# PDNode-600_Pro.net
KiCad netlist of a schematic drawn in EAGLE
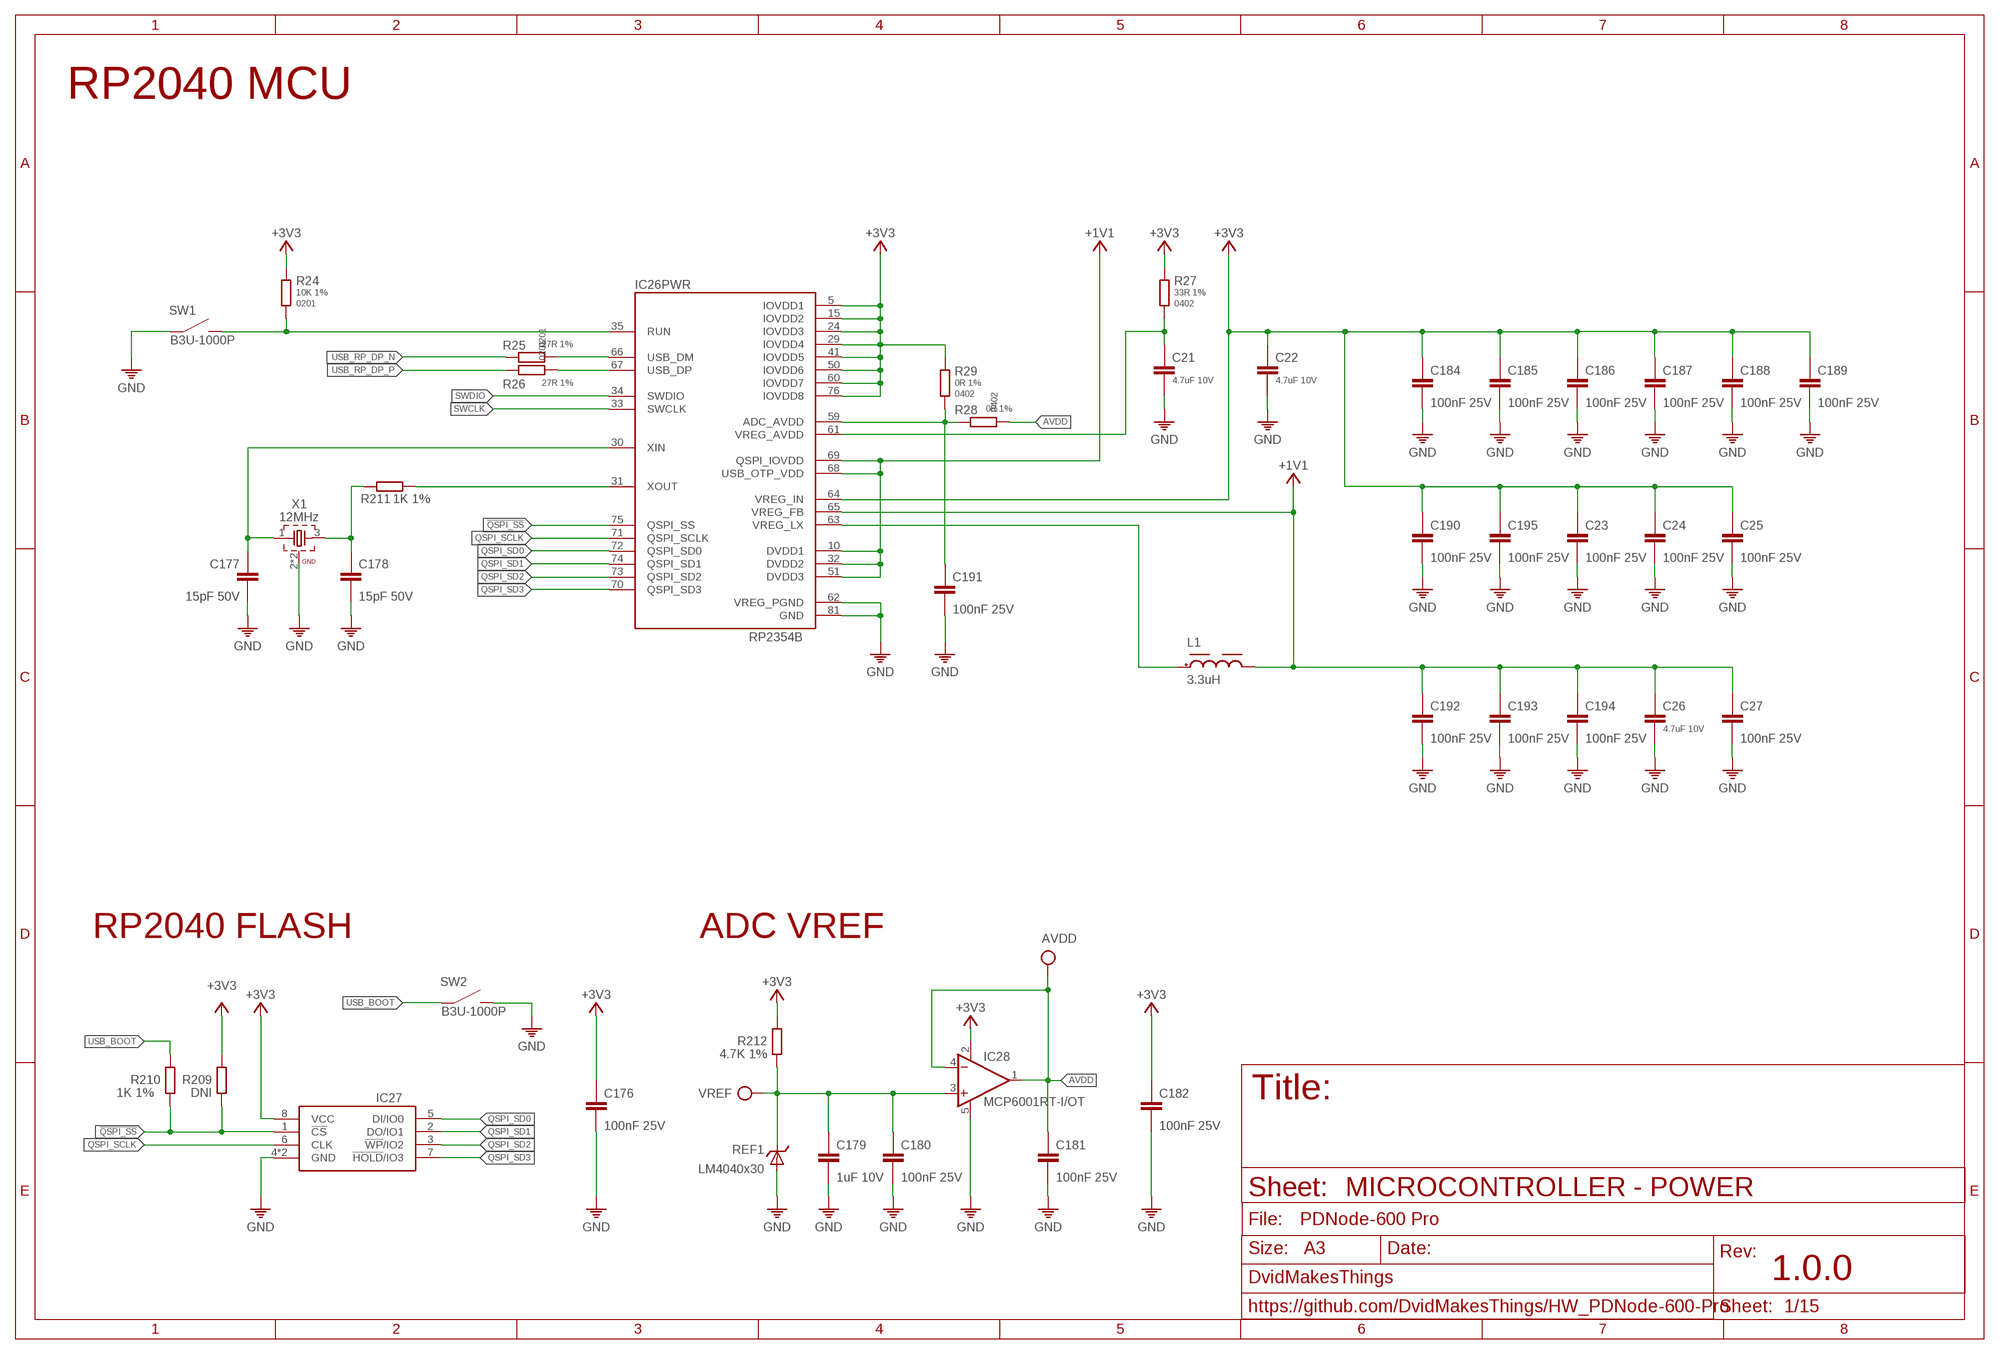
[diagram p0: schematic, sheet 1]
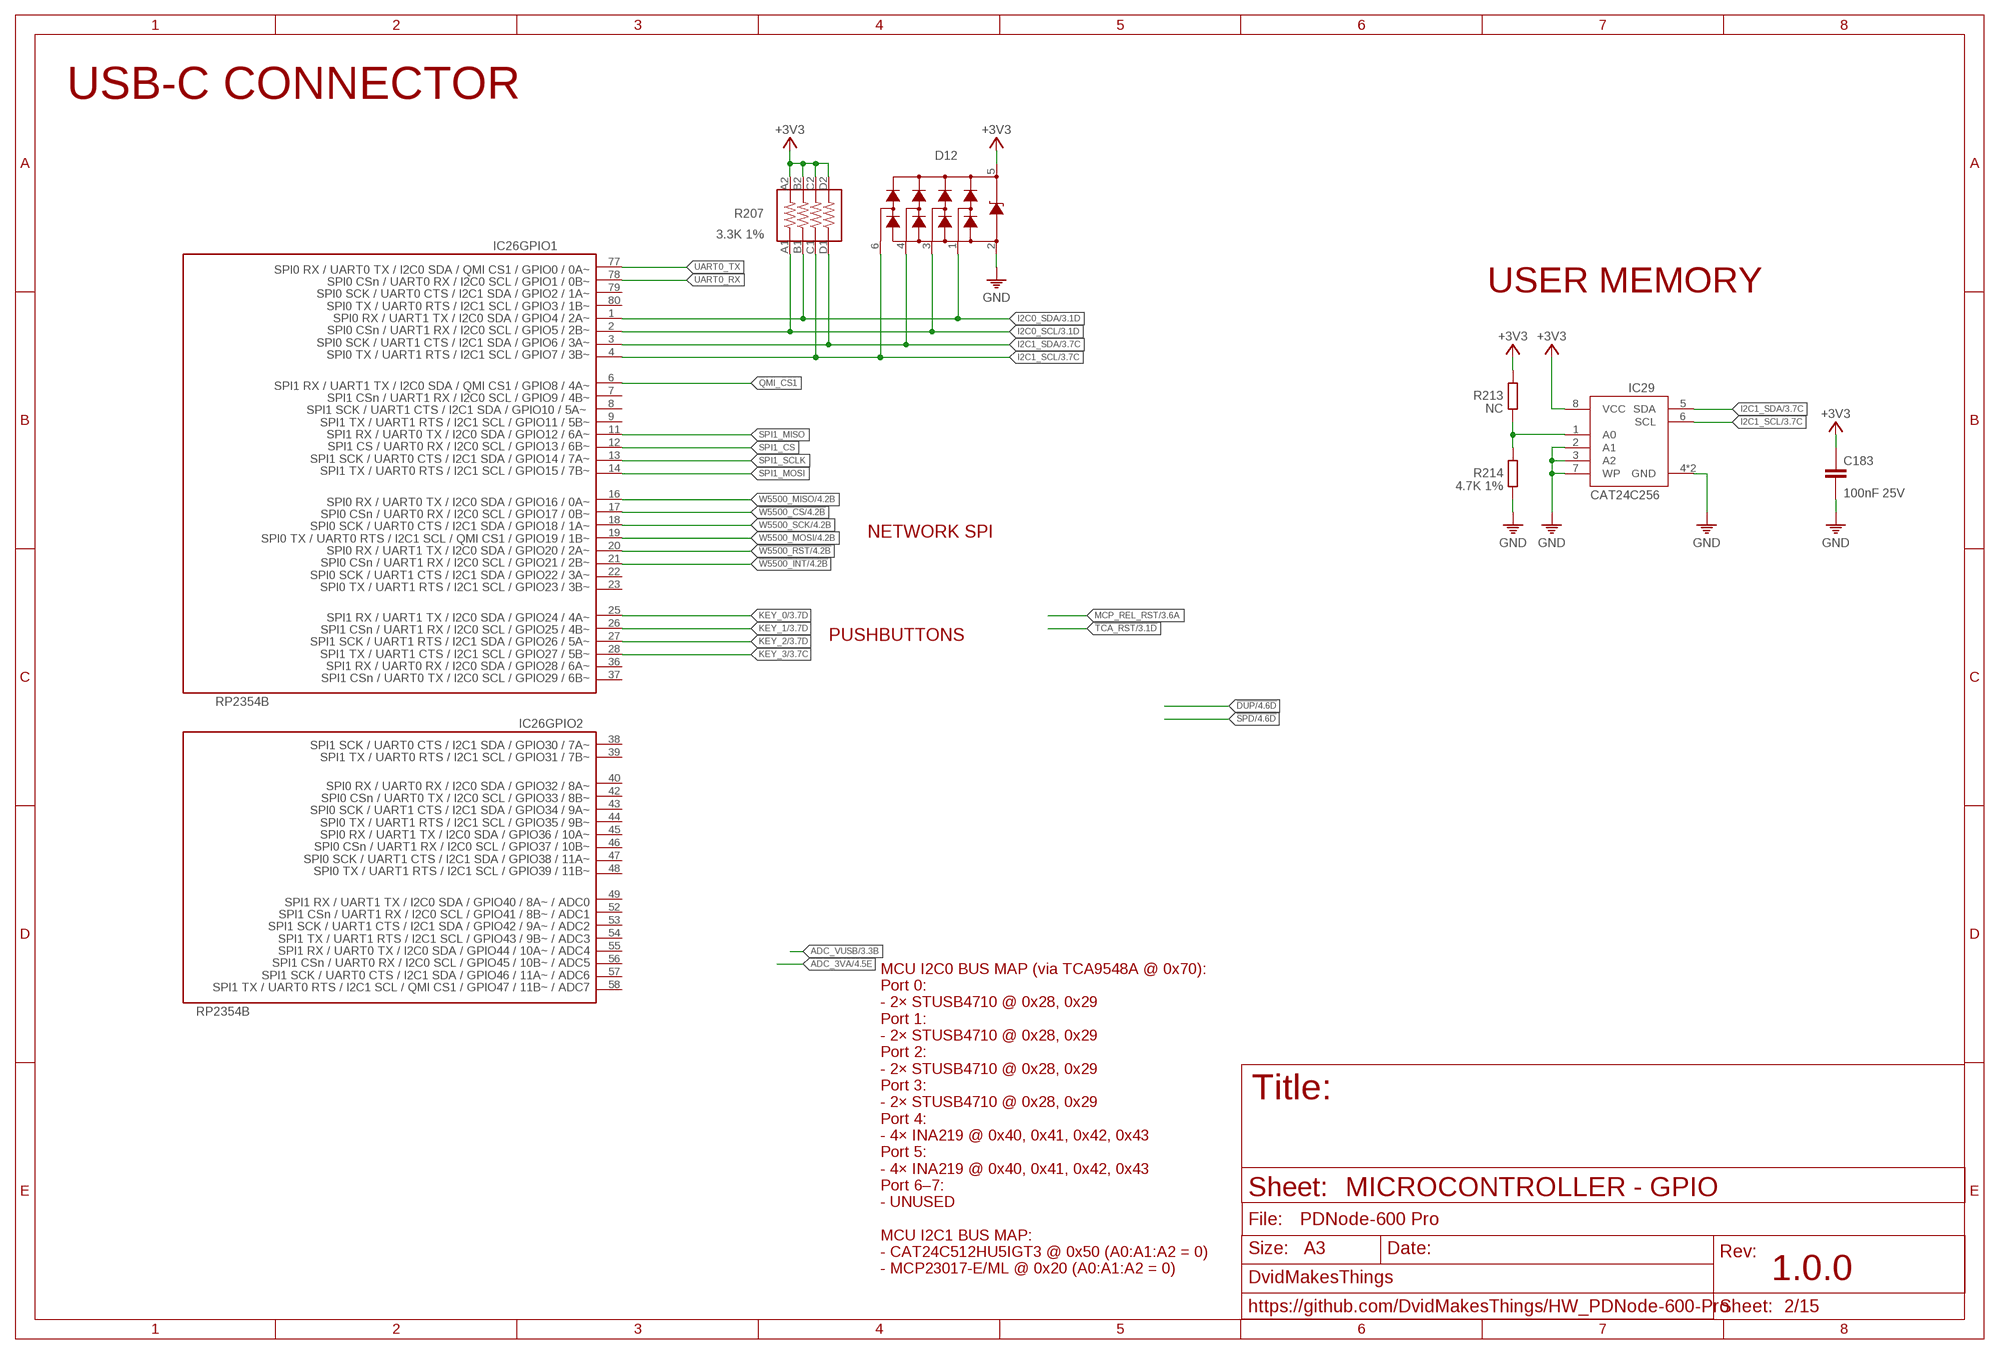
[diagram p1: schematic, sheet 2]
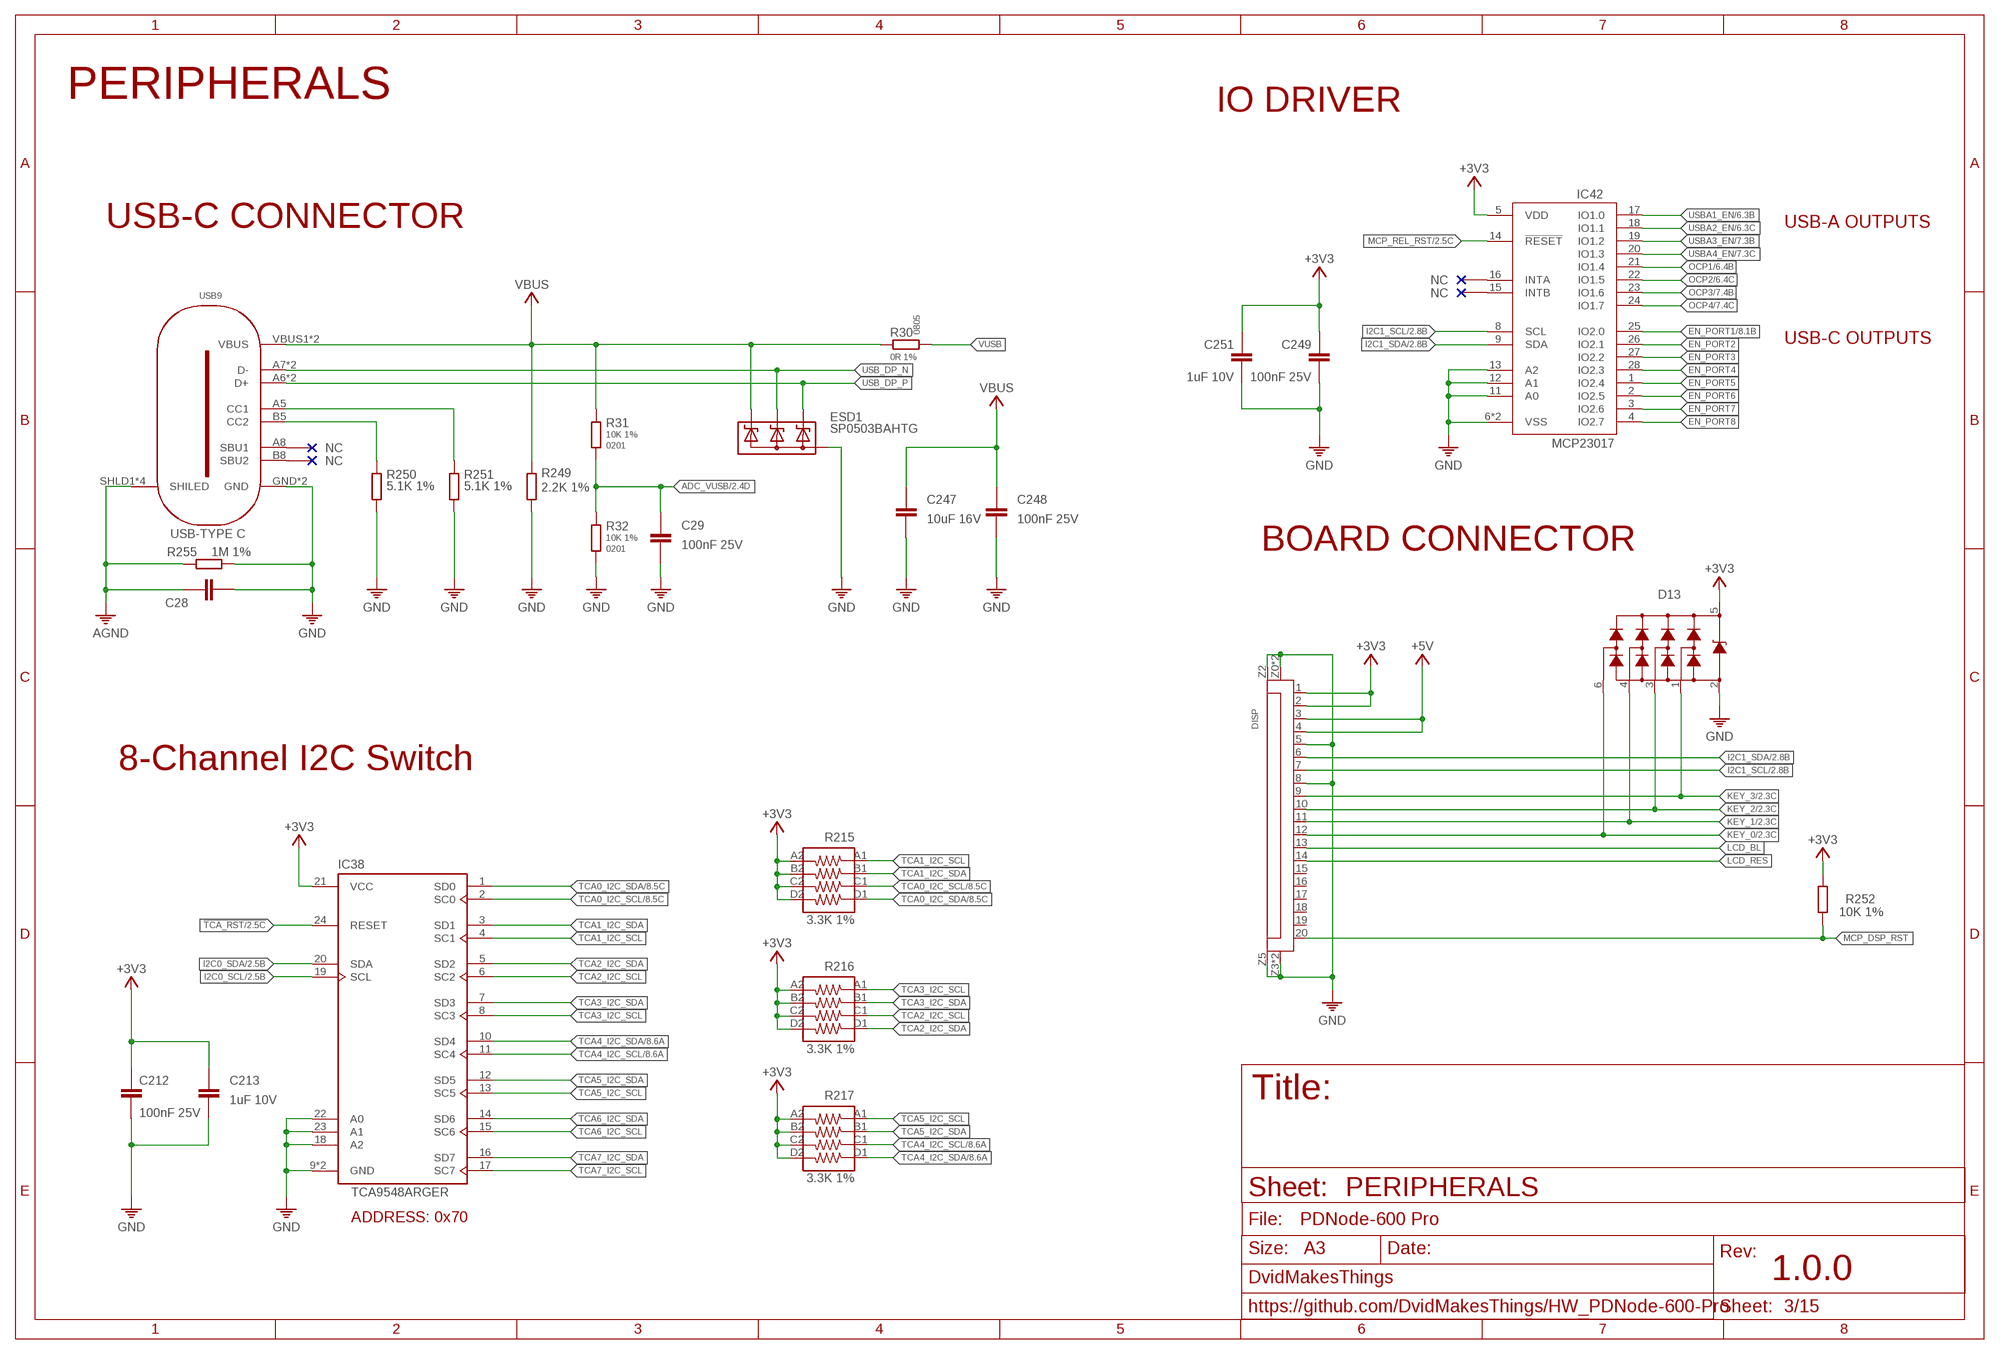
[diagram p2: schematic, sheet 3]
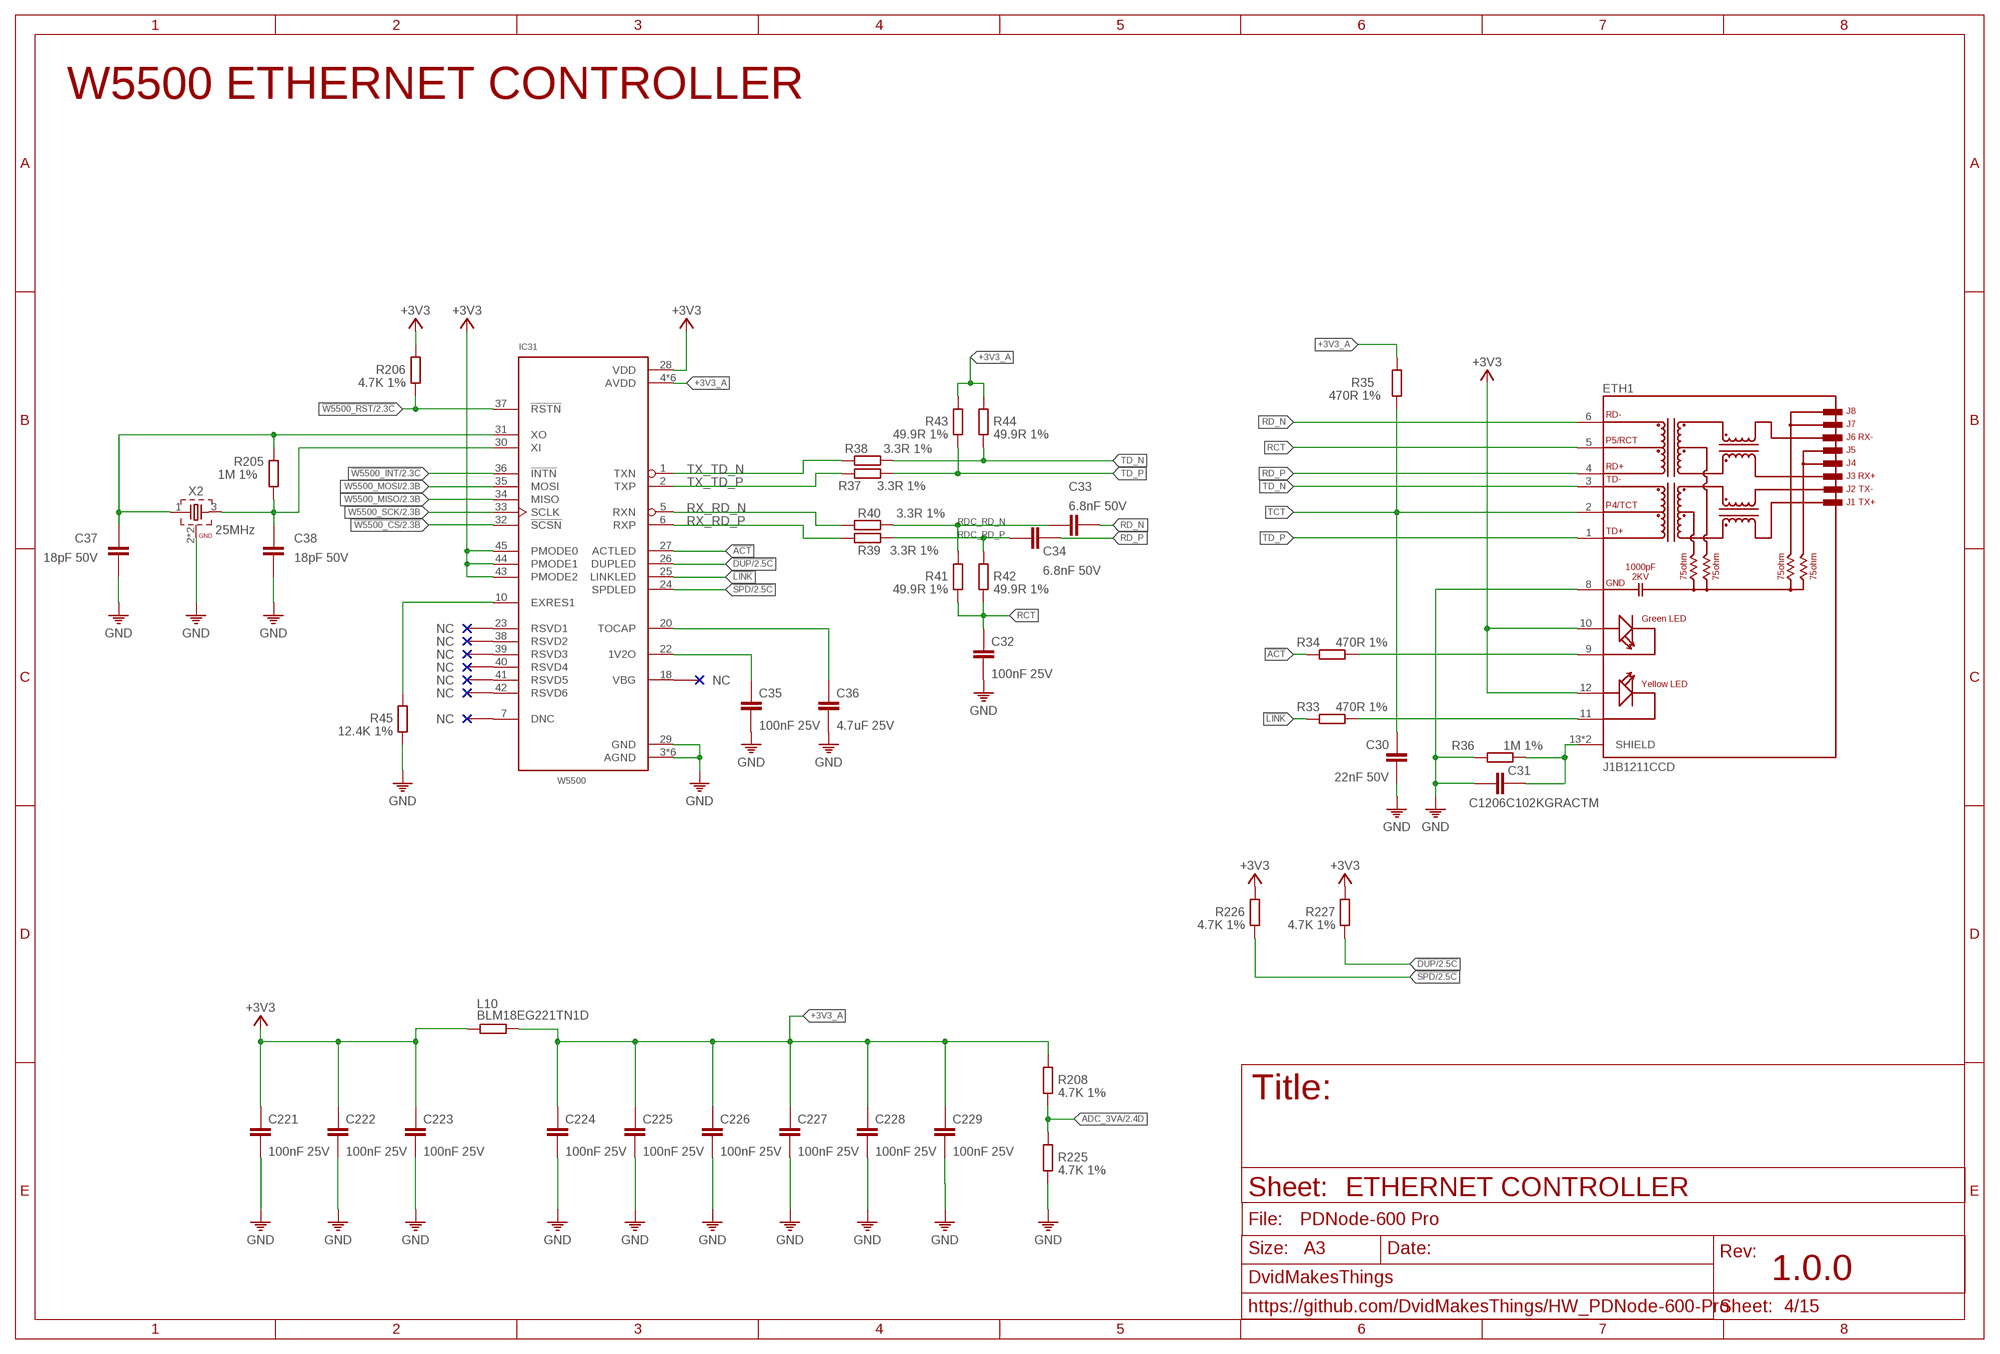
[diagram p3: schematic, sheet 4]
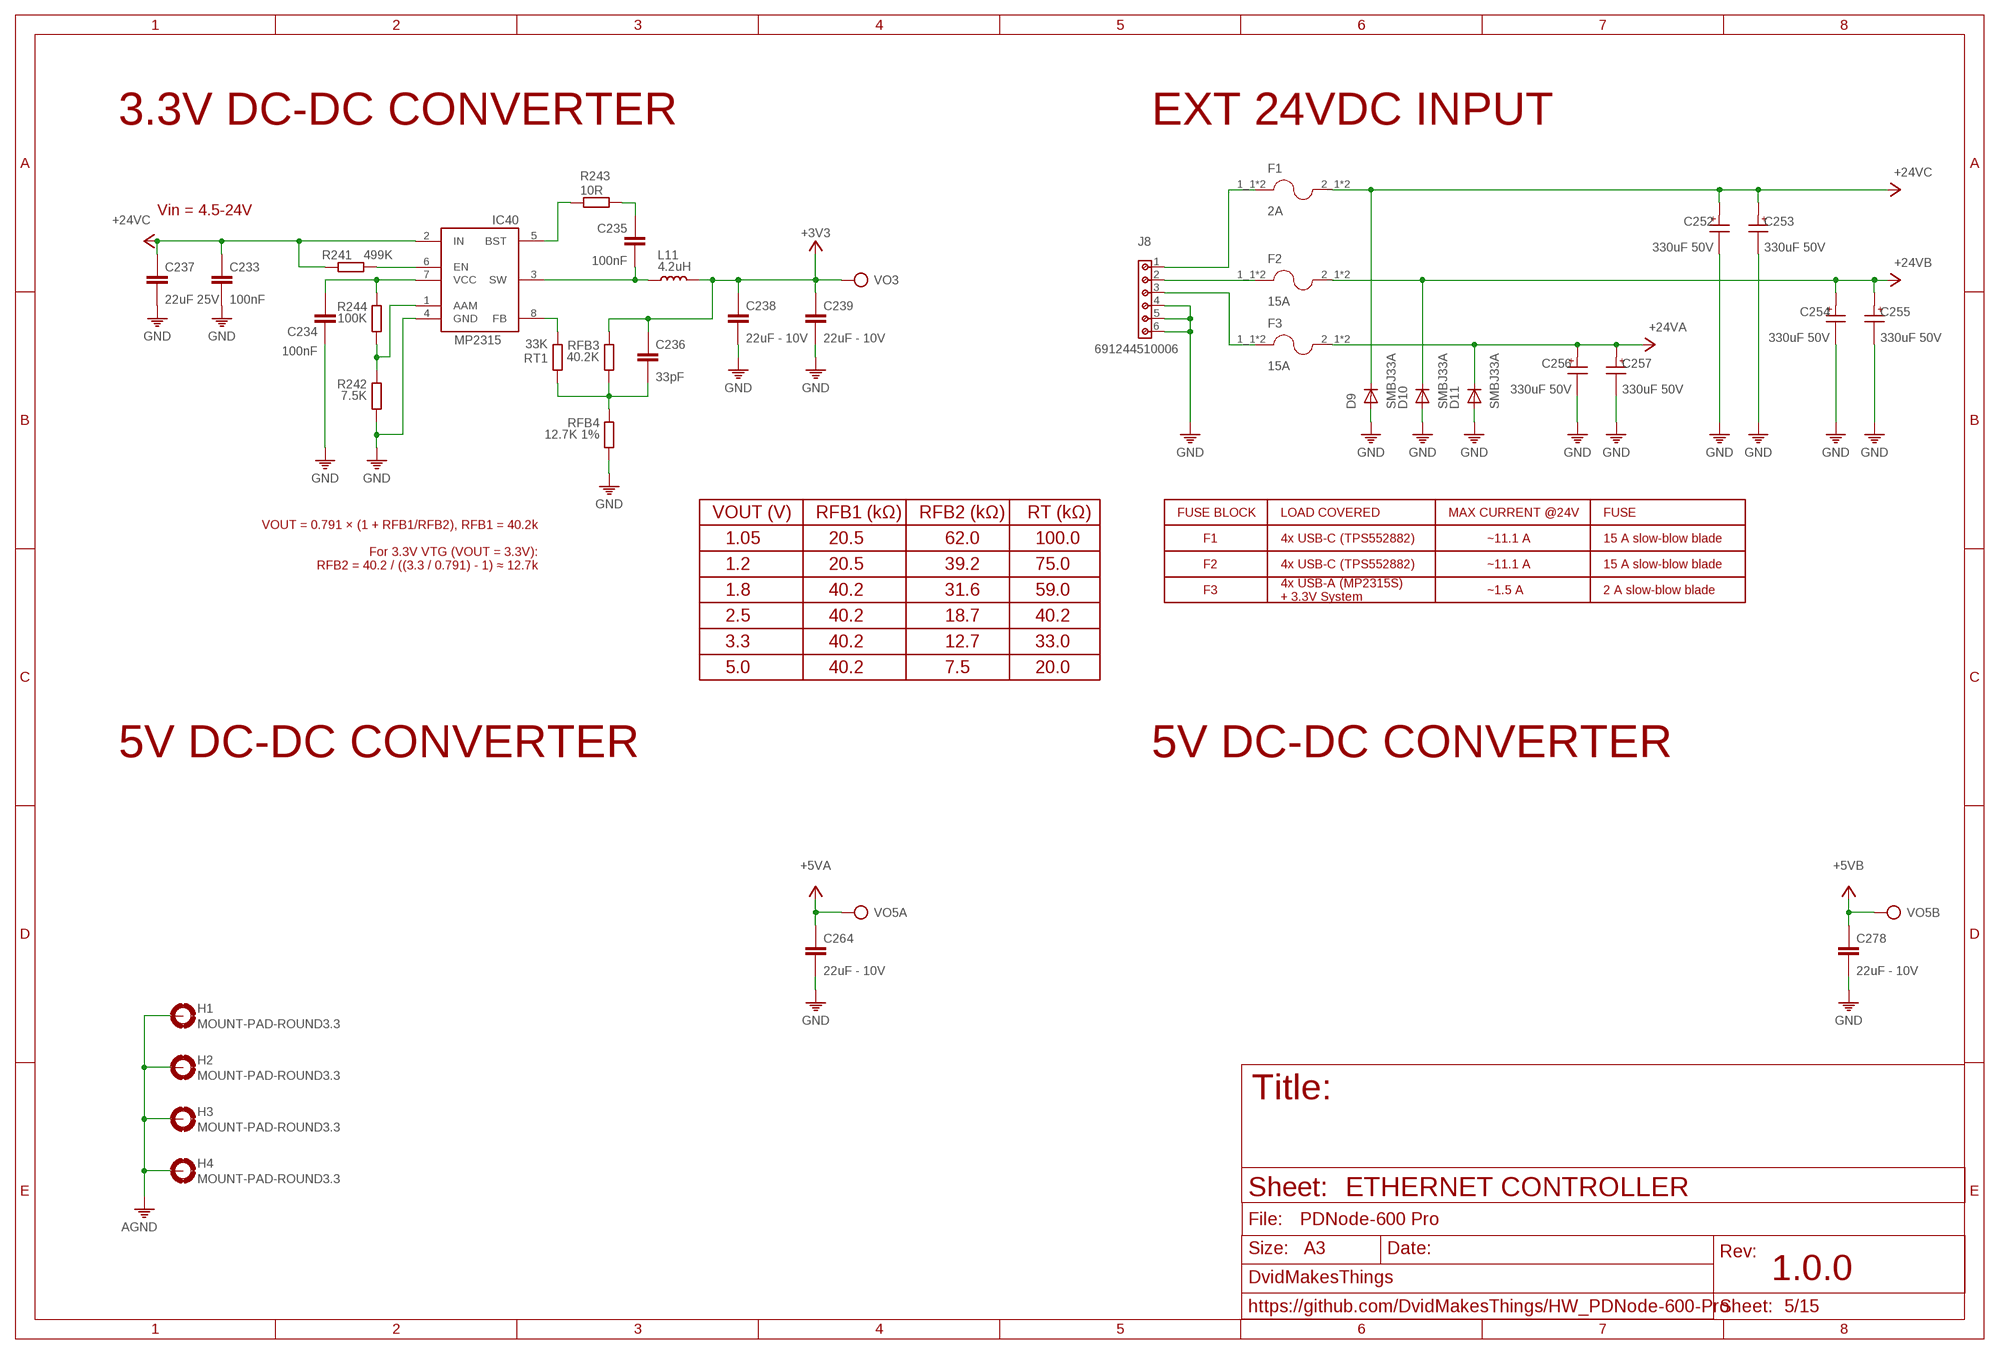
[diagram p4: schematic, sheet 5]
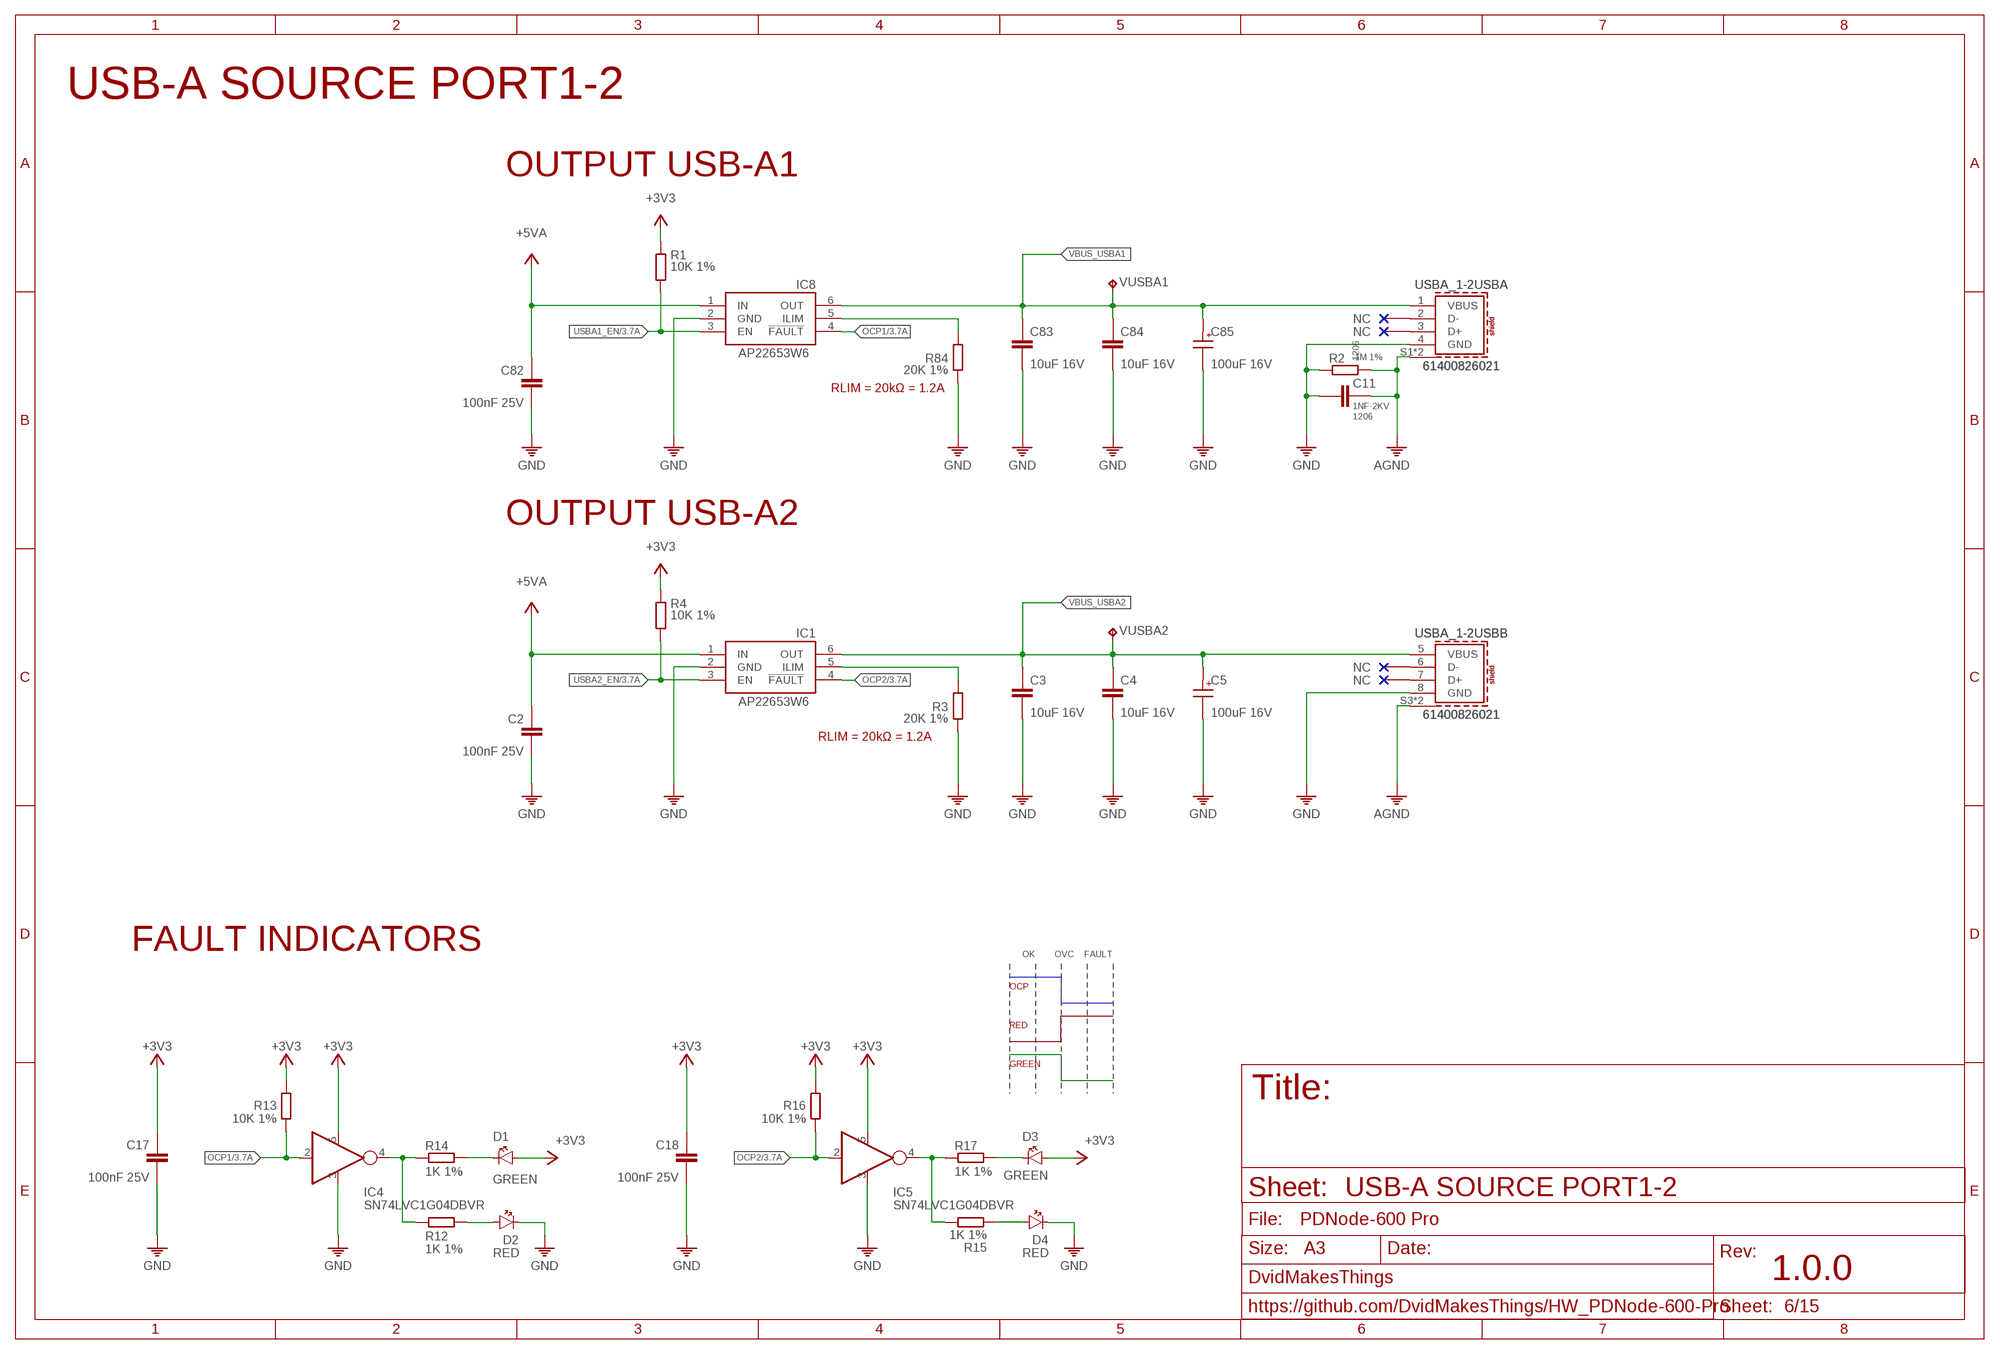
[diagram p5: schematic, sheet 6]
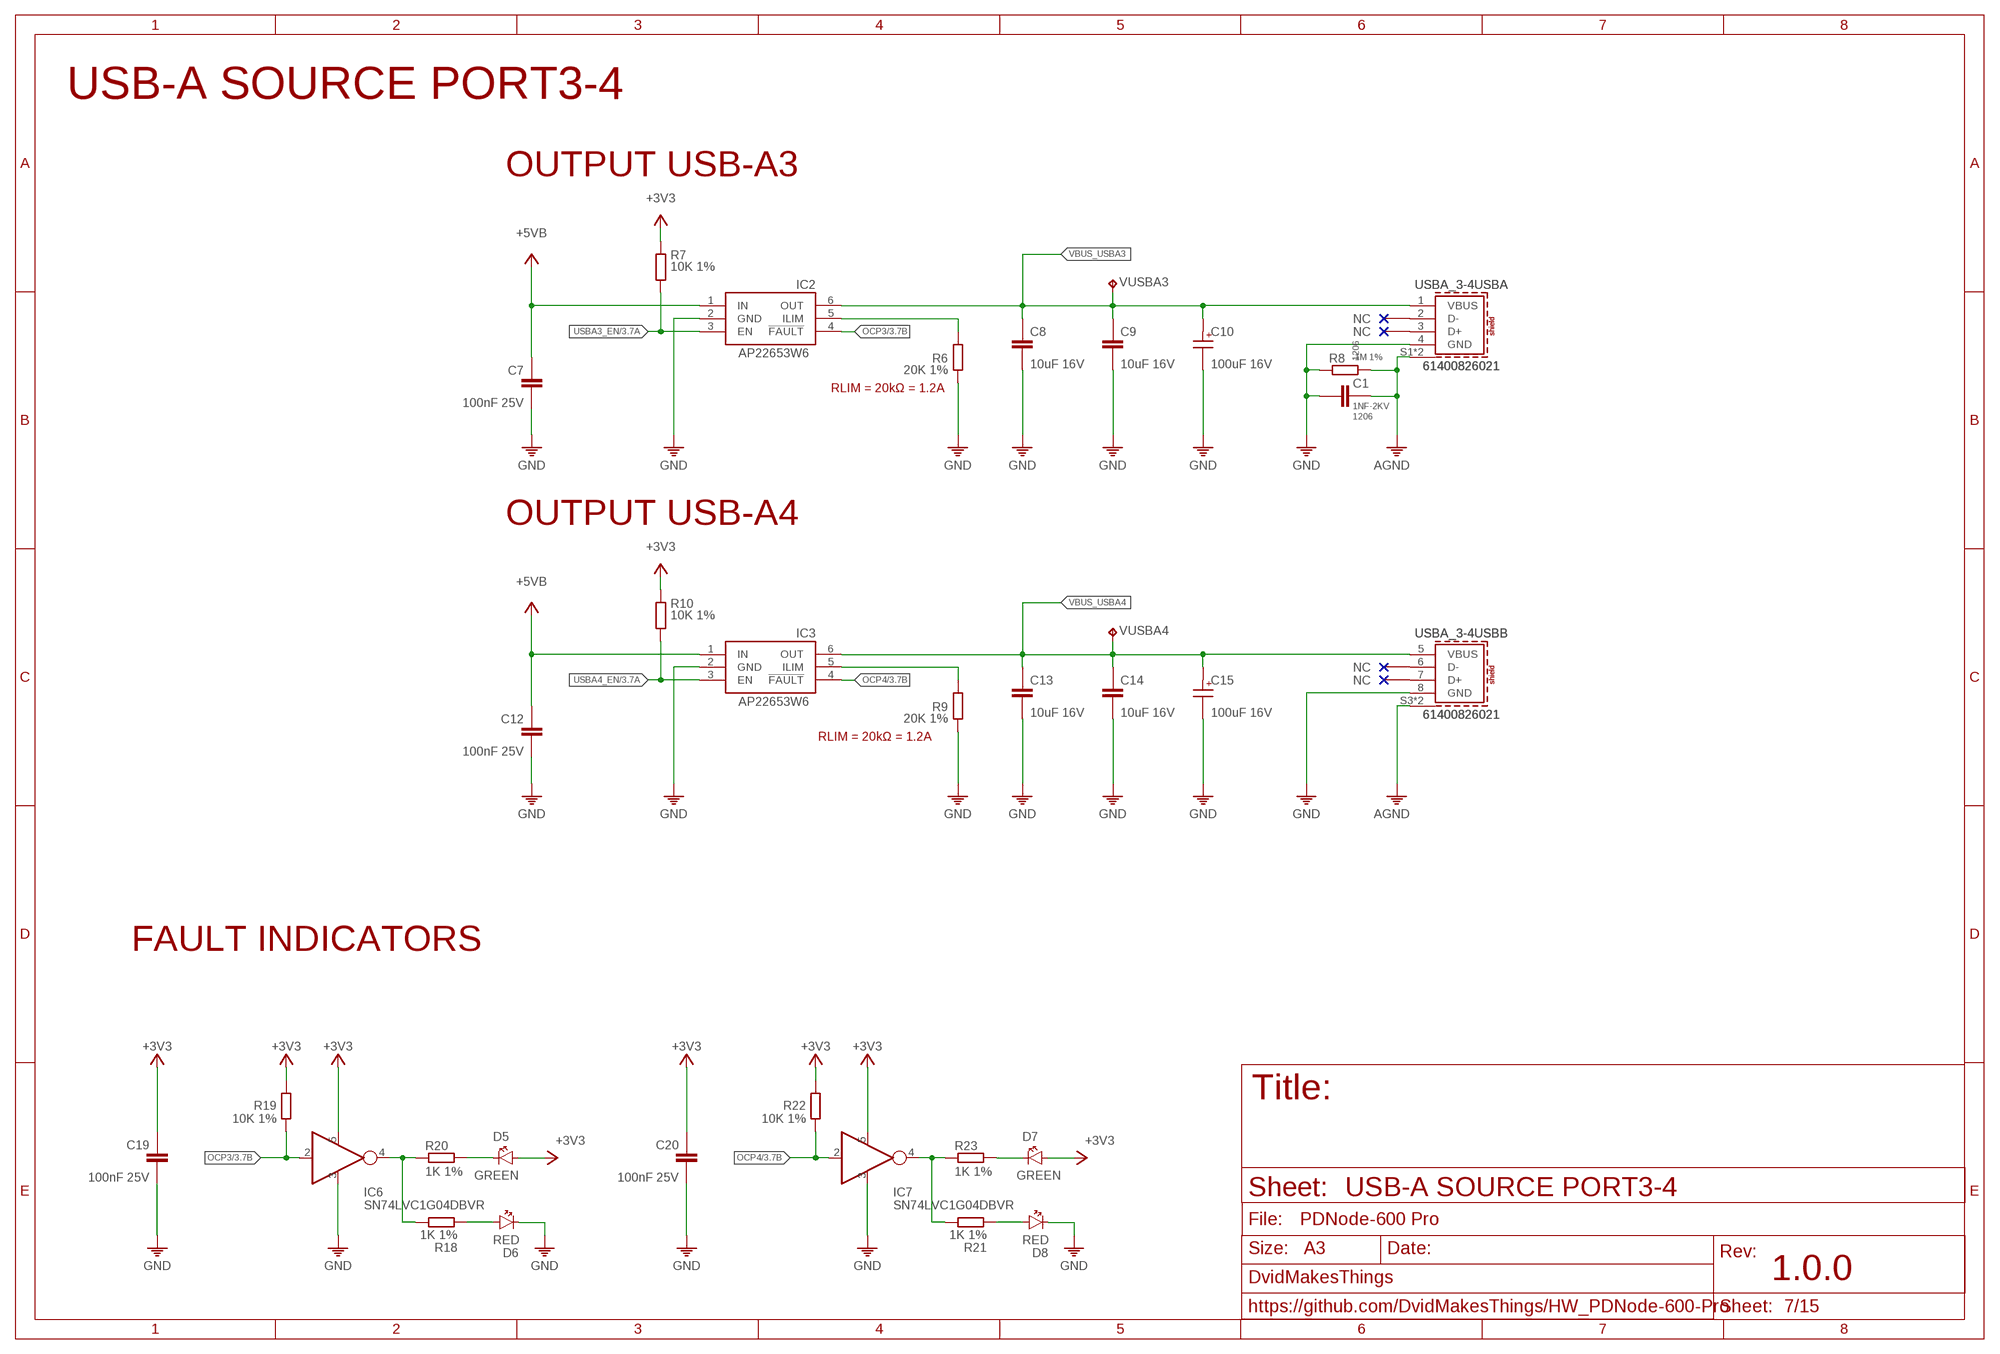
[diagram p6: schematic, sheet 7]
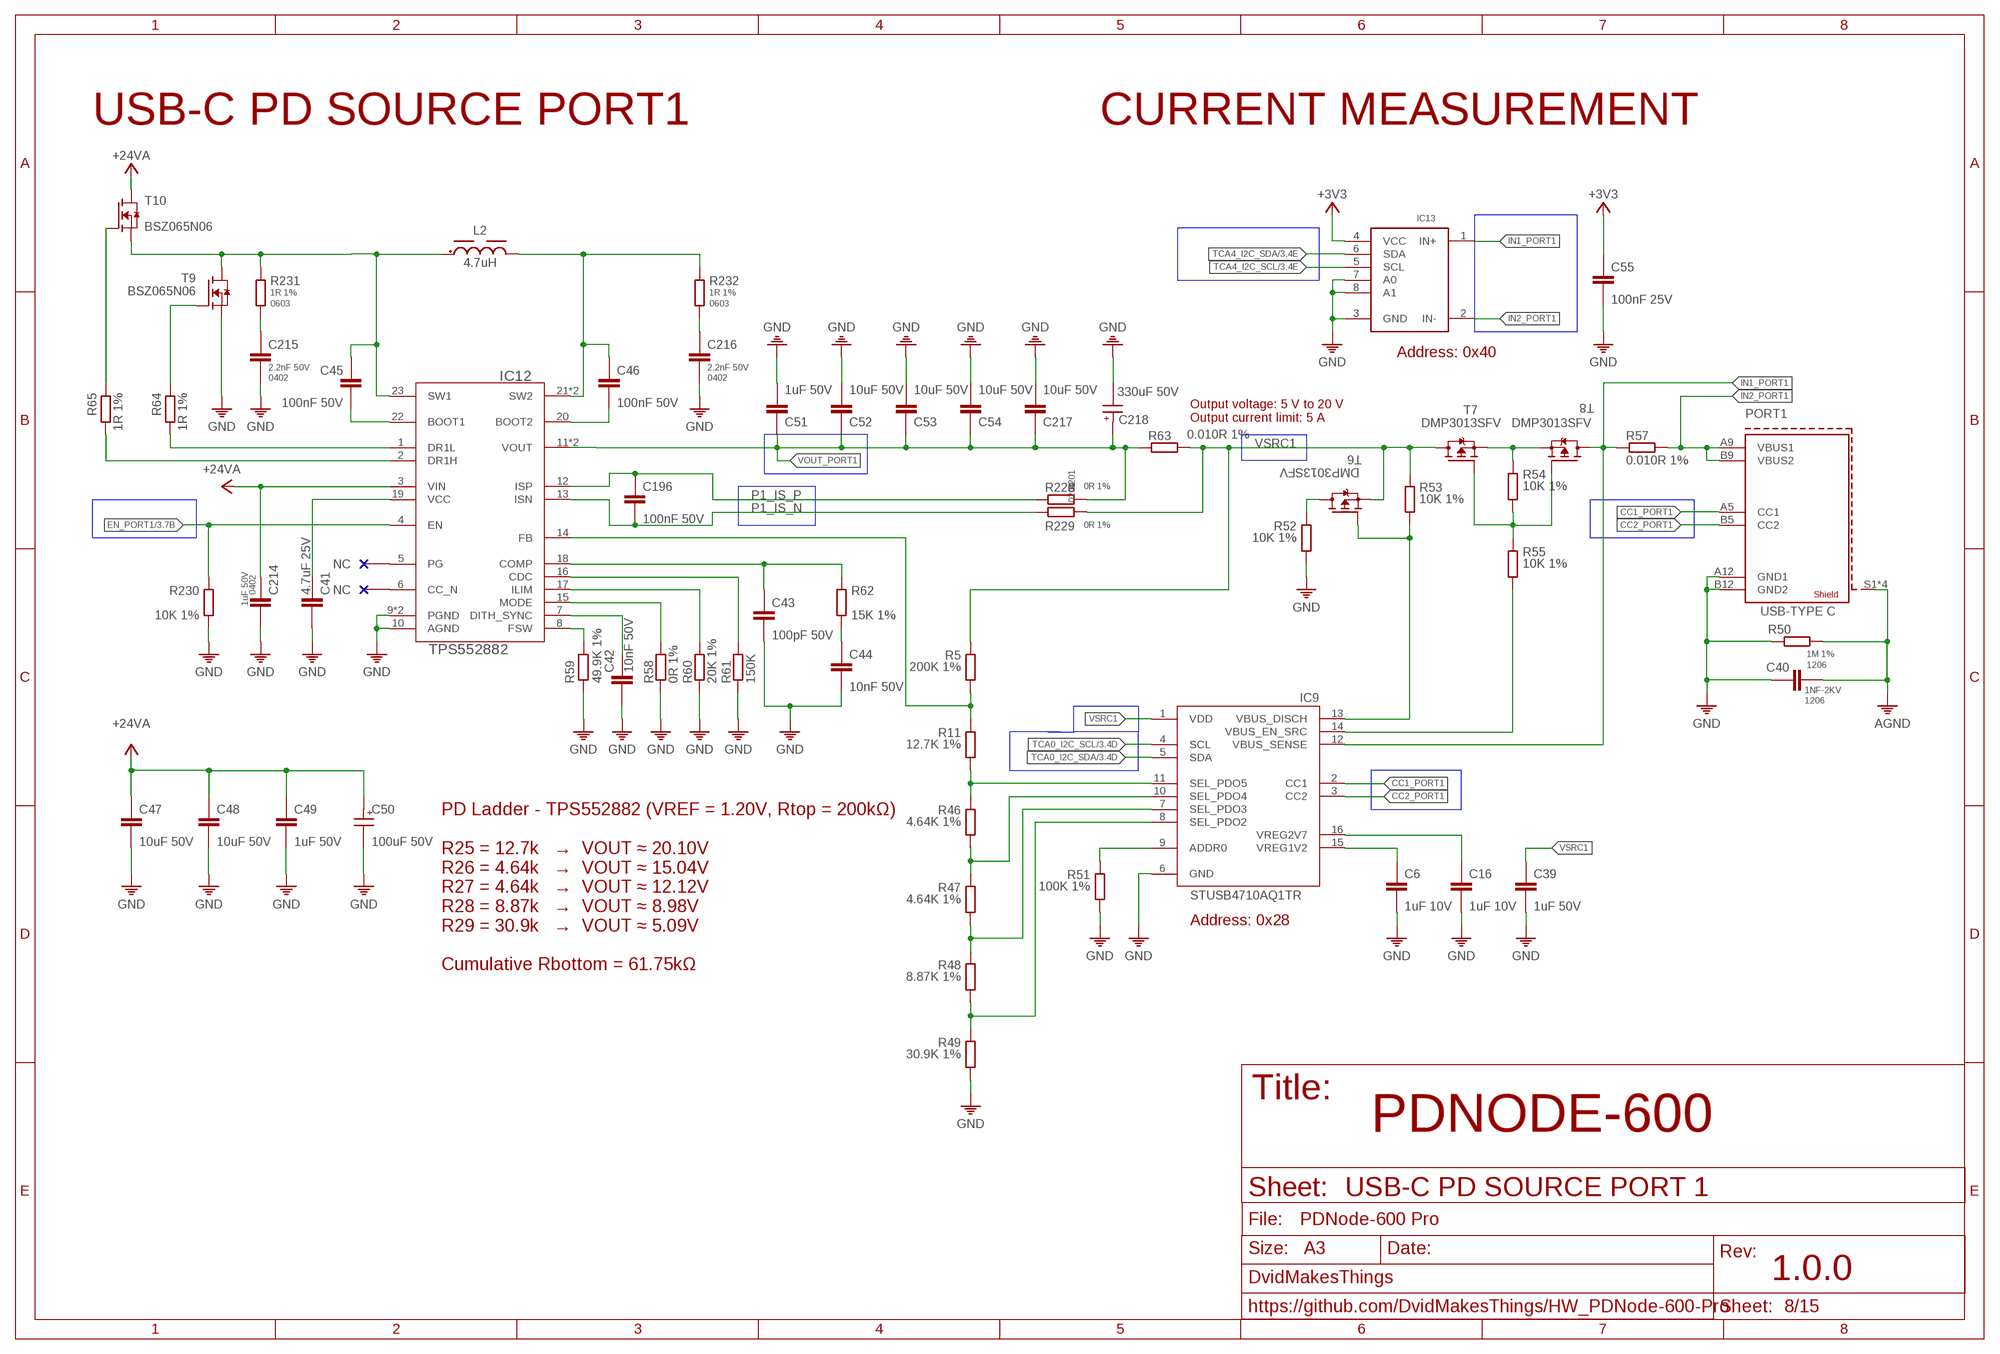
[diagram p7: schematic, sheet 8]

(export (version "E")
  (design (tool "Eeschema 10.0.6"))
  (components
    (comp (ref "C1")
      (value "1NF-2KV")
      (footprint "eagle-import:1206")
      (fields
        (field (name "PACKAGE") "1206")
        (field (name "HQ_PART") "CA0134884")
        (field (name "LCSC_PART") "C9196")
        (field (name "MANUFACTURER") "KEMET")
      )
      (libsource (lib "eagle-import") (part "1NF-2KV"))
    )
    (comp (ref "C7")
      (value "100nF 25V")
      (footprint "eagle-import:0201")
      (fields
        (field (name "HQ_PART") "CA0183221")
        (field (name "LCSC_PART") "C76939")
        (field (name "MANUFACTURER") "Samsung")
      )
      (libsource (lib "eagle-import") (part "100NF-25V-0201"))
    )
    (comp (ref "C8")
      (value "10uF 16V")
      (footprint "eagle-import:0603")
      (fields
        (field (name "HQ_PART") "CA0149236")
        (field (name "LCSC_PART") "C92487")
        (field (name "MANUFACTURER") "Murata")
      )
      (libsource (lib "eagle-import") (part "10UF-16V-0603"))
    )
    (comp (ref "C9")
      (value "10uF 16V")
      (footprint "eagle-import:0603")
      (fields
        (field (name "HQ_PART") "CA0149236")
        (field (name "LCSC_PART") "C92487")
        (field (name "MANUFACTURER") "Murata")
      )
      (libsource (lib "eagle-import") (part "10UF-16V-0603"))
    )
    (comp (ref "C10")
      (value "100uF 16V")
      (footprint "eagle-import:5X5.5(DXL)")
      (fields (field (name "LCSC_PART") "C2977550"))
      (libsource (lib "eagle-import") (part "100UF-16V5X5.5(DXL)"))
    )
    (comp (ref "C12")
      (value "100nF 25V")
      (footprint "eagle-import:0201")
      (fields
        (field (name "HQ_PART") "CA0183221")
        (field (name "LCSC_PART") "C76939")
        (field (name "MANUFACTURER") "Samsung")
      )
      (libsource (lib "eagle-import") (part "100NF-25V-0201"))
    )
    (comp (ref "C13")
      (value "10uF 16V")
      (footprint "eagle-import:0603")
      (fields
        (field (name "HQ_PART") "CA0149236")
        (field (name "LCSC_PART") "C92487")
        (field (name "MANUFACTURER") "Murata")
      )
      (libsource (lib "eagle-import") (part "10UF-16V-0603"))
    )
    (comp (ref "C14")
      (value "10uF 16V")
      (footprint "eagle-import:0603")
      (fields
        (field (name "HQ_PART") "CA0149236")
        (field (name "LCSC_PART") "C92487")
        (field (name "MANUFACTURER") "Murata")
      )
      (libsource (lib "eagle-import") (part "10UF-16V-0603"))
    )
    (comp (ref "C15")
      (value "100uF 16V")
      (footprint "eagle-import:5X5.5(DXL)")
      (fields (field (name "LCSC_PART") "C2977550"))
      (libsource (lib "eagle-import") (part "100UF-16V5X5.5(DXL)"))
    )
    (comp (ref "C19")
      (value "100nF 25V")
      (footprint "eagle-import:0201")
      (fields
        (field (name "HQ_PART") "CA0183221")
        (field (name "LCSC_PART") "C76939")
        (field (name "MANUFACTURER") "Samsung")
      )
      (libsource (lib "eagle-import") (part "100NF-25V-0201"))
    )
    (comp (ref "C20")
      (value "100nF 25V")
      (footprint "eagle-import:0201")
      (fields
        (field (name "HQ_PART") "CA0183221")
        (field (name "LCSC_PART") "C76939")
        (field (name "MANUFACTURER") "Samsung")
      )
      (libsource (lib "eagle-import") (part "100NF-25V-0201"))
    )
    (comp (ref "D5")
      (value "GREEN")
      (footprint "eagle-import:LEDC1608X35N_FLAT-G")
      (libsource (lib "eagle-import") (part "CHIP-FLAT-G_0603-0.35MM"))
    )
    (comp (ref "D6")
      (value "RED")
      (footprint "eagle-import:LEDC1608X35N_FLAT-R")
      (libsource (lib "eagle-import") (part "CHIP-FLAT-R_0603-0.35MM"))
    )
    (comp (ref "D7")
      (value "GREEN")
      (footprint "eagle-import:LEDC1608X35N_FLAT-G")
      (libsource (lib "eagle-import") (part "CHIP-FLAT-G_0603-0.35MM"))
    )
    (comp (ref "D8")
      (value "RED")
      (footprint "eagle-import:LEDC1608X35N_FLAT-R")
      (libsource (lib "eagle-import") (part "CHIP-FLAT-R_0603-0.35MM"))
    )
    (comp (ref "IC2")
      (value "AP22653W6")
      (footprint "eagle-import:SOT23-6")
      (fields
        (field (name "HQ_PART") "PM0174903")
        (field (name "LCSC_PART") "C2158037")
        (field (name "MANUFACTURER") "Diodes Incorporated")
      )
      (libsource (lib "eagle-import") (part "AP22653W6"))
    )
    (comp (ref "IC3")
      (value "AP22653W6")
      (footprint "eagle-import:SOT23-6")
      (fields
        (field (name "HQ_PART") "PM0174903")
        (field (name "LCSC_PART") "C2158037")
        (field (name "MANUFACTURER") "Diodes Incorporated")
      )
      (libsource (lib "eagle-import") (part "AP22653W6"))
    )
    (comp (ref "IC6")
      (value "SN74LVC1G04DBVR")
      (footprint "eagle-import:SOT95P280X145-5N")
      (libsource (lib "eagle-import") (part "74LVC1G04"))
    )
    (comp (ref "IC7")
      (value "SN74LVC1G04DBVR")
      (footprint "eagle-import:SOT95P280X145-5N")
      (libsource (lib "eagle-import") (part "74LVC1G04"))
    )
    (comp (ref "R6")
      (value "20K 1%")
      (footprint "eagle-import:0201")
      (fields (field (name "LCSC_PART") "C473466"))
      (libsource (lib "eagle-import") (part "20K-1%0201"))
    )
    (comp (ref "R7")
      (value "10K 1%")
      (footprint "eagle-import:0402")
      (fields
        (field (name "HQ_PART") "RE0207399")
        (field (name "LCSC_PART") "C25744")
        (field (name "MANUFACTURER") "ROHM")
      )
      (libsource (lib "eagle-import") (part "10K-1%0402"))
    )
    (comp (ref "R8")
      (value "1M 1%")
      (footprint "eagle-import:1206")
      (fields
        (field (name "PACKAGE") "1206")
        (field (name "HQ_PART") "RE0188103")
        (field (name "LCSC_PART") "C17927")
        (field (name "MANUFACTURER") "Uniohm")
      )
      (libsource (lib "eagle-import") (part "1M-1%1206"))
    )
    (comp (ref "R9")
      (value "20K 1%")
      (footprint "eagle-import:0201")
      (fields (field (name "LCSC_PART") "C473466"))
      (libsource (lib "eagle-import") (part "20K-1%0201"))
    )
    (comp (ref "R10")
      (value "10K 1%")
      (footprint "eagle-import:0402")
      (fields
        (field (name "HQ_PART") "RE0207399")
        (field (name "LCSC_PART") "C25744")
        (field (name "MANUFACTURER") "ROHM")
      )
      (libsource (lib "eagle-import") (part "10K-1%0402"))
    )
    (comp (ref "R18")
      (value "1K 1%")
      (footprint "eagle-import:0402")
      (fields
        (field (name "HQ_PART") "RE0208724")
        (field (name "LCSC_PART") "C11702")
        (field (name "MANUFACTURER") "FH")
      )
      (libsource (lib "eagle-import") (part "1K-1%0402"))
    )
    (comp (ref "R19")
      (value "10K 1%")
      (footprint "eagle-import:0402")
      (fields
        (field (name "HQ_PART") "RE0207399")
        (field (name "LCSC_PART") "C25744")
        (field (name "MANUFACTURER") "ROHM")
      )
      (libsource (lib "eagle-import") (part "10K-1%0402"))
    )
    (comp (ref "R20")
      (value "1K 1%")
      (footprint "eagle-import:0402")
      (fields
        (field (name "HQ_PART") "RE0208724")
        (field (name "LCSC_PART") "C11702")
        (field (name "MANUFACTURER") "FH")
      )
      (libsource (lib "eagle-import") (part "1K-1%0402"))
    )
    (comp (ref "R21")
      (value "1K 1%")
      (footprint "eagle-import:0402")
      (fields
        (field (name "HQ_PART") "RE0208724")
        (field (name "LCSC_PART") "C11702")
        (field (name "MANUFACTURER") "FH")
      )
      (libsource (lib "eagle-import") (part "1K-1%0402"))
    )
    (comp (ref "R22")
      (value "10K 1%")
      (footprint "eagle-import:0402")
      (fields
        (field (name "HQ_PART") "RE0207399")
        (field (name "LCSC_PART") "C25744")
        (field (name "MANUFACTURER") "ROHM")
      )
      (libsource (lib "eagle-import") (part "10K-1%0402"))
    )
    (comp (ref "R23")
      (value "1K 1%")
      (footprint "eagle-import:0402")
      (fields
        (field (name "HQ_PART") "RE0208724")
        (field (name "LCSC_PART") "C11702")
        (field (name "MANUFACTURER") "FH")
      )
      (libsource (lib "eagle-import") (part "1K-1%0402"))
    )
    (comp (ref "USBA_3-4")
      (value "61400826021")
      (footprint "eagle-import:61400826021")
      (libsource (lib "eagle-import") (part "61400826021"))
    )
    (comp (ref "VUSBA3")
      (value "TPB1,27")
      (footprint "eagle-import:B1,27")
      (libsource (lib "eagle-import") (part "TPB1,27"))
    )
    (comp (ref "VUSBA4")
      (value "TPB1,27")
      (footprint "eagle-import:B1,27")
      (libsource (lib "eagle-import") (part "TPB1,27"))
    )
    (comp (ref "C28")
      (value "1NF-2KV")
      (footprint "eagle-import:1206")
      (fields
        (field (name "HQ_PART") "CA0134884")
        (field (name "LCSC_PART") "C9196")
        (field (name "MANUFACTURER") "KEMET")
      )
      (libsource (lib "eagle-import") (part "1NF-2KV"))
    )
    (comp (ref "C29")
      (value "100nF 25V")
      (footprint "eagle-import:0402")
      (fields
        (field (name "HQ_PART") "CA0176807")
        (field (name "LCSC_PART") "C56392")
        (field (name "MANUFACTURER") "Walsin")
      )
      (libsource (lib "eagle-import") (part "100NF-25V-0402"))
    )
    (comp (ref "C212")
      (value "100nF 25V")
      (footprint "eagle-import:0201")
      (fields
        (field (name "HQ_PART") "CA0183221")
        (field (name "LCSC_PART") "C76939")
        (field (name "MANUFACTURER") "Samsung")
      )
      (libsource (lib "eagle-import") (part "100NF-25V-0201"))
    )
    (comp (ref "C213")
      (value "1uF 10V")
      (footprint "eagle-import:0201")
      (fields (field (name "LCSC_PART") "C76935"))
      (libsource (lib "eagle-import") (part "1UF-10V0201"))
    )
    (comp (ref "C247")
      (value "10uF 16V")
      (footprint "eagle-import:0603")
      (fields
        (field (name "HQ_PART") "CA0149236")
        (field (name "LCSC_PART") "C92487")
        (field (name "MANUFACTURER") "Murata")
      )
      (libsource (lib "eagle-import") (part "10UF-16V-0603"))
    )
    (comp (ref "C248")
      (value "100nF 25V")
      (footprint "eagle-import:0402")
      (fields
        (field (name "HQ_PART") "CA0176807")
        (field (name "LCSC_PART") "C56392")
        (field (name "MANUFACTURER") "Walsin")
      )
      (libsource (lib "eagle-import") (part "100NF-25V-0402"))
    )
    (comp (ref "C249")
      (value "100nF 25V")
      (footprint "eagle-import:0201")
      (fields
        (field (name "HQ_PART") "CA0183221")
        (field (name "LCSC_PART") "C76939")
        (field (name "MANUFACTURER") "Samsung")
      )
      (libsource (lib "eagle-import") (part "100NF-25V-0201"))
    )
    (comp (ref "C251")
      (value "1uF 10V")
      (footprint "eagle-import:0201")
      (fields (field (name "LCSC_PART") "C76935"))
      (libsource (lib "eagle-import") (part "1UF-10V0201"))
    )
    (comp (ref "D13")
      (value "HDMIULC6-4SC6Y")
      (footprint "eagle-import:SOT23-6")
      (libsource (lib "eagle-import") (part "HDMIULC6-4SC6Y"))
    )
    (comp (ref "DISP")
      (value "AFC11-S20ICC-00")
      (footprint "eagle-import:FPC20")
      (fields
        (field (name "HQ_PART") "CO0889517")
        (field (name "LCSC_PART") "C466537")
        (field (name "MANUFACTURER") "JS")
      )
      (libsource (lib "eagle-import") (part "AFC11-S20ICC-00"))
    )
    (comp (ref "ESD1")
      (value "SP0503BAHTG")
      (footprint "eagle-import:SOT143")
      (fields
        (field (name "HQ_PART") "CP0003989")
        (field (name "LCSC_PART") "C3040626")
        (field (name "MANUFACTURER") "Littelfuse")
      )
      (libsource (lib "eagle-import") (part "SP0503BAHT"))
    )
    (comp (ref "IC38")
      (value "TCA9548ARGER")
      (footprint "eagle-import:QFN50P400X400X100-25T210N")
      (libsource (lib "eagle-import") (part "TCA9548ARGER"))
    )
    (comp (ref "IC42")
      (value "MCP23017T-E/ML")
      (footprint "eagle-import:QFN28[6X6]ML")
      (fields
        (field (name "HQ_PART") "IC0080215")
        (field (name "LCSC_PART") "C629439")
        (field (name "MANUFACTURER") "MICROCHIP")
      )
      (libsource (lib "eagle-import") (part "MCP23017-E/ML"))
    )
    (comp (ref "R30")
      (value "0R 1%")
      (footprint "eagle-import:0805")
      (fields
        (field (name "PACKAGE") "0805")
        (field (name "HQ_PART") "RE0013023")
        (field (name "LCSC_PART") "C17477")
        (field (name "MANUFACTURER") "Vishay")
      )
      (libsource (lib "eagle-import") (part "0R0805"))
    )
    (comp (ref "R31")
      (value "10K 1%")
      (footprint "eagle-import:0201")
      (fields
        (field (name "PACKAGE") "0201")
        (field (name "HQ_PART") "RE0208620")
        (field (name "LCSC_PART") "C473048")
        (field (name "MANUFACTURER") "FH")
      )
      (libsource (lib "eagle-import") (part "10K-1%0201"))
    )
    (comp (ref "R32")
      (value "10K 1%")
      (footprint "eagle-import:0201")
      (fields
        (field (name "PACKAGE") "0201")
        (field (name "HQ_PART") "RE0208620")
        (field (name "LCSC_PART") "C473048")
        (field (name "MANUFACTURER") "FH")
      )
      (libsource (lib "eagle-import") (part "10K-1%0201"))
    )
    (comp (ref "R215")
      (value "3.3K 1%")
      (footprint "eagle-import:_0603X4-1206")
      (fields
        (field (name "HQ_PART") "RE0093863")
        (field (name "LCSC_PART") "C1734380")
        (field (name "MANUFACTURER") "Yageo")
      )
      (libsource (lib "eagle-import") (part "3.3K-1%_ARRAY0603X4-1206"))
    )
    (comp (ref "R216")
      (value "3.3K 1%")
      (footprint "eagle-import:_0603X4-1206")
      (fields
        (field (name "HQ_PART") "RE0093863")
        (field (name "LCSC_PART") "C1734380")
        (field (name "MANUFACTURER") "Yageo")
      )
      (libsource (lib "eagle-import") (part "3.3K-1%_ARRAY0603X4-1206"))
    )
    (comp (ref "R217")
      (value "3.3K 1%")
      (footprint "eagle-import:_0603X4-1206")
      (fields
        (field (name "HQ_PART") "RE0093863")
        (field (name "LCSC_PART") "C1734380")
        (field (name "MANUFACTURER") "Yageo")
      )
      (libsource (lib "eagle-import") (part "3.3K-1%_ARRAY0603X4-1206"))
    )
    (comp (ref "R249")
      (value "2.2K 1%")
      (footprint "eagle-import:0201")
      (fields
        (field (name "HQ_PART") "RE0209901")
        (field (name "LCSC_PART") "C473508")
        (field (name "MANUFACTURER") "FH")
      )
      (libsource (lib "eagle-import") (part "2.2K-1%0201"))
    )
    (comp (ref "R250")
      (value "5.1K 1%")
      (footprint "eagle-import:0201")
      (fields
        (field (name "HQ_PART") "RE0185972")
        (field (name "LCSC_PART") "C274341")
        (field (name "MANUFACTURER") "Yageo")
      )
      (libsource (lib "eagle-import") (part "5.1K-1%0201"))
    )
    (comp (ref "R251")
      (value "5.1K 1%")
      (footprint "eagle-import:0201")
      (fields
        (field (name "HQ_PART") "RE0185972")
        (field (name "LCSC_PART") "C274341")
        (field (name "MANUFACTURER") "Yageo")
      )
      (libsource (lib "eagle-import") (part "5.1K-1%0201"))
    )
    (comp (ref "R252")
      (value "10K 1%")
      (footprint "eagle-import:0201")
      (fields
        (field (name "HQ_PART") "RE0208620")
        (field (name "LCSC_PART") "C473048")
        (field (name "MANUFACTURER") "FH")
      )
      (libsource (lib "eagle-import") (part "10K-1%0201"))
    )
    (comp (ref "R255")
      (value "1M 1%")
      (footprint "eagle-import:0603")
      (fields (field (name "LCSC_PART") "C22935"))
      (libsource (lib "eagle-import") (part "1M-1%0603"))
    )
    (comp (ref "USB9")
      (value "USB-TYPE-C-018")
      (footprint "eagle-import:USB-C")
      (fields
        (field (name "HQ_PART") "ZHLM0322915")
        (field (name "LCSC_PART") "C2927038")
        (field (name "MANUFACTURER") "DEALON")
      )
      (libsource (lib "eagle-import") (part "USB_C-THT"))
    )
    (comp (ref "AVDD")
      (value "TESTPOINT")
      (footprint "eagle-import:TP")
      (libsource (lib "eagle-import") (part "TP"))
    )
    (comp (ref "C21")
      (value "4.7uF 10V")
      (footprint "eagle-import:0402")
      (fields (field (name "LCSC_PART") "C368809"))
      (libsource (lib "eagle-import") (part "4.7UF-10V0402"))
    )
    (comp (ref "C22")
      (value "4.7uF 10V")
      (footprint "eagle-import:0402")
      (fields (field (name "LCSC_PART") "C368809"))
      (libsource (lib "eagle-import") (part "4.7UF-10V0402"))
    )
    (comp (ref "C23")
      (value "100nF 25V")
      (footprint "eagle-import:0201")
      (fields
        (field (name "HQ_PART") "CA0183221")
        (field (name "LCSC_PART") "C76939")
        (field (name "MANUFACTURER") "Samsung")
      )
      (libsource (lib "eagle-import") (part "100NF-25V-0201"))
    )
    (comp (ref "C24")
      (value "100nF 25V")
      (footprint "eagle-import:0201")
      (fields
        (field (name "HQ_PART") "CA0183221")
        (field (name "LCSC_PART") "C76939")
        (field (name "MANUFACTURER") "Samsung")
      )
      (libsource (lib "eagle-import") (part "100NF-25V-0201"))
    )
    (comp (ref "C25")
      (value "100nF 25V")
      (footprint "eagle-import:0201")
      (fields
        (field (name "HQ_PART") "CA0183221")
        (field (name "LCSC_PART") "C76939")
        (field (name "MANUFACTURER") "Samsung")
      )
      (libsource (lib "eagle-import") (part "100NF-25V-0201"))
    )
    (comp (ref "C26")
      (value "4.7uF 10V")
      (footprint "eagle-import:0402")
      (fields (field (name "LCSC_PART") "C368809"))
      (libsource (lib "eagle-import") (part "4.7UF-10V0402"))
    )
    (comp (ref "C27")
      (value "100nF 25V")
      (footprint "eagle-import:0201")
      (fields
        (field (name "HQ_PART") "CA0183221")
        (field (name "LCSC_PART") "C76939")
        (field (name "MANUFACTURER") "Samsung")
      )
      (libsource (lib "eagle-import") (part "100NF-25V-0201"))
    )
    (comp (ref "C176")
      (value "100nF 25V")
      (footprint "eagle-import:0201")
      (fields
        (field (name "HQ_PART") "CA0183221")
        (field (name "LCSC_PART") "C76939")
        (field (name "MANUFACTURER") "Samsung")
      )
      (libsource (lib "eagle-import") (part "100NF-25V-0201"))
    )
    (comp (ref "C177")
      (value "15pF 50V")
      (footprint "eagle-import:0201")
      (fields
        (field (name "HQ_PART") "CA0136888")
        (field (name "LCSC_PART") "C22374851")
        (field (name "MANUFACTURER") "Yageo")
      )
      (libsource (lib "eagle-import") (part "15PF-50V0201"))
    )
    (comp (ref "C178")
      (value "15pF 50V")
      (footprint "eagle-import:0201")
      (fields
        (field (name "HQ_PART") "CA0136888")
        (field (name "LCSC_PART") "C22374851")
        (field (name "MANUFACTURER") "Yageo")
      )
      (libsource (lib "eagle-import") (part "15PF-50V0201"))
    )
    (comp (ref "C179")
      (value "1uF 10V")
      (footprint "eagle-import:0201")
      (fields (field (name "LCSC_PART") "C76935"))
      (libsource (lib "eagle-import") (part "1UF-10V0201"))
    )
    (comp (ref "C180")
      (value "100nF 25V")
      (footprint "eagle-import:0201")
      (fields
        (field (name "HQ_PART") "CA0183221")
        (field (name "LCSC_PART") "C76939")
        (field (name "MANUFACTURER") "Samsung")
      )
      (libsource (lib "eagle-import") (part "100NF-25V-0201"))
    )
    (comp (ref "C181")
      (value "100nF 25V")
      (footprint "eagle-import:0201")
      (fields
        (field (name "HQ_PART") "CA0183221")
        (field (name "LCSC_PART") "C76939")
        (field (name "MANUFACTURER") "Samsung")
      )
      (libsource (lib "eagle-import") (part "100NF-25V-0201"))
    )
    (comp (ref "C182")
      (value "100nF 25V")
      (footprint "eagle-import:0201")
      (fields
        (field (name "HQ_PART") "CA0183221")
        (field (name "LCSC_PART") "C76939")
        (field (name "MANUFACTURER") "Samsung")
      )
      (libsource (lib "eagle-import") (part "100NF-25V-0201"))
    )
    (comp (ref "C184")
      (value "100nF 25V")
      (footprint "eagle-import:0201")
      (fields
        (field (name "HQ_PART") "CA0183221")
        (field (name "LCSC_PART") "C76939")
        (field (name "MANUFACTURER") "Samsung")
      )
      (libsource (lib "eagle-import") (part "100NF-25V-0201"))
    )
    (comp (ref "C185")
      (value "100nF 25V")
      (footprint "eagle-import:0201")
      (fields
        (field (name "HQ_PART") "CA0183221")
        (field (name "LCSC_PART") "C76939")
        (field (name "MANUFACTURER") "Samsung")
      )
      (libsource (lib "eagle-import") (part "100NF-25V-0201"))
    )
    (comp (ref "C186")
      (value "100nF 25V")
      (footprint "eagle-import:0201")
      (fields
        (field (name "HQ_PART") "CA0183221")
        (field (name "LCSC_PART") "C76939")
        (field (name "MANUFACTURER") "Samsung")
      )
      (libsource (lib "eagle-import") (part "100NF-25V-0201"))
    )
    (comp (ref "C187")
      (value "100nF 25V")
      (footprint "eagle-import:0201")
      (fields
        (field (name "HQ_PART") "CA0183221")
        (field (name "LCSC_PART") "C76939")
        (field (name "MANUFACTURER") "Samsung")
      )
      (libsource (lib "eagle-import") (part "100NF-25V-0201"))
    )
    (comp (ref "C188")
      (value "100nF 25V")
      (footprint "eagle-import:0201")
      (fields
        (field (name "HQ_PART") "CA0183221")
        (field (name "LCSC_PART") "C76939")
        (field (name "MANUFACTURER") "Samsung")
      )
      (libsource (lib "eagle-import") (part "100NF-25V-0201"))
    )
    (comp (ref "C189")
      (value "100nF 25V")
      (footprint "eagle-import:0201")
      (fields
        (field (name "HQ_PART") "CA0183221")
        (field (name "LCSC_PART") "C76939")
        (field (name "MANUFACTURER") "Samsung")
      )
      (libsource (lib "eagle-import") (part "100NF-25V-0201"))
    )
    (comp (ref "C190")
      (value "100nF 25V")
      (footprint "eagle-import:0201")
      (fields
        (field (name "HQ_PART") "CA0183221")
        (field (name "LCSC_PART") "C76939")
        (field (name "MANUFACTURER") "Samsung")
      )
      (libsource (lib "eagle-import") (part "100NF-25V-0201"))
    )
    (comp (ref "C191")
      (value "100nF 25V")
      (footprint "eagle-import:0201")
      (fields
        (field (name "HQ_PART") "CA0183221")
        (field (name "LCSC_PART") "C76939")
        (field (name "MANUFACTURER") "Samsung")
      )
      (libsource (lib "eagle-import") (part "100NF-25V-0201"))
    )
    (comp (ref "C192")
      (value "100nF 25V")
      (footprint "eagle-import:0201")
      (fields
        (field (name "HQ_PART") "CA0183221")
        (field (name "LCSC_PART") "C76939")
        (field (name "MANUFACTURER") "Samsung")
      )
      (libsource (lib "eagle-import") (part "100NF-25V-0201"))
    )
    (comp (ref "C193")
      (value "100nF 25V")
      (footprint "eagle-import:0201")
      (fields
        (field (name "HQ_PART") "CA0183221")
        (field (name "LCSC_PART") "C76939")
        (field (name "MANUFACTURER") "Samsung")
      )
      (libsource (lib "eagle-import") (part "100NF-25V-0201"))
    )
    (comp (ref "C194")
      (value "100nF 25V")
      (footprint "eagle-import:0201")
      (fields
        (field (name "HQ_PART") "CA0183221")
        (field (name "LCSC_PART") "C76939")
        (field (name "MANUFACTURER") "Samsung")
      )
      (libsource (lib "eagle-import") (part "100NF-25V-0201"))
    )
    (comp (ref "C195")
      (value "100nF 25V")
      (footprint "eagle-import:0201")
      (fields
        (field (name "HQ_PART") "CA0183221")
        (field (name "LCSC_PART") "C76939")
        (field (name "MANUFACTURER") "Samsung")
      )
      (libsource (lib "eagle-import") (part "100NF-25V-0201"))
    )
    (comp (ref "IC26")
      (value "RP2354B")
      (footprint "eagle-import:QFN80-10X10")
      (fields (field (name "LCSC_PART") "C39843328") (field (name "MANUFACTURER") "Raspberry Pi "))
      (libsource (lib "eagle-import") (part "RP235XB"))
    )
    (comp (ref "IC27")
      (value "W25Q128JVPIQ")
      (footprint "eagle-import:SON127P600X500X75-8N")
      (fields
        (field (name "HQ_PART") "IC0150933")
        (field (name "LCSC_PART") "C190862")
        (field (name "MANUFACTURER") "Winbond")
      )
      (libsource (lib "eagle-import") (part "W25Q128JVP"))
    )
    (comp (ref "IC28")
      (value "MCP6001RT-I/OT")
      (footprint "eagle-import:SOT23-5")
      (fields
        (field (name "HQ_PART") "IC0119727")
        (field (name "LCSC_PART") "C154973")
        (field (name "MANUFACTURER") "MICROCHIP")
      )
      (libsource (lib "eagle-import") (part "MCP6001RT"))
    )
    (comp (ref "L1")
      (value "3.3uH")
      (footprint "eagle-import:0805")
      (fields
        (field (name "HQ_PART") "IN47489734")
        (field (name "LCSC_PART") "C42411119")
        (field (name "MANUFACTURER") "Abracon LLC")
      )
      (libsource (lib "eagle-import") (part "3.3UH0805"))
    )
    (comp (ref "R24")
      (value "10K 1%")
      (footprint "eagle-import:0201")
      (fields
        (field (name "PACKAGE") "0201")
        (field (name "HQ_PART") "RE0208620")
        (field (name "LCSC_PART") "C473048")
        (field (name "MANUFACTURER") "FH")
      )
      (libsource (lib "eagle-import") (part "10K-1%0201"))
    )
    (comp (ref "R25")
      (value "27R 1%")
      (footprint "eagle-import:0201")
      (fields
        (field (name "PACKAGE") "0201")
        (field (name "HQ_PART") "RE0209327 ")
        (field (name "LCSC_PART") "C473051")
        (field (name "MANUFACTURER") "FH")
      )
      (libsource (lib "eagle-import") (part "27R-1%0201"))
    )
    (comp (ref "R26")
      (value "27R 1%")
      (footprint "eagle-import:0201")
      (fields
        (field (name "PACKAGE") "0201")
        (field (name "HQ_PART") "RE0209327 ")
        (field (name "LCSC_PART") "C473051")
        (field (name "MANUFACTURER") "FH")
      )
      (libsource (lib "eagle-import") (part "27R-1%0201"))
    )
    (comp (ref "R27")
      (value "33R 1%")
      (footprint "eagle-import:0402")
      (fields
        (field (name "PACKAGE") "0402")
        (field (name "HQ_PART") "RE0368295")
        (field (name "LCSC_PART") "C25105")
        (field (name "MANUFACTURER") "ROHM")
      )
      (libsource (lib "eagle-import") (part "33R-1%0402"))
    )
    (comp (ref "R28")
      (value "0R 1%")
      (footprint "eagle-import:0402")
      (fields
        (field (name "PACKAGE") "0402")
        (field (name "HQ_PART") "RE0250181")
        (field (name "LCSC_PART") "C17168")
        (field (name "MANUFACTURER") "YAGEO")
      )
      (libsource (lib "eagle-import") (part "0R0402"))
    )
    (comp (ref "R29")
      (value "0R 1%")
      (footprint "eagle-import:0402")
      (fields
        (field (name "PACKAGE") "0402")
        (field (name "HQ_PART") "RE0250181")
        (field (name "LCSC_PART") "C17168")
        (field (name "MANUFACTURER") "YAGEO")
      )
      (libsource (lib "eagle-import") (part "0R0402"))
    )
    (comp (ref "R209")
      (value "DNI")
      (footprint "eagle-import:R0201")
      (libsource (lib "eagle-import") (part "R0201"))
    )
    (comp (ref "R210")
      (value "1K 1%")
      (footprint "eagle-import:0201")
      (fields
        (field (name "HQ_PART") "RE0015967")
        (field (name "LCSC_PART") "C270365")
        (field (name "MANUFACTURER") "Yageo")
      )
      (libsource (lib "eagle-import") (part "1K-1%0201"))
    )
    (comp (ref "R211")
      (value "1K 1%")
      (footprint "eagle-import:0201")
      (fields
        (field (name "HQ_PART") "RE0015967")
        (field (name "LCSC_PART") "C270365")
        (field (name "MANUFACTURER") "Yageo")
      )
      (libsource (lib "eagle-import") (part "1K-1%0201"))
    )
    (comp (ref "R212")
      (value "4.7K 1%")
      (footprint "eagle-import:0201")
      (fields
        (field (name "HQ_PART") "RE0208670")
        (field (name "LCSC_PART") "C270346")
        (field (name "MANUFACTURER") "RALEC")
      )
      (libsource (lib "eagle-import") (part "4.7K-1%0201"))
    )
    (comp (ref "REF1")
      (value "LM4040x30")
      (footprint "eagle-import:SOT23")
      (fields
        (field (name "HQ_PART") "IC0022950")
        (field (name "LCSC_PART") "C460604")
        (field (name "MANUFACTURER") "DIODES")
      )
      (libsource (lib "eagle-import") (part "LM4040BXX"))
    )
    (comp (ref "SW1")
      (value "B3U-1000P")
      (footprint "eagle-import:B3U-1000P")
      (fields
        (field (name "HQ_PART") "SW0036094 ")
        (field (name "LCSC_PART") "C231329")
        (field (name "MANUFACTURER") "Omron")
      )
      (libsource (lib "eagle-import") (part "B3U-1000P"))
    )
    (comp (ref "SW2")
      (value "B3U-1000P")
      (footprint "eagle-import:B3U-1000P")
      (fields
        (field (name "HQ_PART") "SW0036094 ")
        (field (name "LCSC_PART") "C231329")
        (field (name "MANUFACTURER") "Omron")
      )
      (libsource (lib "eagle-import") (part "B3U-1000P"))
    )
    (comp (ref "VREF")
      (value "TESTPOINT")
      (footprint "eagle-import:TP")
      (libsource (lib "eagle-import") (part "TP"))
    )
    (comp (ref "X1")
      (value "12MHz")
      (footprint "eagle-import:WE-XTAL_CFPX-180")
      (fields
        (field (name "HQ_PART") "CR0250194")
        (field (name "LCSC_PART") "C20625731")
        (field (name "MANUFACTURER") "TKD")
      )
      (libsource (lib "eagle-import") (part "CRYSTAL-3225X322512MSB4SI"))
    )
    (comp (ref "C233")
      (value "100nF")
      (footprint "eagle-import:0201")
      (libsource (lib "eagle-import") (part "C-0201"))
    )
    (comp (ref "C234")
      (value "100nF")
      (footprint "eagle-import:0201")
      (libsource (lib "eagle-import") (part "C-0201"))
    )
    (comp (ref "C235")
      (value "100nF")
      (footprint "eagle-import:0201")
      (libsource (lib "eagle-import") (part "C-0201"))
    )
    (comp (ref "C236")
      (value "33pF")
      (footprint "eagle-import:0201")
      (libsource (lib "eagle-import") (part "C-0201"))
    )
    (comp (ref "C237")
      (value "22uF 25V")
      (footprint "eagle-import:C1206")
      (libsource (lib "eagle-import") (part "C-1206"))
    )
    (comp (ref "C238")
      (value "22uF - 10V")
      (footprint "eagle-import:C1206")
      (libsource (lib "eagle-import") (part "C-1206"))
    )
    (comp (ref "C239")
      (value "22uF - 10V")
      (footprint "eagle-import:C1206")
      (libsource (lib "eagle-import") (part "C-1206"))
    )
    (comp (ref "C252")
      (value "330uF 50V")
      (footprint "eagle-import:10X10.5(DXL)")
      (fields (field (name "LCSC_PART") "C2895745") (field (name "MPN") "EEE-FT1H331AP"))
      (libsource (lib "eagle-import") (part "330UF-50V10X10.5(DXL)"))
    )
    (comp (ref "C253")
      (value "330uF 50V")
      (footprint "eagle-import:10X10.5(DXL)")
      (fields (field (name "LCSC_PART") "C2895745") (field (name "MPN") "EEE-FT1H331AP"))
      (libsource (lib "eagle-import") (part "330UF-50V10X10.5(DXL)"))
    )
    (comp (ref "C254")
      (value "330uF 50V")
      (footprint "eagle-import:10X10.5(DXL)")
      (fields (field (name "LCSC_PART") "C2895745") (field (name "MPN") "EEE-FT1H331AP"))
      (libsource (lib "eagle-import") (part "330UF-50V10X10.5(DXL)"))
    )
    (comp (ref "C255")
      (value "330uF 50V")
      (footprint "eagle-import:10X10.5(DXL)")
      (fields (field (name "LCSC_PART") "C2895745") (field (name "MPN") "EEE-FT1H331AP"))
      (libsource (lib "eagle-import") (part "330UF-50V10X10.5(DXL)"))
    )
    (comp (ref "C256")
      (value "330uF 50V")
      (footprint "eagle-import:10X10.5(DXL)")
      (fields (field (name "LCSC_PART") "C2895745") (field (name "MPN") "EEE-FT1H331AP"))
      (libsource (lib "eagle-import") (part "330UF-50V10X10.5(DXL)"))
    )
    (comp (ref "C257")
      (value "330uF 50V")
      (footprint "eagle-import:10X10.5(DXL)")
      (fields (field (name "LCSC_PART") "C2895745") (field (name "MPN") "EEE-FT1H331AP"))
      (libsource (lib "eagle-import") (part "330UF-50V10X10.5(DXL)"))
    )
    (comp (ref "C264")
      (value "22uF - 10V")
      (footprint "eagle-import:C1206")
      (libsource (lib "eagle-import") (part "C-1206"))
    )
    (comp (ref "C278")
      (value "22uF - 10V")
      (footprint "eagle-import:C1206")
      (libsource (lib "eagle-import") (part "C-1206"))
    )
    (comp (ref "D9")
      (value "SMBJ33A")
      (footprint "eagle-import:SMB")
      (libsource (lib "eagle-import") (part "DIODE-SMB"))
    )
    (comp (ref "D10")
      (value "SMBJ33A")
      (footprint "eagle-import:SMB")
      (libsource (lib "eagle-import") (part "DIODE-SMB"))
    )
    (comp (ref "D11")
      (value "SMBJ33A")
      (footprint "eagle-import:SMB")
      (libsource (lib "eagle-import") (part "DIODE-SMB"))
    )
    (comp (ref "F1")
      (value "2A")
      (footprint "eagle-import:FUSE_3544-2")
      (fields (field (name "MANUFACTURER") "Keystone"))
      (libsource (lib "eagle-import") (part "BLADE-FUSE"))
    )
    (comp (ref "F2")
      (value "15A")
      (footprint "eagle-import:FUSE_3544-2")
      (fields (field (name "MANUFACTURER") "Keystone"))
      (libsource (lib "eagle-import") (part "BLADE-FUSE"))
    )
    (comp (ref "F3")
      (value "15A")
      (footprint "eagle-import:FUSE_3544-2")
      (fields (field (name "MANUFACTURER") "Keystone"))
      (libsource (lib "eagle-import") (part "BLADE-FUSE"))
    )
    (comp (ref "H1")
      (value "MOUNT-PAD-ROUND3.3")
      (footprint "eagle-import:3,3-PAD")
      (libsource (lib "eagle-import") (part "MOUNT-PAD-ROUND3.3"))
    )
    (comp (ref "H2")
      (value "MOUNT-PAD-ROUND3.3")
      (footprint "eagle-import:3,3-PAD")
      (libsource (lib "eagle-import") (part "MOUNT-PAD-ROUND3.3"))
    )
    (comp (ref "H3")
      (value "MOUNT-PAD-ROUND3.3")
      (footprint "eagle-import:3,3-PAD")
      (libsource (lib "eagle-import") (part "MOUNT-PAD-ROUND3.3"))
    )
    (comp (ref "H4")
      (value "MOUNT-PAD-ROUND3.3")
      (footprint "eagle-import:3,3-PAD")
      (libsource (lib "eagle-import") (part "MOUNT-PAD-ROUND3.3"))
    )
    (comp (ref "IC40")
      (value "MP2315GJ-Z")
      (footprint "eagle-import:SOT65P280X110-8N")
      (fields
        (field (name "HQ_PART") "IC0339027")
        (field (name "LCSC_PART") "C45889")
        (field (name "MANUFACTURER") "MPS")
      )
      (libsource (lib "eagle-import") (part "MP2315TSOT23-8"))
    )
    (comp (ref "J8")
      (value "691244510006")
      (footprint "eagle-import:691244510006")
      (libsource (lib "eagle-import") (part "691244510006"))
    )
    (comp (ref "L11")
      (value "4.2uH")
      (footprint "eagle-import:SRR5228A")
      (libsource (lib "eagle-import") (part "L"))
    )
    (comp (ref "R241")
      (value "499K")
      (footprint "eagle-import:R0201")
      (libsource (lib "eagle-import") (part "R0201"))
    )
    (comp (ref "R242")
      (value "7.5K")
      (footprint "eagle-import:R0201")
      (libsource (lib "eagle-import") (part "R0201"))
    )
    (comp (ref "R243")
      (value "10R")
      (footprint "eagle-import:R0201")
      (libsource (lib "eagle-import") (part "R0201"))
    )
    (comp (ref "R244")
      (value "100K")
      (footprint "eagle-import:R0201")
      (libsource (lib "eagle-import") (part "R0201"))
    )
    (comp (ref "RFB3")
      (value "40.2K")
      (footprint "eagle-import:R0201")
      (libsource (lib "eagle-import") (part "R0201"))
    )
    (comp (ref "RFB4")
      (value "12.7K 1%")
      (footprint "eagle-import:R0201")
      (libsource (lib "eagle-import") (part "R0201"))
    )
    (comp (ref "RT1")
      (value "33K")
      (footprint "eagle-import:R0201")
      (libsource (lib "eagle-import") (part "R0201"))
    )
    (comp (ref "VO3")
      (value "TESTPOINT")
      (footprint "eagle-import:TP")
      (libsource (lib "eagle-import") (part "TP"))
    )
    (comp (ref "VO5A")
      (value "TESTPOINT")
      (footprint "eagle-import:TP")
      (libsource (lib "eagle-import") (part "TP"))
    )
    (comp (ref "VO5B")
      (value "TESTPOINT")
      (footprint "eagle-import:TP")
      (libsource (lib "eagle-import") (part "TP"))
    )
    (comp (ref "C183")
      (value "100nF 25V")
      (footprint "eagle-import:0201")
      (fields
        (field (name "HQ_PART") "CA0183221")
        (field (name "LCSC_PART") "C76939")
        (field (name "MANUFACTURER") "Samsung")
      )
      (libsource (lib "eagle-import") (part "100NF-25V-0201"))
    )
    (comp (ref "D12")
      (value "HDMIULC6-4SC6Y")
      (footprint "eagle-import:SOT23-6")
      (libsource (lib "eagle-import") (part "HDMIULC6-4SC6Y"))
    )
    (comp (ref "IC29")
      (value "CAT24C256HU4IGT3")
      (footprint "eagle-import:SON50P300X200X50-9T130X140N")
      (fields
        (field (name "HQ_PART") "IC0066897")
        (field (name "LCSC_PART") "C233771")
        (field (name "MANUFACTURER") "ON")
      )
      (libsource (lib "eagle-import") (part "CAT24C256-HU4"))
    )
    (comp (ref "R207")
      (value "3.3K 1%")
      (footprint "eagle-import:_0603X4-1206")
      (fields
        (field (name "HQ_PART") "RE0093863")
        (field (name "LCSC_PART") "C1734380")
        (field (name "MANUFACTURER") "Yageo")
      )
      (libsource (lib "eagle-import") (part "3.3K-1%_ARRAY0603X4-1206"))
    )
    (comp (ref "R213")
      (value "NC")
      (footprint "eagle-import:R0201")
      (libsource (lib "eagle-import") (part "R0201"))
    )
    (comp (ref "R214")
      (value "4.7K 1%")
      (footprint "eagle-import:0201")
      (fields
        (field (name "HQ_PART") "RE0208670")
        (field (name "LCSC_PART") "C270346")
        (field (name "MANUFACTURER") "RALEC")
      )
      (libsource (lib "eagle-import") (part "4.7K-1%0201"))
    )
    (comp (ref "C6")
      (value "1uF 10V")
      (footprint "eagle-import:0201")
      (fields (field (name "LCSC_PART") "C76935"))
      (libsource (lib "eagle-import") (part "1UF-10V0201"))
    )
    (comp (ref "C16")
      (value "1uF 10V")
      (footprint "eagle-import:0201")
      (fields (field (name "LCSC_PART") "C76935"))
      (libsource (lib "eagle-import") (part "1UF-10V0201"))
    )
    (comp (ref "C39")
      (value "1uF 50V")
      (footprint "eagle-import:0603")
      (fields (field (name "LCSC_PART") "C15849"))
      (libsource (lib "eagle-import") (part "1UF-50V0603"))
    )
    (comp (ref "C40")
      (value "1NF-2KV")
      (footprint "eagle-import:1206")
      (fields
        (field (name "PACKAGE") "1206")
        (field (name "HQ_PART") "CA0134884")
        (field (name "LCSC_PART") "C9196")
        (field (name "MANUFACTURER") "KEMET")
      )
      (libsource (lib "eagle-import") (part "1NF-2KV"))
    )
    (comp (ref "C41")
      (value "4.7uF 25V")
      (footprint "eagle-import:0402")
      (fields
        (field (name "HQ_PART") "ZHLM0023346")
        (field (name "LCSC_PART") "C22367824")
        (field (name "MANUFACTURER") "Murata")
      )
      (libsource (lib "eagle-import") (part "4.7UF-25V0402"))
    )
    (comp (ref "C42")
      (value "10nF 50V")
      (footprint "eagle-import:0201")
      (fields (field (name "LCSC_PART") "C5142551"))
      (libsource (lib "eagle-import") (part "10NF-50V-0201"))
    )
    (comp (ref "C43")
      (value "100pF 50V")
      (footprint "eagle-import:0402")
      (fields
        (field (name "HQ_PART") "CA0183732")
        (field (name "MANUFACTURER") "TDK ")
        (field (name "MPN") "CGA2B2C0G1H101JT0Y0F")
      )
      (libsource (lib "eagle-import") (part "100PF-50V-0402"))
    )
    (comp (ref "C44")
      (value "10nF 50V")
      (footprint "eagle-import:0201")
      (fields (field (name "LCSC_PART") "C5142551"))
      (libsource (lib "eagle-import") (part "10NF-50V-0201"))
    )
    (comp (ref "C45")
      (value "100nF 50V")
      (footprint "eagle-import:0402")
      (fields (field (name "LCSC_PART") "C307331"))
      (libsource (lib "eagle-import") (part "100NF-50V-0402"))
    )
    (comp (ref "C46")
      (value "100nF 50V")
      (footprint "eagle-import:0402")
      (fields (field (name "LCSC_PART") "C307331"))
      (libsource (lib "eagle-import") (part "100NF-50V-0402"))
    )
    (comp (ref "C47")
      (value "10uF 50V")
      (footprint "eagle-import:0805")
      (fields (field (name "LCSC_PART") "C440198"))
      (libsource (lib "eagle-import") (part "10UF-50V-0805"))
    )
    (comp (ref "C48")
      (value "10uF 50V")
      (footprint "eagle-import:0805")
      (fields (field (name "LCSC_PART") "C440198"))
      (libsource (lib "eagle-import") (part "10UF-50V-0805"))
    )
    (comp (ref "C49")
      (value "1uF 50V")
      (footprint "eagle-import:0805")
      (fields
        (field (name "HQ_PART") "CA0182352")
        (field (name "LCSC_PART") "C28323")
        (field (name "MANUFACTURER") "TDK")
      )
      (libsource (lib "eagle-import") (part "1UF-50V0805"))
    )
    (comp (ref "C50")
      (value "100uF 50V")
      (footprint "eagle-import:6.3X7.7(DXL)")
      (fields
        (field (name "HQ_PART") "ZHLM0353527")
        (field (name "LCSC_PART") "C3151829")
        (field (name "MANUFACTURER") "ROQANG")
      )
      (libsource (lib "eagle-import") (part "100UF-50V6.3X7.7(DXL)"))
    )
    (comp (ref "C51")
      (value "1uF 50V")
      (footprint "eagle-import:0402")
      (fields (field (name "LCSC_PART") "C1518208"))
      (libsource (lib "eagle-import") (part "1UF-50V0402"))
    )
    (comp (ref "C52")
      (value "10uF 50V")
      (footprint "eagle-import:0805")
      (fields (field (name "LCSC_PART") "C440198"))
      (libsource (lib "eagle-import") (part "10UF-50V-0805"))
    )
    (comp (ref "C53")
      (value "10uF 50V")
      (footprint "eagle-import:0805")
      (fields (field (name "LCSC_PART") "C440198"))
      (libsource (lib "eagle-import") (part "10UF-50V-0805"))
    )
    (comp (ref "C54")
      (value "10uF 50V")
      (footprint "eagle-import:0805")
      (fields (field (name "LCSC_PART") "C440198"))
      (libsource (lib "eagle-import") (part "10UF-50V-0805"))
    )
    (comp (ref "C55")
      (value "100nF 25V")
      (footprint "eagle-import:0201")
      (fields
        (field (name "HQ_PART") "CA0183221")
        (field (name "LCSC_PART") "C76939")
        (field (name "MANUFACTURER") "Samsung")
      )
      (libsource (lib "eagle-import") (part "100NF-25V-0201"))
    )
    (comp (ref "C196")
      (value "100nF 50V")
      (footprint "eagle-import:0402")
      (fields (field (name "LCSC_PART") "C307331"))
      (libsource (lib "eagle-import") (part "100NF-50V-0402"))
    )
    (comp (ref "C214")
      (value "1uF 50V")
      (footprint "eagle-import:0402")
      (fields (field (name "PACKAGE") "0402") (field (name "LCSC_PART") "C1518208"))
      (libsource (lib "eagle-import") (part "1UF-50V0402"))
    )
    (comp (ref "C215")
      (value "2.2nF 50V")
      (footprint "eagle-import:0402")
      (fields
        (field (name "PACKAGE") "0402")
        (field (name "HQ_PART") "CA0176616")
        (field (name "MANUFACTURER") "WALSIN")
        (field (name "MPN") "0402B222K500CT")
      )
      (libsource (lib "eagle-import") (part "2.2NF-50V-0402"))
    )
    (comp (ref "C216")
      (value "2.2nF 50V")
      (footprint "eagle-import:0402")
      (fields
        (field (name "PACKAGE") "0402")
        (field (name "HQ_PART") "CA0176616")
        (field (name "MANUFACTURER") "WALSIN")
        (field (name "MPN") "0402B222K500CT")
      )
      (libsource (lib "eagle-import") (part "2.2NF-50V-0402"))
    )
    (comp (ref "C217")
      (value "10uF 50V")
      (footprint "eagle-import:0805")
      (fields (field (name "LCSC_PART") "C440198"))
      (libsource (lib "eagle-import") (part "10UF-50V-0805"))
    )
    (comp (ref "C218")
      (value "330uF 50V")
      (footprint "eagle-import:10X10.5(DXL)")
      (fields (field (name "LCSC_PART") "C2895745") (field (name "MPN") "EEE-FT1H331AP"))
      (libsource (lib "eagle-import") (part "330UF-50V10X10.5(DXL)"))
    )
    (comp (ref "IC9")
      (value "STUSB4710AQ1TR")
      (footprint "eagle-import:QFN50P300X300X55-16N")
      (libsource (lib "eagle-import") (part "STUSB4710AQ1TR"))
    )
    (comp (ref "IC12")
      (value "TPS552882")
      (footprint "eagle-import:RPM0026A-MFG")
      (fields
        (field (name "MANUFACTURER_PART_NUMBER") "TPS552882QRPMRQ1")
        (field (name "COPYRIGHT") "Copyright (C) 2025 Ultra Librarian. All rights reserved.")
      )
      (libsource (lib "eagle-import") (part "TPS552882"))
    )
    (comp (ref "IC13")
      (value "INA219BIDCNT")
      (footprint "eagle-import:SOT23-8")
      (fields
        (field (name "HQ_PART") "IC0063216")
        (field (name "LCSC_PART") "C2653868")
        (field (name "MANUFACTURER") "Texas Instruments")
      )
      (libsource (lib "eagle-import") (part "INA219BIDCNT"))
    )
    (comp (ref "L2")
      (value "4.7uH")
      (footprint "eagle-import:WE-PD_1280")
      (libsource (lib "eagle-import") (part "WE-PD_1280_74477004"))
    )
    (comp (ref "PORT1")
      (value "632722100213")
      (footprint "eagle-import:632722100213")
      (libsource (lib "eagle-import") (part "USB-C-POWERONLY"))
    )
    (comp (ref "R5")
      (value "200K 1%")
      (footprint "eagle-import:0201")
      (fields (field (name "LCSC_PART") "C270357"))
      (libsource (lib "eagle-import") (part "200K-1%0201"))
    )
    (comp (ref "R11")
      (value "12.7K 1%")
      (footprint "eagle-import:0201")
      (fields
        (field (name "LCSC_PART") "C423755")
        (field (name "MANUFACTURER") "UNI-ROYAL")
        (field (name "MPN") "0201WMF1272TEE")
      )
      (libsource (lib "eagle-import") (part "12.7K-1%0201"))
    )
    (comp (ref "R46")
      (value "4.64K 1%")
      (footprint "eagle-import:0201")
      (fields
        (field (name "LCSC_PART") "C166186")
        (field (name "MANUFACTURER") " RALEC")
        (field (name "MPN") "RTT014641FTH")
      )
      (libsource (lib "eagle-import") (part "4.64K-1%-0201"))
    )
    (comp (ref "R47")
      (value "4.64K 1%")
      (footprint "eagle-import:0201")
      (fields
        (field (name "LCSC_PART") "C166186")
        (field (name "MANUFACTURER") " RALEC")
        (field (name "MPN") "RTT014641FTH")
      )
      (libsource (lib "eagle-import") (part "4.64K-1%-0201"))
    )
    (comp (ref "R48")
      (value "8.87K 1%")
      (footprint "eagle-import:0201")
      (fields
        (field (name "LCSC_PART") "C423413")
        (field (name "MANUFACTURER") " UNI-ROYAL")
        (field (name "MPN") "0201WMF8871TEE")
      )
      (libsource (lib "eagle-import") (part "8.87K-1%-0201"))
    )
    (comp (ref "R49")
      (value "30.9K 1%")
      (footprint "eagle-import:0201")
      (fields (field (name "LCSC_PART") "C364366"))
      (libsource (lib "eagle-import") (part "30.9K-1%0201"))
    )
    (comp (ref "R50")
      (value "1M 1%")
      (footprint "eagle-import:1206")
      (fields
        (field (name "PACKAGE") "1206")
        (field (name "HQ_PART") "RE0188103")
        (field (name "LCSC_PART") "C17927")
        (field (name "MANUFACTURER") "Uniohm")
      )
      (libsource (lib "eagle-import") (part "1M-1%1206"))
    )
    (comp (ref "R51")
      (value "100K 1%")
      (footprint "eagle-import:0201")
      (fields (field (name "LCSC_PART") "C270364"))
      (libsource (lib "eagle-import") (part "100K-1%0201"))
    )
    (comp (ref "R52")
      (value "10K 1%")
      (footprint "eagle-import:0402")
      (fields
        (field (name "HQ_PART") "RE0207399")
        (field (name "LCSC_PART") "C25744")
        (field (name "MANUFACTURER") "ROHM")
      )
      (libsource (lib "eagle-import") (part "10K-1%0402"))
    )
    (comp (ref "R53")
      (value "10K 1%")
      (footprint "eagle-import:0402")
      (fields
        (field (name "HQ_PART") "RE0207399")
        (field (name "LCSC_PART") "C25744")
        (field (name "MANUFACTURER") "ROHM")
      )
      (libsource (lib "eagle-import") (part "10K-1%0402"))
    )
    (comp (ref "R54")
      (value "10K 1%")
      (footprint "eagle-import:0201")
      (fields
        (field (name "HQ_PART") "RE0208620")
        (field (name "LCSC_PART") "C473048")
        (field (name "MANUFACTURER") "FH")
      )
      (libsource (lib "eagle-import") (part "10K-1%0201"))
    )
    (comp (ref "R55")
      (value "10K 1%")
      (footprint "eagle-import:0402")
      (fields
        (field (name "HQ_PART") "RE0207399")
        (field (name "LCSC_PART") "C25744")
        (field (name "MANUFACTURER") "ROHM")
      )
      (libsource (lib "eagle-import") (part "10K-1%0402"))
    )
    (comp (ref "R57")
      (value "0.010R 1%")
      (footprint "eagle-import:2512")
      (fields
        (field (name "LCSC_PART") "C127692")
        (field (name "MANUFACTURER") " UNI-ROYAL")
        (field (name "MPN") "25121WF100MT4E")
      )
      (libsource (lib "eagle-import") (part "0.010R-1%-2512"))
    )
    (comp (ref "R58")
      (value "0R 1%")
      (footprint "eagle-import:0201")
      (fields
        (field (name "HA_PART") "RE0015349")
        (field (name "LCSC_PART") "C106227")
        (field (name "MANUFACTURER") "Yageo")
      )
      (libsource (lib "eagle-import") (part "0R0201"))
    )
    (comp (ref "R59")
      (value "49.9K 1%")
      (footprint "eagle-import:0201")
      (fields
        (field (name "HQ_PART") "RE0461584")
        (field (name "LCSC_PART") "C138136")
        (field (name "MANUFACTURER") "Yageo")
      )
      (libsource (lib "eagle-import") (part "49.9K-1%0201"))
    )
    (comp (ref "R60")
      (value "20K 1%")
      (footprint "eagle-import:0201")
      (fields (field (name "LCSC_PART") "C473466"))
      (libsource (lib "eagle-import") (part "20K-1%0201"))
    )
    (comp (ref "R61")
      (value "150K")
      (footprint "eagle-import:R0201")
      (libsource (lib "eagle-import") (part "R0201"))
    )
    (comp (ref "R62")
      (value "15K 1%")
      (footprint "eagle-import:0201")
      (fields (field (name "LCSC_PART") "C295774"))
      (libsource (lib "eagle-import") (part "15K-1%0201"))
    )
    (comp (ref "R63")
      (value "0.010R 1%")
      (footprint "eagle-import:2512")
      (fields
        (field (name "LCSC_PART") "C127692")
        (field (name "MANUFACTURER") " UNI-ROYAL")
        (field (name "MPN") "25121WF100MT4E")
      )
      (libsource (lib "eagle-import") (part "0.010R-1%-2512"))
    )
    (comp (ref "R64")
      (value "1R 1%")
      (footprint "eagle-import:0402")
      (fields
        (field (name "HQ_PART") "RE0322446")
        (field (name "MANUFACTURER") "RALEC")
        (field (name "MPN") "RTT021R00FTH")
      )
      (libsource (lib "eagle-import") (part "1R-1%0402"))
    )
    (comp (ref "R65")
      (value "1R 1%")
      (footprint "eagle-import:0402")
      (fields
        (field (name "HQ_PART") "RE0322446")
        (field (name "MANUFACTURER") "RALEC")
        (field (name "MPN") "RTT021R00FTH")
      )
      (libsource (lib "eagle-import") (part "1R-1%0402"))
    )
    (comp (ref "R228")
      (value "0R 1%")
      (footprint "eagle-import:0201")
      (fields
        (field (name "PACKAGE") "0201")
        (field (name "HA_PART") "RE0015349")
        (field (name "LCSC_PART") "C106227")
        (field (name "MANUFACTURER") "Yageo")
      )
      (libsource (lib "eagle-import") (part "0R0201"))
    )
    (comp (ref "R229")
      (value "0R 1%")
      (footprint "eagle-import:0201")
      (fields
        (field (name "PACKAGE") "0201")
        (field (name "HA_PART") "RE0015349")
        (field (name "LCSC_PART") "C106227")
        (field (name "MANUFACTURER") "Yageo")
      )
      (libsource (lib "eagle-import") (part "0R0201"))
    )
    (comp (ref "R230")
      (value "10K 1%")
      (footprint "eagle-import:0201")
      (fields
        (field (name "HQ_PART") "RE0208620")
        (field (name "LCSC_PART") "C473048")
        (field (name "MANUFACTURER") "FH")
      )
      (libsource (lib "eagle-import") (part "10K-1%0201"))
    )
    (comp (ref "R231")
      (value "1R 1%")
      (footprint "eagle-import:0603")
      (fields
        (field (name "PACKAGE") "0603")
        (field (name "HQ_PART") "RE0421839")
        (field (name "MANUFACTURER") "RALEC")
        (field (name "MPN") "RTT031R00FTP")
      )
      (libsource (lib "eagle-import") (part "1R-1%0603"))
    )
    (comp (ref "R232")
      (value "1R 1%")
      (footprint "eagle-import:0603")
      (fields
        (field (name "PACKAGE") "0603")
        (field (name "HQ_PART") "RE0421839")
        (field (name "MANUFACTURER") "RALEC")
        (field (name "MPN") "RTT031R00FTP")
      )
      (libsource (lib "eagle-import") (part "1R-1%0603"))
    )
    (comp (ref "T6")
      (value "DMP3013SFV")
      (footprint "eagle-import:POWERDI3333-8_UX_DIO-L")
      (fields (field (name "MANUFACTURER_PART_NUMBER") "DMP3013SFV-7"))
      (libsource (lib "eagle-import") (part "DMP3013SFV-7UX"))
    )
    (comp (ref "T7")
      (value "DMP3013SFV")
      (footprint "eagle-import:POWERDI3333-8_UX_DIO-L")
      (fields (field (name "MANUFACTURER_PART_NUMBER") "DMP3013SFV-7"))
      (libsource (lib "eagle-import") (part "DMP3013SFV-7UX"))
    )
    (comp (ref "T8")
      (value "DMP3013SFV")
      (footprint "eagle-import:POWERDI3333-8_UX_DIO-L")
      (fields (field (name "MANUFACTURER_PART_NUMBER") "DMP3013SFV-7"))
      (libsource (lib "eagle-import") (part "DMP3013SFV-7UX"))
    )
    (comp (ref "T9")
      (value "BSZ065N06")
      (footprint "eagle-import:POWERDI3333-8_UX_DIO-L")
      (fields
        (field (name "MANUFACTURER_PART_NUMBER") "IPZ40N04S5L7R4ATMA1")
        (field (name "COPYRIGHT") "Copyright (C) 2025 Ultra Librarian. All rights reserved.")
      )
      (libsource (lib "eagle-import") (part "IPZ40N04S5L7R4ATMA1"))
    )
    (comp (ref "T10")
      (value "BSZ065N06")
      (footprint "eagle-import:POWERDI3333-8_UX_DIO-L")
      (fields
        (field (name "MANUFACTURER_PART_NUMBER") "IPZ40N04S5L7R4ATMA1")
        (field (name "COPYRIGHT") "Copyright (C) 2025 Ultra Librarian. All rights reserved.")
      )
      (libsource (lib "eagle-import") (part "IPZ40N04S5L7R4ATMA1"))
    )
    (comp (ref "C2")
      (value "100nF 25V")
      (footprint "eagle-import:0201")
      (fields
        (field (name "HQ_PART") "CA0183221")
        (field (name "LCSC_PART") "C76939")
        (field (name "MANUFACTURER") "Samsung")
      )
      (libsource (lib "eagle-import") (part "100NF-25V-0201"))
    )
    (comp (ref "C3")
      (value "10uF 16V")
      (footprint "eagle-import:0603")
      (fields
        (field (name "HQ_PART") "CA0149236")
        (field (name "LCSC_PART") "C92487")
        (field (name "MANUFACTURER") "Murata")
      )
      (libsource (lib "eagle-import") (part "10UF-16V-0603"))
    )
    (comp (ref "C4")
      (value "10uF 16V")
      (footprint "eagle-import:0603")
      (fields
        (field (name "HQ_PART") "CA0149236")
        (field (name "LCSC_PART") "C92487")
        (field (name "MANUFACTURER") "Murata")
      )
      (libsource (lib "eagle-import") (part "10UF-16V-0603"))
    )
    (comp (ref "C5")
      (value "100uF 16V")
      (footprint "eagle-import:5X5.5(DXL)")
      (fields (field (name "LCSC_PART") "C2977550"))
      (libsource (lib "eagle-import") (part "100UF-16V5X5.5(DXL)"))
    )
    (comp (ref "C11")
      (value "1NF-2KV")
      (footprint "eagle-import:1206")
      (fields
        (field (name "PACKAGE") "1206")
        (field (name "HQ_PART") "CA0134884")
        (field (name "LCSC_PART") "C9196")
        (field (name "MANUFACTURER") "KEMET")
      )
      (libsource (lib "eagle-import") (part "1NF-2KV"))
    )
    (comp (ref "C17")
      (value "100nF 25V")
      (footprint "eagle-import:0201")
      (fields
        (field (name "HQ_PART") "CA0183221")
        (field (name "LCSC_PART") "C76939")
        (field (name "MANUFACTURER") "Samsung")
      )
      (libsource (lib "eagle-import") (part "100NF-25V-0201"))
    )
    (comp (ref "C18")
      (value "100nF 25V")
      (footprint "eagle-import:0201")
      (fields
        (field (name "HQ_PART") "CA0183221")
        (field (name "LCSC_PART") "C76939")
        (field (name "MANUFACTURER") "Samsung")
      )
      (libsource (lib "eagle-import") (part "100NF-25V-0201"))
    )
    (comp (ref "C82")
      (value "100nF 25V")
      (footprint "eagle-import:0201")
      (fields
        (field (name "HQ_PART") "CA0183221")
        (field (name "LCSC_PART") "C76939")
        (field (name "MANUFACTURER") "Samsung")
      )
      (libsource (lib "eagle-import") (part "100NF-25V-0201"))
    )
    (comp (ref "C83")
      (value "10uF 16V")
      (footprint "eagle-import:0603")
      (fields
        (field (name "HQ_PART") "CA0149236")
        (field (name "LCSC_PART") "C92487")
        (field (name "MANUFACTURER") "Murata")
      )
      (libsource (lib "eagle-import") (part "10UF-16V-0603"))
    )
    (comp (ref "C84")
      (value "10uF 16V")
      (footprint "eagle-import:0603")
      (fields
        (field (name "HQ_PART") "CA0149236")
        (field (name "LCSC_PART") "C92487")
        (field (name "MANUFACTURER") "Murata")
      )
      (libsource (lib "eagle-import") (part "10UF-16V-0603"))
    )
    (comp (ref "C85")
      (value "100uF 16V")
      (footprint "eagle-import:5X5.5(DXL)")
      (fields (field (name "LCSC_PART") "C2977550"))
      (libsource (lib "eagle-import") (part "100UF-16V5X5.5(DXL)"))
    )
    (comp (ref "D1")
      (value "GREEN")
      (footprint "eagle-import:LEDC1608X35N_FLAT-G")
      (libsource (lib "eagle-import") (part "CHIP-FLAT-G_0603-0.35MM"))
    )
    (comp (ref "D2")
      (value "RED")
      (footprint "eagle-import:LEDC1608X35N_FLAT-R")
      (libsource (lib "eagle-import") (part "CHIP-FLAT-R_0603-0.35MM"))
    )
    (comp (ref "D3")
      (value "GREEN")
      (footprint "eagle-import:LEDC1608X35N_FLAT-G")
      (libsource (lib "eagle-import") (part "CHIP-FLAT-G_0603-0.35MM"))
    )
    (comp (ref "D4")
      (value "RED")
      (footprint "eagle-import:LEDC1608X35N_FLAT-R")
      (libsource (lib "eagle-import") (part "CHIP-FLAT-R_0603-0.35MM"))
    )
    (comp (ref "IC1")
      (value "AP22653W6")
      (footprint "eagle-import:SOT23-6")
      (fields
        (field (name "HQ_PART") "PM0174903")
        (field (name "LCSC_PART") "C2158037")
        (field (name "MANUFACTURER") "Diodes Incorporated")
      )
      (libsource (lib "eagle-import") (part "AP22653W6"))
    )
    (comp (ref "IC4")
      (value "SN74LVC1G04DBVR")
      (footprint "eagle-import:SOT95P280X145-5N")
      (libsource (lib "eagle-import") (part "74LVC1G04"))
    )
    (comp (ref "IC5")
      (value "SN74LVC1G04DBVR")
      (footprint "eagle-import:SOT95P280X145-5N")
      (libsource (lib "eagle-import") (part "74LVC1G04"))
    )
    (comp (ref "IC8")
      (value "AP22653W6")
      (footprint "eagle-import:SOT23-6")
      (fields
        (field (name "HQ_PART") "PM0174903")
        (field (name "LCSC_PART") "C2158037")
        (field (name "MANUFACTURER") "Diodes Incorporated")
      )
      (libsource (lib "eagle-import") (part "AP22653W6"))
    )
    (comp (ref "R1")
      (value "10K 1%")
      (footprint "eagle-import:0402")
      (fields
        (field (name "HQ_PART") "RE0207399")
        (field (name "LCSC_PART") "C25744")
        (field (name "MANUFACTURER") "ROHM")
      )
      (libsource (lib "eagle-import") (part "10K-1%0402"))
    )
    (comp (ref "R2")
      (value "1M 1%")
      (footprint "eagle-import:1206")
      (fields
        (field (name "PACKAGE") "1206")
        (field (name "HQ_PART") "RE0188103")
        (field (name "LCSC_PART") "C17927")
        (field (name "MANUFACTURER") "Uniohm")
      )
      (libsource (lib "eagle-import") (part "1M-1%1206"))
    )
    (comp (ref "R3")
      (value "20K 1%")
      (footprint "eagle-import:0201")
      (fields (field (name "LCSC_PART") "C473466"))
      (libsource (lib "eagle-import") (part "20K-1%0201"))
    )
    (comp (ref "R4")
      (value "10K 1%")
      (footprint "eagle-import:0402")
      (fields
        (field (name "HQ_PART") "RE0207399")
        (field (name "LCSC_PART") "C25744")
        (field (name "MANUFACTURER") "ROHM")
      )
      (libsource (lib "eagle-import") (part "10K-1%0402"))
    )
    (comp (ref "R12")
      (value "1K 1%")
      (footprint "eagle-import:0402")
      (fields
        (field (name "HQ_PART") "RE0208724")
        (field (name "LCSC_PART") "C11702")
        (field (name "MANUFACTURER") "FH")
      )
      (libsource (lib "eagle-import") (part "1K-1%0402"))
    )
    (comp (ref "R13")
      (value "10K 1%")
      (footprint "eagle-import:0402")
      (fields
        (field (name "HQ_PART") "RE0207399")
        (field (name "LCSC_PART") "C25744")
        (field (name "MANUFACTURER") "ROHM")
      )
      (libsource (lib "eagle-import") (part "10K-1%0402"))
    )
    (comp (ref "R14")
      (value "1K 1%")
      (footprint "eagle-import:0402")
      (fields
        (field (name "HQ_PART") "RE0208724")
        (field (name "LCSC_PART") "C11702")
        (field (name "MANUFACTURER") "FH")
      )
      (libsource (lib "eagle-import") (part "1K-1%0402"))
    )
    (comp (ref "R15")
      (value "1K 1%")
      (footprint "eagle-import:0402")
      (fields
        (field (name "HQ_PART") "RE0208724")
        (field (name "LCSC_PART") "C11702")
        (field (name "MANUFACTURER") "FH")
      )
      (libsource (lib "eagle-import") (part "1K-1%0402"))
    )
    (comp (ref "R16")
      (value "10K 1%")
      (footprint "eagle-import:0402")
      (fields
        (field (name "HQ_PART") "RE0207399")
        (field (name "LCSC_PART") "C25744")
        (field (name "MANUFACTURER") "ROHM")
      )
      (libsource (lib "eagle-import") (part "10K-1%0402"))
    )
    (comp (ref "R17")
      (value "1K 1%")
      (footprint "eagle-import:0402")
      (fields
        (field (name "HQ_PART") "RE0208724")
        (field (name "LCSC_PART") "C11702")
        (field (name "MANUFACTURER") "FH")
      )
      (libsource (lib "eagle-import") (part "1K-1%0402"))
    )
    (comp (ref "R84")
      (value "20K 1%")
      (footprint "eagle-import:0201")
      (fields (field (name "LCSC_PART") "C473466"))
      (libsource (lib "eagle-import") (part "20K-1%0201"))
    )
    (comp (ref "USBA_1-2")
      (value "61400826021")
      (footprint "eagle-import:61400826021")
      (libsource (lib "eagle-import") (part "61400826021"))
    )
    (comp (ref "VUSBA1")
      (value "TPB1,27")
      (footprint "eagle-import:B1,27")
      (libsource (lib "eagle-import") (part "TPB1,27"))
    )
    (comp (ref "VUSBA2")
      (value "TPB1,27")
      (footprint "eagle-import:B1,27")
      (libsource (lib "eagle-import") (part "TPB1,27"))
    )
    (comp (ref "C30")
      (value "22nF 50V")
      (footprint "eagle-import:0402")
      (fields
        (field (name "HQ_PART") "CA0171190")
        (field (name "LCSC_PART") "C1532")
        (field (name "MANUFACTURER") "Samsung")
      )
      (libsource (lib "eagle-import") (part "22NF-50V0402"))
    )
    (comp (ref "C31")
      (value "C1206C102KGRACTM")
      (footprint "eagle-import:C1206")
      (libsource (lib "eagle-import") (part "C-1206"))
    )
    (comp (ref "C32")
      (value "100nF 25V")
      (footprint "eagle-import:0402")
      (fields
        (field (name "HQ_PART") "CA0176807")
        (field (name "LCSC_PART") "C56392")
        (field (name "MANUFACTURER") "Walsin")
      )
      (libsource (lib "eagle-import") (part "100NF-25V-0402"))
    )
    (comp (ref "C33")
      (value "6.8nF 50V")
      (footprint "eagle-import:0201")
      (fields
        (field (name "HQ_PART") "CA0363038")
        (field (name "LCSC_PART") "C285015")
        (field (name "MANUFACTURER") "FH")
      )
      (libsource (lib "eagle-import") (part "6.8NF-50V0201"))
    )
    (comp (ref "C34")
      (value "6.8nF 50V")
      (footprint "eagle-import:0201")
      (fields
        (field (name "HQ_PART") "CA0363038")
        (field (name "LCSC_PART") "C285015")
        (field (name "MANUFACTURER") "FH")
      )
      (libsource (lib "eagle-import") (part "6.8NF-50V0201"))
    )
    (comp (ref "C35")
      (value "100nF 25V")
      (footprint "eagle-import:0201")
      (fields
        (field (name "HQ_PART") "CA0183221")
        (field (name "LCSC_PART") "C76939")
        (field (name "MANUFACTURER") "Samsung")
      )
      (libsource (lib "eagle-import") (part "100NF-25V-0201"))
    )
    (comp (ref "C36")
      (value "4.7uF 25V")
      (footprint "eagle-import:0402")
      (fields
        (field (name "HQ_PART") "ZHLM0023346")
        (field (name "LCSC_PART") "C22367824")
        (field (name "MANUFACTURER") "Murata")
      )
      (libsource (lib "eagle-import") (part "4.7UF-25V0402"))
    )
    (comp (ref "C37")
      (value "18pF 50V")
      (footprint "eagle-import:0201")
      (fields
        (field (name "HQ_PART") "CA0486739")
        (field (name "LCSC_PART") "C62164")
        (field (name "MANUFACTURER") "Yageo")
      )
      (libsource (lib "eagle-import") (part "18PF-50V-0201"))
    )
    (comp (ref "C38")
      (value "18pF 50V")
      (footprint "eagle-import:0201")
      (fields
        (field (name "HQ_PART") "CA0486739")
        (field (name "LCSC_PART") "C62164")
        (field (name "MANUFACTURER") "Yageo")
      )
      (libsource (lib "eagle-import") (part "18PF-50V-0201"))
    )
    (comp (ref "C221")
      (value "100nF 25V")
      (footprint "eagle-import:0201")
      (fields
        (field (name "HQ_PART") "CA0183221")
        (field (name "LCSC_PART") "C76939")
        (field (name "MANUFACTURER") "Samsung")
      )
      (libsource (lib "eagle-import") (part "100NF-25V-0201"))
    )
    (comp (ref "C222")
      (value "100nF 25V")
      (footprint "eagle-import:0201")
      (fields
        (field (name "HQ_PART") "CA0183221")
        (field (name "LCSC_PART") "C76939")
        (field (name "MANUFACTURER") "Samsung")
      )
      (libsource (lib "eagle-import") (part "100NF-25V-0201"))
    )
    (comp (ref "C223")
      (value "100nF 25V")
      (footprint "eagle-import:0201")
      (fields
        (field (name "HQ_PART") "CA0183221")
        (field (name "LCSC_PART") "C76939")
        (field (name "MANUFACTURER") "Samsung")
      )
      (libsource (lib "eagle-import") (part "100NF-25V-0201"))
    )
    (comp (ref "C224")
      (value "100nF 25V")
      (footprint "eagle-import:0201")
      (fields
        (field (name "HQ_PART") "CA0183221")
        (field (name "LCSC_PART") "C76939")
        (field (name "MANUFACTURER") "Samsung")
      )
      (libsource (lib "eagle-import") (part "100NF-25V-0201"))
    )
    (comp (ref "C225")
      (value "100nF 25V")
      (footprint "eagle-import:0201")
      (fields
        (field (name "HQ_PART") "CA0183221")
        (field (name "LCSC_PART") "C76939")
        (field (name "MANUFACTURER") "Samsung")
      )
      (libsource (lib "eagle-import") (part "100NF-25V-0201"))
    )
    (comp (ref "C226")
      (value "100nF 25V")
      (footprint "eagle-import:0201")
      (fields
        (field (name "HQ_PART") "CA0183221")
        (field (name "LCSC_PART") "C76939")
        (field (name "MANUFACTURER") "Samsung")
      )
      (libsource (lib "eagle-import") (part "100NF-25V-0201"))
    )
    (comp (ref "C227")
      (value "100nF 25V")
      (footprint "eagle-import:0201")
      (fields
        (field (name "HQ_PART") "CA0183221")
        (field (name "LCSC_PART") "C76939")
        (field (name "MANUFACTURER") "Samsung")
      )
      (libsource (lib "eagle-import") (part "100NF-25V-0201"))
    )
    (comp (ref "C228")
      (value "100nF 25V")
      (footprint "eagle-import:0201")
      (fields
        (field (name "HQ_PART") "CA0183221")
        (field (name "LCSC_PART") "C76939")
        (field (name "MANUFACTURER") "Samsung")
      )
      (libsource (lib "eagle-import") (part "100NF-25V-0201"))
    )
    (comp (ref "C229")
      (value "100nF 25V")
      (footprint "eagle-import:0201")
      (fields
        (field (name "HQ_PART") "CA0183221")
        (field (name "LCSC_PART") "C76939")
        (field (name "MANUFACTURER") "Samsung")
      )
      (libsource (lib "eagle-import") (part "100NF-25V-0201"))
    )
    (comp (ref "ETH1")
      (value "J1B1211CCD")
      (footprint "eagle-import:J1B1211CCD")
      (fields
        (field (name "HQ_PART") "UN0002907")
        (field (name "LCSC_PART") "C910371")
        (field (name "MANUFACTURER") "WIZnet")
      )
      (libsource (lib "eagle-import") (part "J1B1211CCD"))
    )
    (comp (ref "IC31")
      (value "W5500")
      (footprint "eagle-import:LQFP48")
      (fields
        (field (name "HQ_PART") "IC0084426")
        (field (name "LCSC_PART") "C32843")
        (field (name "MANUFACTURER") "WIZNET")
      )
      (libsource (lib "eagle-import") (part "W5500"))
    )
    (comp (ref "L10")
      (value "BLM18EG221TN1D")
      (footprint "eagle-import:0603")
      (libsource (lib "eagle-import") (part "R0603"))
    )
    (comp (ref "R33")
      (value "470R 1%")
      (footprint "eagle-import:0402")
      (fields
        (field (name "HQ_PART") "RE0205922")
        (field (name "LCSC_PART") "C25117")
        (field (name "MANUFACTURER") "Panasonic")
      )
      (libsource (lib "eagle-import") (part "470R-1%0402"))
    )
    (comp (ref "R34")
      (value "470R 1%")
      (footprint "eagle-import:0402")
      (fields
        (field (name "HQ_PART") "RE0205922")
        (field (name "LCSC_PART") "C25117")
        (field (name "MANUFACTURER") "Panasonic")
      )
      (libsource (lib "eagle-import") (part "470R-1%0402"))
    )
    (comp (ref "R35")
      (value "470R 1%")
      (footprint "eagle-import:0402")
      (fields
        (field (name "HQ_PART") "RE0205922")
        (field (name "LCSC_PART") "C25117")
        (field (name "MANUFACTURER") "Panasonic")
      )
      (libsource (lib "eagle-import") (part "470R-1%0402"))
    )
    (comp (ref "R36")
      (value "1M 1%")
      (footprint "eagle-import:1206")
      (fields
        (field (name "HQ_PART") "RE0188103")
        (field (name "LCSC_PART") "C17927")
        (field (name "MANUFACTURER") "Uniohm")
      )
      (libsource (lib "eagle-import") (part "1M-1%1206"))
    )
    (comp (ref "R37")
      (value "3.3R 1%")
      (footprint "eagle-import:0201")
      (fields
        (field (name "HQ_PART") "RE0422979")
        (field (name "LCSC_PART") "C158547")
        (field (name "MANUFACTURER") "Uniohm")
      )
      (libsource (lib "eagle-import") (part "3.3R-1%0201"))
    )
    (comp (ref "R38")
      (value "3.3R 1%")
      (footprint "eagle-import:0201")
      (fields
        (field (name "HQ_PART") "RE0422979")
        (field (name "LCSC_PART") "C158547")
        (field (name "MANUFACTURER") "Uniohm")
      )
      (libsource (lib "eagle-import") (part "3.3R-1%0201"))
    )
    (comp (ref "R39")
      (value "3.3R 1%")
      (footprint "eagle-import:0201")
      (fields
        (field (name "HQ_PART") "RE0422979")
        (field (name "LCSC_PART") "C158547")
        (field (name "MANUFACTURER") "Uniohm")
      )
      (libsource (lib "eagle-import") (part "3.3R-1%0201"))
    )
    (comp (ref "R40")
      (value "3.3R 1%")
      (footprint "eagle-import:0201")
      (fields
        (field (name "HQ_PART") "RE0422979")
        (field (name "LCSC_PART") "C158547")
        (field (name "MANUFACTURER") "Uniohm")
      )
      (libsource (lib "eagle-import") (part "3.3R-1%0201"))
    )
    (comp (ref "R41")
      (value "49.9R 1%")
      (footprint "eagle-import:0201")
      (fields
        (field (name "HQ_PART") "RE0721921")
        (field (name "LCSC_PART") "C155744")
        (field (name "MANUFACTURER") "FH")
      )
      (libsource (lib "eagle-import") (part "49.9R-1%0201"))
    )
    (comp (ref "R42")
      (value "49.9R 1%")
      (footprint "eagle-import:0201")
      (fields
        (field (name "HQ_PART") "RE0721921")
        (field (name "LCSC_PART") "C155744")
        (field (name "MANUFACTURER") "FH")
      )
      (libsource (lib "eagle-import") (part "49.9R-1%0201"))
    )
    (comp (ref "R43")
      (value "49.9R 1%")
      (footprint "eagle-import:0201")
      (fields
        (field (name "HQ_PART") "RE0721921")
        (field (name "LCSC_PART") "C155744")
        (field (name "MANUFACTURER") "FH")
      )
      (libsource (lib "eagle-import") (part "49.9R-1%0201"))
    )
    (comp (ref "R44")
      (value "49.9R 1%")
      (footprint "eagle-import:0201")
      (fields
        (field (name "HQ_PART") "RE0721921")
        (field (name "LCSC_PART") "C155744")
        (field (name "MANUFACTURER") "FH")
      )
      (libsource (lib "eagle-import") (part "49.9R-1%0201"))
    )
    (comp (ref "R45")
      (value "12.4K 1%")
      (footprint "eagle-import:R0201")
      (libsource (lib "eagle-import") (part "R0201"))
    )
    (comp (ref "R205")
      (value "1M 1%")
      (footprint "eagle-import:0201")
      (fields
        (field (name "HQ_PART") "RE0422946")
        (field (name "LCSC_PART") "C295786")
        (field (name "MANUFACTURER") "Yageo")
      )
      (libsource (lib "eagle-import") (part "1M-1%0201"))
    )
    (comp (ref "R206")
      (value "4.7K 1%")
      (footprint "eagle-import:0201")
      (fields
        (field (name "HQ_PART") "RE0208670")
        (field (name "LCSC_PART") "C270346")
        (field (name "MANUFACTURER") "RALEC")
      )
      (libsource (lib "eagle-import") (part "4.7K-1%0201"))
    )
    (comp (ref "R208")
      (value "4.7K 1%")
      (footprint "eagle-import:0201")
      (fields
        (field (name "HQ_PART") "RE0208670")
        (field (name "LCSC_PART") "C270346")
        (field (name "MANUFACTURER") "RALEC")
      )
      (libsource (lib "eagle-import") (part "4.7K-1%0201"))
    )
    (comp (ref "R225")
      (value "4.7K 1%")
      (footprint "eagle-import:0201")
      (fields
        (field (name "HQ_PART") "RE0208670")
        (field (name "LCSC_PART") "C270346")
        (field (name "MANUFACTURER") "RALEC")
      )
      (libsource (lib "eagle-import") (part "4.7K-1%0201"))
    )
    (comp (ref "R226")
      (value "4.7K 1%")
      (footprint "eagle-import:0201")
      (fields
        (field (name "HQ_PART") "RE0208670")
        (field (name "LCSC_PART") "C270346")
        (field (name "MANUFACTURER") "RALEC")
      )
      (libsource (lib "eagle-import") (part "4.7K-1%0201"))
    )
    (comp (ref "R227")
      (value "4.7K 1%")
      (footprint "eagle-import:0201")
      (fields
        (field (name "HQ_PART") "RE0208670")
        (field (name "LCSC_PART") "C270346")
        (field (name "MANUFACTURER") "RALEC")
      )
      (libsource (lib "eagle-import") (part "4.7K-1%0201"))
    )
    (comp (ref "X2")
      (value "25MHz")
      (footprint "eagle-import:WE-XTAL_CFPX-180")
      (fields
        (field (name "HQ_PART") "CR0250343")
        (field (name "LCSC_PART") "C13740")
        (field (name "MANUFACTURER") "Epson")
      )
      (libsource (lib "eagle-import") (part "CRYSTAL-3225X322525MOB4SI"))
    )
  )
  (nets
    (net (code "1") (name "+1V1") (class "Default")
      (node (ref "C192") (pin "1") (pinfunction "1_1") (pintype "passive"))
      (node (ref "C193") (pin "1") (pinfunction "1_1") (pintype "passive"))
      (node (ref "C194") (pin "1") (pinfunction "1_1") (pintype "passive"))
      (node (ref "C26") (pin "1") (pinfunction "1_1") (pintype "passive"))
      (node (ref "C27") (pin "1") (pinfunction "1_1") (pintype "passive"))
      (node (ref "IC26") (pin "10") (pinfunction "DVDD1_10") (pintype "power_in"))
      (node (ref "IC26") (pin "32") (pinfunction "DVDD2_32") (pintype "power_in"))
      (node (ref "IC26") (pin "51") (pinfunction "DVDD3_51") (pintype "power_in"))
      (node (ref "IC26") (pin "65") (pinfunction "VREG_FB_65") (pintype "input"))
      (node (ref "IC26") (pin "68") (pinfunction "USB_OTP_VDD_68") (pintype "power_in"))
      (node (ref "IC26") (pin "69") (pinfunction "QSPI_IOVDD_69") (pintype "power_in"))
      (node (ref "L1") (pin "2") (pinfunction "2_2") (pintype "passive"))
    )
    (net (code "2") (name "+3V3") (class "Default")
      (node (ref "C17") (pin "1") (pinfunction "1_1") (pintype "passive"))
      (node (ref "C176") (pin "1") (pinfunction "1_1") (pintype "passive"))
      (node (ref "C18") (pin "1") (pinfunction "1_1") (pintype "passive"))
      (node (ref "C182") (pin "1") (pinfunction "1_1") (pintype "passive"))
      (node (ref "C183") (pin "1") (pinfunction "1_1") (pintype "passive"))
      (node (ref "C184") (pin "1") (pinfunction "1_1") (pintype "passive"))
      (node (ref "C185") (pin "1") (pinfunction "1_1") (pintype "passive"))
      (node (ref "C186") (pin "1") (pinfunction "1_1") (pintype "passive"))
      (node (ref "C187") (pin "1") (pinfunction "1_1") (pintype "passive"))
      (node (ref "C188") (pin "1") (pinfunction "1_1") (pintype "passive"))
      (node (ref "C189") (pin "1") (pinfunction "1_1") (pintype "passive"))
      (node (ref "C19") (pin "1") (pinfunction "1_1") (pintype "passive"))
      (node (ref "C190") (pin "1") (pinfunction "1_1") (pintype "passive"))
      (node (ref "C195") (pin "1") (pinfunction "1_1") (pintype "passive"))
      (node (ref "C20") (pin "1") (pinfunction "1_1") (pintype "passive"))
      (node (ref "C212") (pin "1") (pinfunction "1_1") (pintype "passive"))
      (node (ref "C213") (pin "1") (pinfunction "1_1") (pintype "passive"))
      (node (ref "C22") (pin "1") (pinfunction "1_1") (pintype "passive"))
      (node (ref "C221") (pin "1") (pinfunction "1_1") (pintype "passive"))
      (node (ref "C222") (pin "1") (pinfunction "1_1") (pintype "passive"))
      (node (ref "C223") (pin "1") (pinfunction "1_1") (pintype "passive"))
      (node (ref "C23") (pin "1") (pinfunction "1_1") (pintype "passive"))
      (node (ref "C236") (pin "1") (pinfunction "1_1") (pintype "passive"))
      (node (ref "C238") (pin "1") (pinfunction "1_1") (pintype "passive"))
      (node (ref "C239") (pin "1") (pinfunction "1_1") (pintype "passive"))
      (node (ref "C24") (pin "1") (pinfunction "1_1") (pintype "passive"))
      (node (ref "C249") (pin "1") (pinfunction "1_1") (pintype "passive"))
      (node (ref "C25") (pin "1") (pinfunction "1_1") (pintype "passive"))
      (node (ref "C251") (pin "1") (pinfunction "1_1") (pintype "passive"))
      (node (ref "C55") (pin "1") (pinfunction "1_1") (pintype "passive"))
      (node (ref "D1") (pin "A") (pinfunction "A_A") (pintype "passive"))
      (node (ref "D12") (pin "5") (pinfunction "5_5") (pintype "power_in"))
      (node (ref "D13") (pin "5") (pinfunction "5_5") (pintype "power_in"))
      (node (ref "D3") (pin "A") (pinfunction "A_A") (pintype "passive"))
      (node (ref "D5") (pin "A") (pinfunction "A_A") (pintype "passive"))
      (node (ref "D7") (pin "A") (pinfunction "A_A") (pintype "passive"))
      (node (ref "DISP") (pin "1") (pinfunction "1_1") (pintype "bidirectional"))
      (node (ref "DISP") (pin "2") (pinfunction "2_2") (pintype "bidirectional"))
      (node (ref "ETH1") (pin "10") (pinfunction "GREEN+_10") (pintype "passive"))
      (node (ref "ETH1") (pin "12") (pinfunction "YELLOW+_12") (pintype "passive"))
      (node (ref "IC13") (pin "4") (pinfunction "VCC_4") (pintype "bidirectional"))
      (node (ref "IC26") (pin "15") (pinfunction "IOVDD2_15") (pintype "power_in"))
      (node (ref "IC26") (pin "24") (pinfunction "IOVDD3_24") (pintype "power_in"))
      (node (ref "IC26") (pin "29") (pinfunction "IOVDD4_29") (pintype "power_in"))
      (node (ref "IC26") (pin "41") (pinfunction "IOVDD5_41") (pintype "power_in"))
      (node (ref "IC26") (pin "5") (pinfunction "IOVDD1_5") (pintype "power_in"))
      (node (ref "IC26") (pin "50") (pinfunction "IOVDD6_50") (pintype "power_in"))
      (node (ref "IC26") (pin "60") (pinfunction "IOVDD7_60") (pintype "power_in"))
      (node (ref "IC26") (pin "64") (pinfunction "VREG_IN_64") (pintype "power_in"))
      (node (ref "IC26") (pin "76") (pinfunction "IOVDD8_76") (pintype "power_in"))
      (node (ref "IC27") (pin "8") (pinfunction "VCC_8") (pintype "power_in"))
      (node (ref "IC28") (pin "2") (pinfunction "V+_2") (pintype "power_in"))
      (node (ref "IC29") (pin "8") (pinfunction "VCC_8") (pintype "power_in"))
      (node (ref "IC31") (pin "28") (pinfunction "VDD_28") (pintype "power_in"))
      (node (ref "IC31") (pin "43") (pinfunction "PMODE2_43") (pintype "input"))
      (node (ref "IC31") (pin "44") (pinfunction "PMODE1_44") (pintype "input"))
      (node (ref "IC31") (pin "45") (pinfunction "PMODE0_45") (pintype "input"))
      (node (ref "IC38") (pin "21") (pinfunction "VCC_21") (pintype "power_in"))
      (node (ref "IC4") (pin "5") (pinfunction "V+_5") (pintype "bidirectional"))
      (node (ref "IC42") (pin "5") (pinfunction "VDD_5") (pintype "bidirectional"))
      (node (ref "IC5") (pin "5") (pinfunction "V+_5") (pintype "bidirectional"))
      (node (ref "IC6") (pin "5") (pinfunction "V+_5") (pintype "bidirectional"))
      (node (ref "IC7") (pin "5") (pinfunction "V+_5") (pintype "bidirectional"))
      (node (ref "L10") (pin "1") (pinfunction "1_1") (pintype "passive"))
      (node (ref "L11") (pin "2") (pinfunction "2_2") (pintype "passive"))
      (node (ref "R1") (pin "1") (pinfunction "1_1") (pintype "passive"))
      (node (ref "R10") (pin "1") (pinfunction "1_1") (pintype "passive"))
      (node (ref "R13") (pin "2") (pinfunction "2_2") (pintype "passive"))
      (node (ref "R16") (pin "2") (pinfunction "2_2") (pintype "passive"))
      (node (ref "R19") (pin "2") (pinfunction "2_2") (pintype "passive"))
      (node (ref "R206") (pin "2") (pinfunction "2_2") (pintype "passive"))
      (node (ref "R207") (pin "A2") (pinfunction "8_A2") (pintype "passive"))
      (node (ref "R207") (pin "B2") (pinfunction "7_B2") (pintype "passive"))
      (node (ref "R207") (pin "C2") (pinfunction "6_C2") (pintype "passive"))
      (node (ref "R207") (pin "D2") (pinfunction "5_D2") (pintype "passive"))
      (node (ref "R209") (pin "2") (pinfunction "2_2") (pintype "passive"))
      (node (ref "R212") (pin "2") (pinfunction "2_2") (pintype "passive"))
      (node (ref "R213") (pin "2") (pinfunction "2_2") (pintype "passive"))
      (node (ref "R215") (pin "A2") (pinfunction "8_A2") (pintype "passive"))
      (node (ref "R215") (pin "B2") (pinfunction "7_B2") (pintype "passive"))
      (node (ref "R215") (pin "C2") (pinfunction "6_C2") (pintype "passive"))
      (node (ref "R215") (pin "D2") (pinfunction "5_D2") (pintype "passive"))
      (node (ref "R216") (pin "A2") (pinfunction "8_A2") (pintype "passive"))
      (node (ref "R216") (pin "B2") (pinfunction "7_B2") (pintype "passive"))
      (node (ref "R216") (pin "C2") (pinfunction "6_C2") (pintype "passive"))
      (node (ref "R216") (pin "D2") (pinfunction "5_D2") (pintype "passive"))
      (node (ref "R217") (pin "A2") (pinfunction "8_A2") (pintype "passive"))
      (node (ref "R217") (pin "B2") (pinfunction "7_B2") (pintype "passive"))
      (node (ref "R217") (pin "C2") (pinfunction "6_C2") (pintype "passive"))
      (node (ref "R217") (pin "D2") (pinfunction "5_D2") (pintype "passive"))
      (node (ref "R22") (pin "2") (pinfunction "2_2") (pintype "passive"))
      (node (ref "R226") (pin "2") (pinfunction "2_2") (pintype "passive"))
      (node (ref "R227") (pin "2") (pinfunction "2_2") (pintype "passive"))
      (node (ref "R24") (pin "1") (pinfunction "1_1") (pintype "passive"))
      (node (ref "R252") (pin "2") (pinfunction "2_2") (pintype "passive"))
      (node (ref "R27") (pin "1") (pinfunction "1_1") (pintype "passive"))
      (node (ref "R29") (pin "1") (pinfunction "1_1") (pintype "passive"))
      (node (ref "R4") (pin "1") (pinfunction "1_1") (pintype "passive"))
      (node (ref "R7") (pin "1") (pinfunction "1_1") (pintype "passive"))
      (node (ref "RFB3") (pin "1") (pinfunction "1_1") (pintype "passive"))
      (node (ref "VO3") (pin "TP") (pinfunction "P$1_TP") (pintype "bidirectional"))
    )
    (net (code "3") (name "+3V3_A") (class "Default")
      (node (ref "C224") (pin "1") (pinfunction "1_1") (pintype "passive"))
      (node (ref "C225") (pin "1") (pinfunction "1_1") (pintype "passive"))
      (node (ref "C226") (pin "1") (pinfunction "1_1") (pintype "passive"))
      (node (ref "C227") (pin "1") (pinfunction "1_1") (pintype "passive"))
      (node (ref "C228") (pin "1") (pinfunction "1_1") (pintype "passive"))
      (node (ref "C229") (pin "1") (pinfunction "1_1") (pintype "passive"))
      (node (ref "IC31") (pin "11") (pinfunction "AVDD_11") (pintype "power_in"))
      (node (ref "IC31") (pin "15") (pinfunction "AVDD_15") (pintype "power_in"))
      (node (ref "IC31") (pin "17") (pinfunction "AVDD_17") (pintype "power_in"))
      (node (ref "IC31") (pin "21") (pinfunction "AVDD_21") (pintype "power_in"))
      (node (ref "IC31") (pin "4") (pinfunction "AVDD_4") (pintype "power_in"))
      (node (ref "IC31") (pin "8") (pinfunction "AVDD_8") (pintype "power_in"))
      (node (ref "L10") (pin "2") (pinfunction "2_2") (pintype "passive"))
      (node (ref "R208") (pin "2") (pinfunction "2_2") (pintype "passive"))
      (node (ref "R35") (pin "2") (pinfunction "2_2") (pintype "passive"))
      (node (ref "R43") (pin "2") (pinfunction "2_2") (pintype "passive"))
      (node (ref "R44") (pin "2") (pinfunction "2_2") (pintype "passive"))
    )
    (net (code "4") (name "+5V") (class "Default")
      (node (ref "DISP") (pin "3") (pinfunction "3_3") (pintype "bidirectional"))
      (node (ref "DISP") (pin "4") (pinfunction "4_4") (pintype "bidirectional"))
    )
    (net (code "5") (name "+5VA") (class "Default")
      (node (ref "C2") (pin "1") (pinfunction "1_1") (pintype "passive"))
      (node (ref "C264") (pin "1") (pinfunction "1_1") (pintype "passive"))
      (node (ref "C82") (pin "1") (pinfunction "1_1") (pintype "passive"))
      (node (ref "IC1") (pin "1") (pinfunction "IN_1") (pintype "bidirectional"))
      (node (ref "IC8") (pin "1") (pinfunction "IN_1") (pintype "bidirectional"))
      (node (ref "VO5A") (pin "TP") (pinfunction "P$1_TP") (pintype "bidirectional"))
    )
    (net (code "6") (name "+5VB") (class "Default")
      (node (ref "C12") (pin "1") (pinfunction "1_1") (pintype "passive"))
      (node (ref "C278") (pin "1") (pinfunction "1_1") (pintype "passive"))
      (node (ref "C7") (pin "1") (pinfunction "1_1") (pintype "passive"))
      (node (ref "IC2") (pin "1") (pinfunction "IN_1") (pintype "bidirectional"))
      (node (ref "IC3") (pin "1") (pinfunction "IN_1") (pintype "bidirectional"))
      (node (ref "VO5B") (pin "TP") (pinfunction "P$1_TP") (pintype "bidirectional"))
    )
    (net (code "7") (name "+24VB") (class "Default")
      (node (ref "C254") (pin "1") (pinfunction "+_1") (pintype "passive"))
      (node (ref "C255") (pin "1") (pinfunction "+_1") (pintype "passive"))
      (node (ref "D10") (pin "C") (pinfunction "C_C") (pintype "passive"))
      (node (ref "F2") (pin "2_1") (pinfunction "2_2_1") (pintype "passive"))
      (node (ref "F2") (pin "2_2") (pinfunction "2_2_2") (pintype "passive"))
    )
    (net (code "8") (name "+24V_A") (class "Default")
      (node (ref "C214") (pin "1") (pinfunction "1_1") (pintype "passive"))
      (node (ref "C256") (pin "1") (pinfunction "+_1") (pintype "passive"))
      (node (ref "C257") (pin "1") (pinfunction "+_1") (pintype "passive"))
      (node (ref "C47") (pin "1") (pinfunction "1_1") (pintype "passive"))
      (node (ref "C48") (pin "1") (pinfunction "1_1") (pintype "passive"))
      (node (ref "C49") (pin "1") (pinfunction "1_1") (pintype "passive"))
      (node (ref "C50") (pin "1") (pinfunction "+_1") (pintype "passive"))
      (node (ref "D11") (pin "C") (pinfunction "C_C") (pintype "passive"))
      (node (ref "F3") (pin "2_1") (pinfunction "2_2_1") (pintype "passive"))
      (node (ref "F3") (pin "2_2") (pinfunction "2_2_2") (pintype "passive"))
      (node (ref "IC12") (pin "3") (pinfunction "VIN_3") (pintype "power_in"))
      (node (ref "T10") (pin "5") (pinfunction "D_5") (pintype "passive"))
      (node (ref "T10") (pin "6") (pinfunction "D_6") (pintype "passive"))
      (node (ref "T10") (pin "7") (pinfunction "D_7") (pintype "passive"))
      (node (ref "T10") (pin "8") (pinfunction "D_8") (pintype "passive"))
      (node (ref "T10") (pin "9") (pinfunction "D_9") (pintype "passive"))
    )
    (net (code "9") (name "+24V_C") (class "Default")
      (node (ref "C233") (pin "1") (pinfunction "1_1") (pintype "passive"))
      (node (ref "C237") (pin "1") (pinfunction "1_1") (pintype "passive"))
      (node (ref "C252") (pin "1") (pinfunction "+_1") (pintype "passive"))
      (node (ref "C253") (pin "1") (pinfunction "+_1") (pintype "passive"))
      (node (ref "D9") (pin "C") (pinfunction "C_C") (pintype "passive"))
      (node (ref "F1") (pin "2_1") (pinfunction "2_2_1") (pintype "passive"))
      (node (ref "F1") (pin "2_2") (pinfunction "2_2_2") (pintype "passive"))
      (node (ref "IC40") (pin "2") (pinfunction "IN_2") (pintype "bidirectional"))
      (node (ref "R241") (pin "1") (pinfunction "1_1") (pintype "passive"))
    )
    (net (code "10") (name "ADC_3VA") (class "Default")
      (node (ref "R208") (pin "1") (pinfunction "1_1") (pintype "passive"))
      (node (ref "R225") (pin "2") (pinfunction "2_2") (pintype "passive"))
    )
    (net (code "11") (name "ADC_VUSB") (class "Default")
      (node (ref "C29") (pin "1") (pinfunction "1_1") (pintype "passive"))
      (node (ref "R31") (pin "2") (pinfunction "2_2") (pintype "passive"))
      (node (ref "R32") (pin "1") (pinfunction "1_1") (pintype "passive"))
    )
    (net (code "12") (name "AGND") (class "Default")
      (node (ref "C1") (pin "1") (pinfunction "1_1") (pintype "passive"))
      (node (ref "C11") (pin "1") (pinfunction "1_1") (pintype "passive"))
      (node (ref "C28") (pin "1") (pinfunction "1_1") (pintype "passive"))
      (node (ref "C40") (pin "2") (pinfunction "2_2") (pintype "passive"))
      (node (ref "H1") (pin "B3,3") (pinfunction "MOUNT_B3,3") (pintype "passive"))
      (node (ref "H2") (pin "B3,3") (pinfunction "MOUNT_B3,3") (pintype "passive"))
      (node (ref "H3") (pin "B3,3") (pinfunction "MOUNT_B3,3") (pintype "passive"))
      (node (ref "H4") (pin "B3,3") (pinfunction "MOUNT_B3,3") (pintype "passive"))
      (node (ref "PORT1") (pin "S1") (pinfunction "SHIELD1_S1") (pintype "passive"))
      (node (ref "PORT1") (pin "S2") (pinfunction "SHIELD1_S2") (pintype "passive"))
      (node (ref "PORT1") (pin "S3") (pinfunction "SHIELD1_S3") (pintype "passive"))
      (node (ref "PORT1") (pin "S4") (pinfunction "SHIELD1_S4") (pintype "passive"))
      (node (ref "R2") (pin "2") (pinfunction "2_2") (pintype "passive"))
      (node (ref "R255") (pin "1") (pinfunction "1_1") (pintype "passive"))
      (node (ref "R50") (pin "2") (pinfunction "2_2") (pintype "passive"))
      (node (ref "R8") (pin "2") (pinfunction "2_2") (pintype "passive"))
      (node (ref "USB9") (pin "SHLD1") (pinfunction "SHILED_SHLD1") (pintype "power_in"))
      (node (ref "USB9") (pin "SHLD2") (pinfunction "SHILED_SHLD2") (pintype "power_in"))
      (node (ref "USB9") (pin "SHLD3") (pinfunction "SHILED_SHLD3") (pintype "power_in"))
      (node (ref "USB9") (pin "SHLD4") (pinfunction "SHILED_SHLD4") (pintype "power_in"))
      (node (ref "USBA_1-2") (pin "S1") (pinfunction "SHIELD_S1") (pintype "passive"))
      (node (ref "USBA_1-2") (pin "S2") (pinfunction "SHIELD_S2") (pintype "passive"))
      (node (ref "USBA_1-2") (pin "S3") (pinfunction "SHIELD_S3") (pintype "passive"))
      (node (ref "USBA_1-2") (pin "S4") (pinfunction "SHIELD_S4") (pintype "passive"))
      (node (ref "USBA_3-4") (pin "S1") (pinfunction "SHIELD_S1") (pintype "passive"))
      (node (ref "USBA_3-4") (pin "S2") (pinfunction "SHIELD_S2") (pintype "passive"))
      (node (ref "USBA_3-4") (pin "S3") (pinfunction "SHIELD_S3") (pintype "passive"))
      (node (ref "USBA_3-4") (pin "S4") (pinfunction "SHIELD_S4") (pintype "passive"))
    )
    (net (code "13") (name "AVDD") (class "Default")
      (node (ref "AVDD") (pin "TP") (pinfunction "P$1_TP") (pintype "bidirectional"))
      (node (ref "C181") (pin "1") (pinfunction "1_1") (pintype "passive"))
      (node (ref "IC28") (pin "1") (pinfunction "OUT_1") (pintype "output"))
      (node (ref "IC28") (pin "4") (pinfunction "-IN_4") (pintype "input"))
      (node (ref "R28") (pin "2") (pinfunction "2_2") (pintype "passive"))
    )
    (net (code "14") (name "CC1_PORT1") (class "Default")
      (node (ref "IC9") (pin "2") (pinfunction "CC1_2") (pintype "bidirectional"))
      (node (ref "PORT1") (pin "A5") (pinfunction "CC1_A5") (pintype "passive"))
    )
    (net (code "15") (name "CC2_PORT1") (class "Default")
      (node (ref "IC9") (pin "3") (pinfunction "CC2_3") (pintype "bidirectional"))
      (node (ref "PORT1") (pin "B5") (pinfunction "CC2_B5") (pintype "passive"))
    )
    (net (code "16") (name "EN_PORT1") (class "Default")
      (node (ref "IC12") (pin "4") (pinfunction "EN_4") (pintype "input"))
      (node (ref "IC42") (pin "25") (pinfunction "IO2.0_25") (pintype "bidirectional"))
      (node (ref "R230") (pin "1") (pinfunction "1_1") (pintype "passive"))
    )
    (net (code "17") (name "EN_PORT2") (class "Default")
      (node (ref "IC42") (pin "26") (pinfunction "IO2.1_26") (pintype "bidirectional"))
    )
    (net (code "18") (name "EN_PORT3") (class "Default")
      (node (ref "IC42") (pin "27") (pinfunction "IO2.2_27") (pintype "bidirectional"))
    )
    (net (code "19") (name "EN_PORT4") (class "Default")
      (node (ref "IC42") (pin "28") (pinfunction "IO2.3_28") (pintype "bidirectional"))
    )
    (net (code "20") (name "EN_PORT5") (class "Default")
      (node (ref "IC42") (pin "1") (pinfunction "IO2.4_1") (pintype "bidirectional"))
    )
    (net (code "21") (name "EN_PORT6") (class "Default")
      (node (ref "IC42") (pin "2") (pinfunction "IO2.5_2") (pintype "bidirectional"))
    )
    (net (code "22") (name "EN_PORT7") (class "Default")
      (node (ref "IC42") (pin "3") (pinfunction "IO2.6_3") (pintype "bidirectional"))
    )
    (net (code "23") (name "EN_PORT8") (class "Default")
      (node (ref "IC42") (pin "4") (pinfunction "IO2.7_4") (pintype "bidirectional"))
    )
    (net (code "24") (name "GND") (class "Default")
      (node (ref "C1") (pin "2") (pinfunction "2_2") (pintype "passive"))
      (node (ref "C10") (pin "2") (pinfunction "-_2") (pintype "passive"))
      (node (ref "C11") (pin "2") (pinfunction "2_2") (pintype "passive"))
      (node (ref "C12") (pin "2") (pinfunction "2_2") (pintype "passive"))
      (node (ref "C13") (pin "2") (pinfunction "2_2") (pintype "passive"))
      (node (ref "C14") (pin "2") (pinfunction "2_2") (pintype "passive"))
      (node (ref "C15") (pin "2") (pinfunction "-_2") (pintype "passive"))
      (node (ref "C16") (pin "2") (pinfunction "2_2") (pintype "passive"))
      (node (ref "C17") (pin "2") (pinfunction "2_2") (pintype "passive"))
      (node (ref "C176") (pin "2") (pinfunction "2_2") (pintype "passive"))
      (node (ref "C177") (pin "2") (pinfunction "2_2") (pintype "passive"))
      (node (ref "C178") (pin "2") (pinfunction "2_2") (pintype "passive"))
      (node (ref "C179") (pin "2") (pinfunction "2_2") (pintype "passive"))
      (node (ref "C18") (pin "2") (pinfunction "2_2") (pintype "passive"))
      (node (ref "C180") (pin "2") (pinfunction "2_2") (pintype "passive"))
      (node (ref "C181") (pin "2") (pinfunction "2_2") (pintype "passive"))
      (node (ref "C182") (pin "2") (pinfunction "2_2") (pintype "passive"))
      (node (ref "C183") (pin "2") (pinfunction "2_2") (pintype "passive"))
      (node (ref "C184") (pin "2") (pinfunction "2_2") (pintype "passive"))
      (node (ref "C185") (pin "2") (pinfunction "2_2") (pintype "passive"))
      (node (ref "C186") (pin "2") (pinfunction "2_2") (pintype "passive"))
      (node (ref "C187") (pin "2") (pinfunction "2_2") (pintype "passive"))
      (node (ref "C188") (pin "2") (pinfunction "2_2") (pintype "passive"))
      (node (ref "C189") (pin "2") (pinfunction "2_2") (pintype "passive"))
      (node (ref "C19") (pin "2") (pinfunction "2_2") (pintype "passive"))
      (node (ref "C190") (pin "2") (pinfunction "2_2") (pintype "passive"))
      (node (ref "C191") (pin "2") (pinfunction "2_2") (pintype "passive"))
      (node (ref "C192") (pin "2") (pinfunction "2_2") (pintype "passive"))
      (node (ref "C193") (pin "2") (pinfunction "2_2") (pintype "passive"))
      (node (ref "C194") (pin "2") (pinfunction "2_2") (pintype "passive"))
      (node (ref "C195") (pin "2") (pinfunction "2_2") (pintype "passive"))
      (node (ref "C2") (pin "2") (pinfunction "2_2") (pintype "passive"))
      (node (ref "C20") (pin "2") (pinfunction "2_2") (pintype "passive"))
      (node (ref "C21") (pin "2") (pinfunction "2_2") (pintype "passive"))
      (node (ref "C212") (pin "2") (pinfunction "2_2") (pintype "passive"))
      (node (ref "C213") (pin "2") (pinfunction "2_2") (pintype "passive"))
      (node (ref "C214") (pin "2") (pinfunction "2_2") (pintype "passive"))
      (node (ref "C215") (pin "2") (pinfunction "2_2") (pintype "passive"))
      (node (ref "C216") (pin "2") (pinfunction "2_2") (pintype "passive"))
      (node (ref "C217") (pin "2") (pinfunction "2_2") (pintype "passive"))
      (node (ref "C218") (pin "2") (pinfunction "-_2") (pintype "passive"))
      (node (ref "C22") (pin "2") (pinfunction "2_2") (pintype "passive"))
      (node (ref "C221") (pin "2") (pinfunction "2_2") (pintype "passive"))
      (node (ref "C222") (pin "2") (pinfunction "2_2") (pintype "passive"))
      (node (ref "C223") (pin "2") (pinfunction "2_2") (pintype "passive"))
      (node (ref "C224") (pin "2") (pinfunction "2_2") (pintype "passive"))
      (node (ref "C225") (pin "2") (pinfunction "2_2") (pintype "passive"))
      (node (ref "C226") (pin "2") (pinfunction "2_2") (pintype "passive"))
      (node (ref "C227") (pin "2") (pinfunction "2_2") (pintype "passive"))
      (node (ref "C228") (pin "2") (pinfunction "2_2") (pintype "passive"))
      (node (ref "C229") (pin "2") (pinfunction "2_2") (pintype "passive"))
      (node (ref "C23") (pin "2") (pinfunction "2_2") (pintype "passive"))
      (node (ref "C233") (pin "2") (pinfunction "2_2") (pintype "passive"))
      (node (ref "C234") (pin "2") (pinfunction "2_2") (pintype "passive"))
      (node (ref "C237") (pin "2") (pinfunction "2_2") (pintype "passive"))
      (node (ref "C238") (pin "2") (pinfunction "2_2") (pintype "passive"))
      (node (ref "C239") (pin "2") (pinfunction "2_2") (pintype "passive"))
      (node (ref "C24") (pin "2") (pinfunction "2_2") (pintype "passive"))
      (node (ref "C247") (pin "2") (pinfunction "2_2") (pintype "passive"))
      (node (ref "C248") (pin "2") (pinfunction "2_2") (pintype "passive"))
      (node (ref "C249") (pin "2") (pinfunction "2_2") (pintype "passive"))
      (node (ref "C25") (pin "2") (pinfunction "2_2") (pintype "passive"))
      (node (ref "C251") (pin "2") (pinfunction "2_2") (pintype "passive"))
      (node (ref "C252") (pin "2") (pinfunction "-_2") (pintype "passive"))
      (node (ref "C253") (pin "2") (pinfunction "-_2") (pintype "passive"))
      (node (ref "C254") (pin "2") (pinfunction "-_2") (pintype "passive"))
      (node (ref "C255") (pin "2") (pinfunction "-_2") (pintype "passive"))
      (node (ref "C256") (pin "2") (pinfunction "-_2") (pintype "passive"))
      (node (ref "C257") (pin "2") (pinfunction "-_2") (pintype "passive"))
      (node (ref "C26") (pin "2") (pinfunction "2_2") (pintype "passive"))
      (node (ref "C264") (pin "2") (pinfunction "2_2") (pintype "passive"))
      (node (ref "C27") (pin "2") (pinfunction "2_2") (pintype "passive"))
      (node (ref "C278") (pin "2") (pinfunction "2_2") (pintype "passive"))
      (node (ref "C28") (pin "2") (pinfunction "2_2") (pintype "passive"))
      (node (ref "C29") (pin "2") (pinfunction "2_2") (pintype "passive"))
      (node (ref "C3") (pin "2") (pinfunction "2_2") (pintype "passive"))
      (node (ref "C30") (pin "2") (pinfunction "2_2") (pintype "passive"))
      (node (ref "C31") (pin "1") (pinfunction "1_1") (pintype "passive"))
      (node (ref "C32") (pin "2") (pinfunction "2_2") (pintype "passive"))
      (node (ref "C35") (pin "2") (pinfunction "2_2") (pintype "passive"))
      (node (ref "C36") (pin "2") (pinfunction "2_2") (pintype "passive"))
      (node (ref "C37") (pin "2") (pinfunction "2_2") (pintype "passive"))
      (node (ref "C38") (pin "2") (pinfunction "2_2") (pintype "passive"))
      (node (ref "C39") (pin "2") (pinfunction "2_2") (pintype "passive"))
      (node (ref "C4") (pin "2") (pinfunction "2_2") (pintype "passive"))
      (node (ref "C40") (pin "1") (pinfunction "1_1") (pintype "passive"))
      (node (ref "C41") (pin "2") (pinfunction "2_2") (pintype "passive"))
      (node (ref "C42") (pin "2") (pinfunction "2_2") (pintype "passive"))
      (node (ref "C43") (pin "2") (pinfunction "2_2") (pintype "passive"))
      (node (ref "C44") (pin "2") (pinfunction "2_2") (pintype "passive"))
      (node (ref "C47") (pin "2") (pinfunction "2_2") (pintype "passive"))
      (node (ref "C48") (pin "2") (pinfunction "2_2") (pintype "passive"))
      (node (ref "C49") (pin "2") (pinfunction "2_2") (pintype "passive"))
      (node (ref "C5") (pin "2") (pinfunction "-_2") (pintype "passive"))
      (node (ref "C50") (pin "2") (pinfunction "-_2") (pintype "passive"))
      (node (ref "C51") (pin "2") (pinfunction "2_2") (pintype "passive"))
      (node (ref "C52") (pin "2") (pinfunction "2_2") (pintype "passive"))
      (node (ref "C53") (pin "2") (pinfunction "2_2") (pintype "passive"))
      (node (ref "C54") (pin "2") (pinfunction "2_2") (pintype "passive"))
      (node (ref "C55") (pin "2") (pinfunction "2_2") (pintype "passive"))
      (node (ref "C6") (pin "2") (pinfunction "2_2") (pintype "passive"))
      (node (ref "C7") (pin "2") (pinfunction "2_2") (pintype "passive"))
      (node (ref "C8") (pin "2") (pinfunction "2_2") (pintype "passive"))
      (node (ref "C82") (pin "2") (pinfunction "2_2") (pintype "passive"))
      (node (ref "C83") (pin "2") (pinfunction "2_2") (pintype "passive"))
      (node (ref "C84") (pin "2") (pinfunction "2_2") (pintype "passive"))
      (node (ref "C85") (pin "2") (pinfunction "-_2") (pintype "passive"))
      (node (ref "C9") (pin "2") (pinfunction "2_2") (pintype "passive"))
      (node (ref "D10") (pin "A") (pinfunction "A_A") (pintype "passive"))
      (node (ref "D11") (pin "A") (pinfunction "A_A") (pintype "passive"))
      (node (ref "D12") (pin "2") (pinfunction "2_2") (pintype "power_in"))
      (node (ref "D13") (pin "2") (pinfunction "2_2") (pintype "power_in"))
      (node (ref "D2") (pin "C") (pinfunction "C_C") (pintype "passive"))
      (node (ref "D4") (pin "C") (pinfunction "C_C") (pintype "passive"))
      (node (ref "D6") (pin "C") (pinfunction "C_C") (pintype "passive"))
      (node (ref "D8") (pin "C") (pinfunction "C_C") (pintype "passive"))
      (node (ref "D9") (pin "A") (pinfunction "A_A") (pintype "passive"))
      (node (ref "DISP") (pin "5") (pinfunction "5_5") (pintype "bidirectional"))
      (node (ref "DISP") (pin "8") (pinfunction "8_8") (pintype "bidirectional"))
      (node (ref "DISP") (pin "Z0") (pinfunction "Z1_Z0") (pintype "bidirectional"))
      (node (ref "DISP") (pin "Z1") (pinfunction "Z1_Z1") (pintype "bidirectional"))
      (node (ref "DISP") (pin "Z2") (pinfunction "Z2_Z2") (pintype "bidirectional"))
      (node (ref "DISP") (pin "Z3") (pinfunction "Z3_Z3") (pintype "bidirectional"))
      (node (ref "DISP") (pin "Z4") (pinfunction "Z3_Z4") (pintype "bidirectional"))
      (node (ref "DISP") (pin "Z5") (pinfunction "Z4_Z5") (pintype "bidirectional"))
      (node (ref "ESD1") (pin "1") (pinfunction "A_1") (pintype "bidirectional"))
      (node (ref "ETH1") (pin "8") (pinfunction "GND_8") (pintype "power_in"))
      (node (ref "IC1") (pin "2") (pinfunction "GND_2") (pintype "bidirectional"))
      (node (ref "IC12") (pin "10") (pinfunction "AGND_10") (pintype "power_in"))
      (node (ref "IC12") (pin "24") (pinfunction "PGND_24") (pintype "power_in"))
      (node (ref "IC12") (pin "9") (pinfunction "PGND_9") (pintype "power_in"))
      (node (ref "IC13") (pin "3") (pinfunction "GND_3") (pintype "bidirectional"))
      (node (ref "IC13") (pin "7") (pinfunction "A0_7") (pintype "bidirectional"))
      (node (ref "IC13") (pin "8") (pinfunction "A1_8") (pintype "bidirectional"))
      (node (ref "IC2") (pin "2") (pinfunction "GND_2") (pintype "bidirectional"))
      (node (ref "IC26") (pin "62") (pinfunction "VREG_PGND_62") (pintype "power_in"))
      (node (ref "IC26") (pin "81") (pinfunction "GND_81") (pintype "power_in"))
      (node (ref "IC27") (pin "4") (pinfunction "GND_4") (pintype "power_in"))
      (node (ref "IC27") (pin "PAD") (pinfunction "GND_PAD") (pintype "power_in"))
      (node (ref "IC28") (pin "5") (pinfunction "V-_5") (pintype "power_in"))
      (node (ref "IC29") (pin "2") (pinfunction "A1_2") (pintype "bidirectional"))
      (node (ref "IC29") (pin "3") (pinfunction "A2_3") (pintype "bidirectional"))
      (node (ref "IC29") (pin "4") (pinfunction "GND_4") (pintype "power_in"))
      (node (ref "IC29") (pin "7") (pinfunction "WP_7") (pintype "bidirectional"))
      (node (ref "IC29") (pin "9") (pinfunction "GND_9") (pintype "power_in"))
      (node (ref "IC3") (pin "2") (pinfunction "GND_2") (pintype "bidirectional"))
      (node (ref "IC31") (pin "14") (pinfunction "AGND_14") (pintype "power_in"))
      (node (ref "IC31") (pin "16") (pinfunction "AGND_16") (pintype "power_in"))
      (node (ref "IC31") (pin "19") (pinfunction "AGND_19") (pintype "power_in"))
      (node (ref "IC31") (pin "29") (pinfunction "GND_29") (pintype "passive"))
      (node (ref "IC31") (pin "3") (pinfunction "AGND_3") (pintype "power_in"))
      (node (ref "IC31") (pin "48") (pinfunction "AGND_48") (pintype "power_in"))
      (node (ref "IC31") (pin "9") (pinfunction "AGND_9") (pintype "power_in"))
      (node (ref "IC38") (pin "18") (pinfunction "A2_18") (pintype "input"))
      (node (ref "IC38") (pin "22") (pinfunction "A0_22") (pintype "input"))
      (node (ref "IC38") (pin "23") (pinfunction "A1_23") (pintype "input"))
      (node (ref "IC38") (pin "25") (pinfunction "GND_25") (pintype "power_in"))
      (node (ref "IC38") (pin "9") (pinfunction "GND_9") (pintype "power_in"))
      (node (ref "IC4") (pin "3") (pinfunction "V-_3") (pintype "bidirectional"))
      (node (ref "IC40") (pin "4") (pinfunction "GND_4") (pintype "bidirectional"))
      (node (ref "IC42") (pin "11") (pinfunction "A0_11") (pintype "bidirectional"))
      (node (ref "IC42") (pin "12") (pinfunction "A1_12") (pintype "bidirectional"))
      (node (ref "IC42") (pin "13") (pinfunction "A2_13") (pintype "bidirectional"))
      (node (ref "IC42") (pin "6") (pinfunction "VSS_6") (pintype "bidirectional"))
      (node (ref "IC42") (pin "PAD") (pinfunction "VSS_PAD") (pintype "bidirectional"))
      (node (ref "IC5") (pin "3") (pinfunction "V-_3") (pintype "bidirectional"))
      (node (ref "IC6") (pin "3") (pinfunction "V-_3") (pintype "bidirectional"))
      (node (ref "IC7") (pin "3") (pinfunction "V-_3") (pintype "bidirectional"))
      (node (ref "IC8") (pin "2") (pinfunction "GND_2") (pintype "bidirectional"))
      (node (ref "IC9") (pin "6") (pinfunction "GND_6") (pintype "power_in"))
      (node (ref "J8") (pin "4") (pinfunction "4_4") (pintype "passive"))
      (node (ref "J8") (pin "5") (pinfunction "5_5") (pintype "passive"))
      (node (ref "J8") (pin "6") (pinfunction "6_6") (pintype "passive"))
      (node (ref "PORT1") (pin "A12") (pinfunction "GND1_A12") (pintype "passive"))
      (node (ref "PORT1") (pin "B12") (pinfunction "GND2_B12") (pintype "passive"))
      (node (ref "R2") (pin "1") (pinfunction "1_1") (pintype "passive"))
      (node (ref "R214") (pin "1") (pinfunction "1_1") (pintype "passive"))
      (node (ref "R225") (pin "1") (pinfunction "1_1") (pintype "passive"))
      (node (ref "R230") (pin "2") (pinfunction "2_2") (pintype "passive"))
      (node (ref "R242") (pin "2") (pinfunction "2_2") (pintype "passive"))
      (node (ref "R249") (pin "2") (pinfunction "2_2") (pintype "passive"))
      (node (ref "R250") (pin "2") (pinfunction "2_2") (pintype "passive"))
      (node (ref "R251") (pin "2") (pinfunction "2_2") (pintype "passive"))
      (node (ref "R255") (pin "2") (pinfunction "2_2") (pintype "passive"))
      (node (ref "R3") (pin "2") (pinfunction "2_2") (pintype "passive"))
      (node (ref "R32") (pin "2") (pinfunction "2_2") (pintype "passive"))
      (node (ref "R36") (pin "1") (pinfunction "1_1") (pintype "passive"))
      (node (ref "R45") (pin "1") (pinfunction "1_1") (pintype "passive"))
      (node (ref "R49") (pin "2") (pinfunction "2_2") (pintype "passive"))
      (node (ref "R50") (pin "1") (pinfunction "1_1") (pintype "passive"))
      (node (ref "R51") (pin "2") (pinfunction "2_2") (pintype "passive"))
      (node (ref "R52") (pin "2") (pinfunction "2_2") (pintype "passive"))
      (node (ref "R58") (pin "2") (pinfunction "2_2") (pintype "passive"))
      (node (ref "R59") (pin "2") (pinfunction "2_2") (pintype "passive"))
      (node (ref "R6") (pin "2") (pinfunction "2_2") (pintype "passive"))
      (node (ref "R60") (pin "2") (pinfunction "2_2") (pintype "passive"))
      (node (ref "R61") (pin "2") (pinfunction "2_2") (pintype "passive"))
      (node (ref "R8") (pin "1") (pinfunction "1_1") (pintype "passive"))
      (node (ref "R84") (pin "2") (pinfunction "2_2") (pintype "passive"))
      (node (ref "R9") (pin "2") (pinfunction "2_2") (pintype "passive"))
      (node (ref "REF1") (pin "2") (pinfunction "A_2") (pintype "passive"))
      (node (ref "REF1") (pin "3") (pinfunction "A_3") (pintype "passive"))
      (node (ref "RFB4") (pin "2") (pinfunction "2_2") (pintype "passive"))
      (node (ref "SW1") (pin "1") (pinfunction "P$1_1") (pintype "bidirectional"))
      (node (ref "SW2") (pin "2") (pinfunction "P$2_2") (pintype "bidirectional"))
      (node (ref "T9") (pin "1") (pinfunction "S_1") (pintype "passive"))
      (node (ref "T9") (pin "2") (pinfunction "S_2") (pintype "passive"))
      (node (ref "T9") (pin "3") (pinfunction "S_3") (pintype "passive"))
      (node (ref "USB9") (pin "GND") (pinfunction "GND_GND") (pintype "power_in"))
      (node (ref "USB9") (pin "GND2") (pinfunction "GND_GND2") (pintype "power_in"))
      (node (ref "USBA_1-2") (pin "4") (pinfunction "GND_4") (pintype "passive"))
      (node (ref "USBA_1-2") (pin "8") (pinfunction "GND_8") (pintype "passive"))
      (node (ref "USBA_3-4") (pin "4") (pinfunction "GND_4") (pintype "passive"))
      (node (ref "USBA_3-4") (pin "8") (pinfunction "GND_8") (pintype "passive"))
      (node (ref "X1") (pin "2") (pinfunction "GND_2") (pintype "passive"))
      (node (ref "X1") (pin "4") (pinfunction "GND_4") (pintype "passive"))
      (node (ref "X2") (pin "2") (pinfunction "GND_2") (pintype "passive"))
      (node (ref "X2") (pin "4") (pinfunction "GND_4") (pintype "passive"))
    )
    (net (code "25") (name "I2C0_SCL") (class "Default")
      (node (ref "D12") (pin "3") (pinfunction "3_3") (pintype "bidirectional"))
      (node (ref "IC26") (pin "2") (pinfunction "GPIO5_2") (pintype "bidirectional"))
      (node (ref "IC38") (pin "19") (pinfunction "SCL_19") (pintype "bidirectional"))
      (node (ref "R207") (pin "A1") (pinfunction "1_A1") (pintype "passive"))
    )
    (net (code "26") (name "I2C0_SDA") (class "Default")
      (node (ref "D12") (pin "1") (pinfunction "1_1") (pintype "bidirectional"))
      (node (ref "IC26") (pin "1") (pinfunction "GPIO4_1") (pintype "bidirectional"))
      (node (ref "IC38") (pin "20") (pinfunction "SDA_20") (pintype "bidirectional"))
      (node (ref "R207") (pin "B1") (pinfunction "2_B1") (pintype "passive"))
    )
    (net (code "27") (name "I2C1_SCL") (class "Default")
      (node (ref "D12") (pin "6") (pinfunction "6_6") (pintype "bidirectional"))
      (node (ref "DISP") (pin "7") (pinfunction "7_7") (pintype "bidirectional"))
      (node (ref "IC26") (pin "4") (pinfunction "GPIO7_4") (pintype "bidirectional"))
      (node (ref "IC29") (pin "6") (pinfunction "SCL_6") (pintype "bidirectional"))
      (node (ref "IC42") (pin "8") (pinfunction "SCL_8") (pintype "bidirectional"))
      (node (ref "R207") (pin "C1") (pinfunction "3_C1") (pintype "passive"))
    )
    (net (code "28") (name "I2C1_SDA") (class "Default")
      (node (ref "D12") (pin "4") (pinfunction "4_4") (pintype "bidirectional"))
      (node (ref "DISP") (pin "6") (pinfunction "6_6") (pintype "bidirectional"))
      (node (ref "IC26") (pin "3") (pinfunction "GPIO6_3") (pintype "bidirectional"))
      (node (ref "IC29") (pin "5") (pinfunction "SDA_5") (pintype "bidirectional"))
      (node (ref "IC42") (pin "9") (pinfunction "SDA_9") (pintype "bidirectional"))
      (node (ref "R207") (pin "D1") (pinfunction "4_D1") (pintype "passive"))
    )
    (net (code "29") (name "IN1_PORT1") (class "Default")
      (node (ref "IC13") (pin "1") (pinfunction "IN+_1") (pintype "bidirectional"))
      (node (ref "IC9") (pin "12") (pinfunction "VBUS_SENSE_12") (pintype "input"))
      (node (ref "R57") (pin "1") (pinfunction "1_1") (pintype "passive"))
      (node (ref "T8") (pin "5") (pinfunction "D_5") (pintype "passive"))
      (node (ref "T8") (pin "6") (pinfunction "D_6") (pintype "passive"))
      (node (ref "T8") (pin "7") (pinfunction "D_7") (pintype "passive"))
      (node (ref "T8") (pin "8") (pinfunction "D_8") (pintype "passive"))
      (node (ref "T8") (pin "9") (pinfunction "D_9") (pintype "passive"))
    )
    (net (code "30") (name "IN2_PORT1") (class "Default")
      (node (ref "IC13") (pin "2") (pinfunction "IN-_2") (pintype "bidirectional"))
      (node (ref "PORT1") (pin "A9") (pinfunction "VBUS1_A9") (pintype "passive"))
      (node (ref "PORT1") (pin "B9") (pinfunction "VBUS2_B9") (pintype "passive"))
      (node (ref "R57") (pin "2") (pinfunction "2_2") (pintype "passive"))
    )
    (net (code "31") (name "KEY_0") (class "Default")
      (node (ref "D13") (pin "6") (pinfunction "6_6") (pintype "bidirectional"))
      (node (ref "DISP") (pin "12") (pinfunction "12_12") (pintype "bidirectional"))
      (node (ref "IC26") (pin "25") (pinfunction "GPIO24_25") (pintype "bidirectional"))
    )
    (net (code "32") (name "KEY_1") (class "Default")
      (node (ref "D13") (pin "4") (pinfunction "4_4") (pintype "bidirectional"))
      (node (ref "DISP") (pin "11") (pinfunction "11_11") (pintype "bidirectional"))
      (node (ref "IC26") (pin "26") (pinfunction "GPIO25_26") (pintype "bidirectional"))
    )
    (net (code "33") (name "KEY_2") (class "Default")
      (node (ref "D13") (pin "3") (pinfunction "3_3") (pintype "bidirectional"))
      (node (ref "DISP") (pin "10") (pinfunction "10_10") (pintype "bidirectional"))
      (node (ref "IC26") (pin "27") (pinfunction "GPIO26_27") (pintype "bidirectional"))
    )
    (net (code "34") (name "KEY_3") (class "Default")
      (node (ref "D13") (pin "1") (pinfunction "1_1") (pintype "bidirectional"))
      (node (ref "DISP") (pin "9") (pinfunction "9_9") (pintype "bidirectional"))
      (node (ref "IC26") (pin "28") (pinfunction "GPIO27_28") (pintype "bidirectional"))
    )
    (net (code "35") (name "LCD_BL") (class "Default")
      (node (ref "DISP") (pin "13") (pinfunction "13_13") (pintype "bidirectional"))
    )
    (net (code "36") (name "LCD_RES") (class "Default")
      (node (ref "DISP") (pin "14") (pinfunction "14_14") (pintype "bidirectional"))
    )
    (net (code "37") (name "MCP_DSP_RST") (class "Default")
      (node (ref "DISP") (pin "20") (pinfunction "20_20") (pintype "bidirectional"))
      (node (ref "R252") (pin "1") (pinfunction "1_1") (pintype "passive"))
    )
    (net (code "38") (name "MCP_REL_RST") (class "Default")
      (node (ref "IC42") (pin "14") (pinfunction "~{RESET}_14") (pintype "bidirectional"))
    )
    (net (code "39") (name "Net-(C31-Pad2)") (class "Default")
      (node (ref "C31") (pin "2") (pinfunction "2_2") (pintype "passive"))
      (node (ref "ETH1") (pin "13") (pinfunction "SHIELD_13") (pintype "passive"))
      (node (ref "ETH1") (pin "14") (pinfunction "SHIELD_14") (pintype "passive"))
      (node (ref "R36") (pin "2") (pinfunction "2_2") (pintype "passive"))
    )
    (net (code "40") (name "Net-(C44-Pad1)") (class "Default")
      (node (ref "C44") (pin "1") (pinfunction "1_1") (pintype "passive"))
      (node (ref "R62") (pin "2") (pinfunction "2_2") (pintype "passive"))
    )
    (net (code "41") (name "Net-(C46-Pad1)") (class "Default")
      (node (ref "C46") (pin "1") (pinfunction "1_1") (pintype "passive"))
      (node (ref "IC12") (pin "21") (pinfunction "SW2_21") (pintype "power_in"))
      (node (ref "IC12") (pin "25") (pinfunction "SW2_25") (pintype "power_in"))
      (node (ref "L2") (pin "2") (pinfunction "2_2") (pintype "passive"))
      (node (ref "R232") (pin "1") (pinfunction "1_1") (pintype "passive"))
    )
    (net (code "42") (name "Net-(C215-Pad1)") (class "Default")
      (node (ref "C215") (pin "1") (pinfunction "1_1") (pintype "passive"))
      (node (ref "R231") (pin "2") (pinfunction "2_2") (pintype "passive"))
    )
    (net (code "43") (name "Net-(C216-Pad1)") (class "Default")
      (node (ref "C216") (pin "1") (pinfunction "1_1") (pintype "passive"))
      (node (ref "R232") (pin "2") (pinfunction "2_2") (pintype "passive"))
    )
    (net (code "44") (name "Net-(C235-Pad1)") (class "Default")
      (node (ref "C235") (pin "1") (pinfunction "1_1") (pintype "passive"))
      (node (ref "R243") (pin "1") (pinfunction "1_1") (pintype "passive"))
    )
    (net (code "45") (name "Net-(C236-Pad2)") (class "Default")
      (node (ref "C236") (pin "2") (pinfunction "2_2") (pintype "passive"))
      (node (ref "RFB3") (pin "2") (pinfunction "2_2") (pintype "passive"))
      (node (ref "RFB4") (pin "1") (pinfunction "1_1") (pintype "passive"))
      (node (ref "RT1") (pin "2") (pinfunction "2_2") (pintype "passive"))
    )
    (net (code "46") (name "Net-(D1-PadC)") (class "Default")
      (node (ref "D1") (pin "C") (pinfunction "C_C") (pintype "passive"))
      (node (ref "R14") (pin "2") (pinfunction "2_2") (pintype "passive"))
    )
    (net (code "47") (name "Net-(D2-PadA)") (class "Default")
      (node (ref "D2") (pin "A") (pinfunction "A_A") (pintype "passive"))
      (node (ref "R12") (pin "2") (pinfunction "2_2") (pintype "passive"))
    )
    (net (code "48") (name "Net-(D3-PadC)") (class "Default")
      (node (ref "D3") (pin "C") (pinfunction "C_C") (pintype "passive"))
      (node (ref "R17") (pin "2") (pinfunction "2_2") (pintype "passive"))
    )
    (net (code "49") (name "Net-(D4-PadA)") (class "Default")
      (node (ref "D4") (pin "A") (pinfunction "A_A") (pintype "passive"))
      (node (ref "R15") (pin "1") (pinfunction "1_1") (pintype "passive"))
    )
    (net (code "50") (name "Net-(D5-PadC)") (class "Default")
      (node (ref "D5") (pin "C") (pinfunction "C_C") (pintype "passive"))
      (node (ref "R20") (pin "2") (pinfunction "2_2") (pintype "passive"))
    )
    (net (code "51") (name "Net-(D6-PadA)") (class "Default")
      (node (ref "D6") (pin "A") (pinfunction "A_A") (pintype "passive"))
      (node (ref "R18") (pin "1") (pinfunction "1_1") (pintype "passive"))
    )
    (net (code "52") (name "Net-(D7-PadC)") (class "Default")
      (node (ref "D7") (pin "C") (pinfunction "C_C") (pintype "passive"))
      (node (ref "R23") (pin "2") (pinfunction "2_2") (pintype "passive"))
    )
    (net (code "53") (name "Net-(D8-PadA)") (class "Default")
      (node (ref "D8") (pin "A") (pinfunction "A_A") (pintype "passive"))
      (node (ref "R21") (pin "1") (pinfunction "1_1") (pintype "passive"))
    )
    (net (code "54") (name "Net-(ETH1-GREEN-)") (class "Default")
      (node (ref "ETH1") (pin "9") (pinfunction "GREEN-_9") (pintype "passive"))
      (node (ref "R34") (pin "2") (pinfunction "2_2") (pintype "passive"))
    )
    (net (code "55") (name "Net-(ETH1-YELLOW-)") (class "Default")
      (node (ref "ETH1") (pin "11") (pinfunction "YELLOW-_11") (pintype "passive"))
      (node (ref "R33") (pin "2") (pinfunction "2_2") (pintype "passive"))
    )
    (net (code "56") (name "Net-(F1-1-Pad1_1)") (class "Default")
      (node (ref "F1") (pin "1_1") (pinfunction "1_1_1") (pintype "passive"))
      (node (ref "F1") (pin "1_2") (pinfunction "1_1_2") (pintype "passive"))
      (node (ref "J8") (pin "1") (pinfunction "1_1") (pintype "passive"))
    )
    (net (code "57") (name "Net-(F2-1-Pad1_1)") (class "Default")
      (node (ref "F2") (pin "1_1") (pinfunction "1_1_1") (pintype "passive"))
      (node (ref "F2") (pin "1_2") (pinfunction "1_1_2") (pintype "passive"))
      (node (ref "J8") (pin "2") (pinfunction "2_2") (pintype "passive"))
    )
    (net (code "58") (name "Net-(F3-1-Pad1_1)") (class "Default")
      (node (ref "F3") (pin "1_1") (pinfunction "1_1_1") (pintype "passive"))
      (node (ref "F3") (pin "1_2") (pinfunction "1_1_2") (pintype "passive"))
      (node (ref "J8") (pin "3") (pinfunction "3_3") (pintype "passive"))
    )
    (net (code "59") (name "Net-(IC1-ILIM)") (class "Default")
      (node (ref "IC1") (pin "5") (pinfunction "ILIM_5") (pintype "bidirectional"))
      (node (ref "R3") (pin "1") (pinfunction "1_1") (pintype "passive"))
    )
    (net (code "60") (name "Net-(IC2-ILIM)") (class "Default")
      (node (ref "IC2") (pin "5") (pinfunction "ILIM_5") (pintype "bidirectional"))
      (node (ref "R6") (pin "1") (pinfunction "1_1") (pintype "passive"))
    )
    (net (code "61") (name "Net-(IC3-ILIM)") (class "Default")
      (node (ref "IC3") (pin "5") (pinfunction "ILIM_5") (pintype "bidirectional"))
      (node (ref "R9") (pin "1") (pinfunction "1_1") (pintype "passive"))
    )
    (net (code "62") (name "Net-(IC4-OUT)") (class "Default")
      (node (ref "IC4") (pin "4") (pinfunction "OUT_4") (pintype "bidirectional"))
      (node (ref "R12") (pin "1") (pinfunction "1_1") (pintype "passive"))
      (node (ref "R14") (pin "1") (pinfunction "1_1") (pintype "passive"))
    )
    (net (code "63") (name "Net-(IC5-OUT)") (class "Default")
      (node (ref "IC5") (pin "4") (pinfunction "OUT_4") (pintype "bidirectional"))
      (node (ref "R15") (pin "2") (pinfunction "2_2") (pintype "passive"))
      (node (ref "R17") (pin "1") (pinfunction "1_1") (pintype "passive"))
    )
    (net (code "64") (name "Net-(IC6-OUT)") (class "Default")
      (node (ref "IC6") (pin "4") (pinfunction "OUT_4") (pintype "bidirectional"))
      (node (ref "R18") (pin "2") (pinfunction "2_2") (pintype "passive"))
      (node (ref "R20") (pin "1") (pinfunction "1_1") (pintype "passive"))
    )
    (net (code "65") (name "Net-(IC7-OUT)") (class "Default")
      (node (ref "IC7") (pin "4") (pinfunction "OUT_4") (pintype "bidirectional"))
      (node (ref "R21") (pin "2") (pinfunction "2_2") (pintype "passive"))
      (node (ref "R23") (pin "1") (pinfunction "1_1") (pintype "passive"))
    )
    (net (code "66") (name "Net-(IC8-ILIM)") (class "Default")
      (node (ref "IC8") (pin "5") (pinfunction "ILIM_5") (pintype "bidirectional"))
      (node (ref "R84") (pin "1") (pinfunction "1_1") (pintype "passive"))
    )
    (net (code "67") (name "Net-(IC9-ADDR0)") (class "Default")
      (node (ref "IC9") (pin "9") (pinfunction "ADDR0_9") (pintype "input"))
      (node (ref "R51") (pin "1") (pinfunction "1_1") (pintype "passive"))
    )
    (net (code "68") (name "Net-(IC9-SEL_PDO2)") (class "Default")
      (node (ref "IC9") (pin "8") (pinfunction "SEL_PDO2_8") (pintype "open_collector"))
      (node (ref "R48") (pin "2") (pinfunction "2_2") (pintype "passive"))
      (node (ref "R49") (pin "1") (pinfunction "1_1") (pintype "passive"))
    )
    (net (code "69") (name "Net-(IC9-SEL_PDO3)") (class "Default")
      (node (ref "IC9") (pin "7") (pinfunction "SEL_PDO3_7") (pintype "open_collector"))
      (node (ref "R47") (pin "2") (pinfunction "2_2") (pintype "passive"))
      (node (ref "R48") (pin "1") (pinfunction "1_1") (pintype "passive"))
    )
    (net (code "70") (name "Net-(IC9-SEL_PDO4)") (class "Default")
      (node (ref "IC9") (pin "10") (pinfunction "SEL_PDO4_10") (pintype "open_collector"))
      (node (ref "R46") (pin "2") (pinfunction "2_2") (pintype "passive"))
      (node (ref "R47") (pin "1") (pinfunction "1_1") (pintype "passive"))
    )
    (net (code "71") (name "Net-(IC9-SEL_PDO5)") (class "Default")
      (node (ref "IC9") (pin "11") (pinfunction "SEL_PDO5_11") (pintype "open_collector"))
      (node (ref "R11") (pin "2") (pinfunction "2_2") (pintype "passive"))
      (node (ref "R46") (pin "1") (pinfunction "1_1") (pintype "passive"))
    )
    (net (code "72") (name "Net-(IC9-VBUS_DISCH)") (class "Default")
      (node (ref "IC9") (pin "13") (pinfunction "VBUS_DISCH_13") (pintype "output"))
      (node (ref "R53") (pin "2") (pinfunction "2_2") (pintype "passive"))
      (node (ref "T6") (pin "4") (pinfunction "G_4") (pintype "passive"))
    )
    (net (code "73") (name "Net-(IC9-VBUS_EN_SRC)") (class "Default")
      (node (ref "IC9") (pin "14") (pinfunction "VBUS_EN_SRC_14") (pintype "open_collector"))
      (node (ref "R55") (pin "2") (pinfunction "2_2") (pintype "passive"))
    )
    (net (code "74") (name "Net-(IC9-VREG1V2)") (class "Default")
      (node (ref "C6") (pin "1") (pinfunction "1_1") (pintype "passive"))
      (node (ref "IC9") (pin "15") (pinfunction "VREG1V2_15") (pintype "input"))
    )
    (net (code "75") (name "Net-(IC9-VREG2V7)") (class "Default")
      (node (ref "C16") (pin "1") (pinfunction "1_1") (pintype "passive"))
      (node (ref "IC9") (pin "16") (pinfunction "VREG2V7_16") (pintype "input"))
    )
    (net (code "76") (name "Net-(IC12-BOOT1)") (class "Default")
      (node (ref "C45") (pin "2") (pinfunction "2_2") (pintype "passive"))
      (node (ref "IC12") (pin "22") (pinfunction "BOOT1_22") (pintype "power_in"))
    )
    (net (code "77") (name "Net-(IC12-BOOT2)") (class "Default")
      (node (ref "C46") (pin "2") (pinfunction "2_2") (pintype "passive"))
      (node (ref "IC12") (pin "20") (pinfunction "BOOT2_20") (pintype "power_in"))
    )
    (net (code "78") (name "Net-(IC12-CDC)") (class "Default")
      (node (ref "IC12") (pin "16") (pinfunction "CDC_16") (pintype "output"))
      (node (ref "R61") (pin "1") (pinfunction "1_1") (pintype "passive"))
    )
    (net (code "79") (name "Net-(IC12-COMP)") (class "Default")
      (node (ref "C43") (pin "1") (pinfunction "1_1") (pintype "passive"))
      (node (ref "IC12") (pin "18") (pinfunction "COMP_18") (pintype "input"))
      (node (ref "R62") (pin "1") (pinfunction "1_1") (pintype "passive"))
    )
    (net (code "80") (name "Net-(IC12-DITH_SYNC)") (class "Default")
      (node (ref "C42") (pin "1") (pinfunction "1_1") (pintype "passive"))
      (node (ref "IC12") (pin "7") (pinfunction "DITH_SYNC_7") (pintype "input"))
    )
    (net (code "81") (name "Net-(IC12-DR1H)") (class "Default")
      (node (ref "IC12") (pin "2") (pinfunction "DR1H_2") (pintype "output"))
      (node (ref "R65") (pin "1") (pinfunction "1_1") (pintype "passive"))
    )
    (net (code "82") (name "Net-(IC12-DR1L)") (class "Default")
      (node (ref "IC12") (pin "1") (pinfunction "DR1L_1") (pintype "output"))
      (node (ref "R64") (pin "1") (pinfunction "1_1") (pintype "passive"))
    )
    (net (code "83") (name "Net-(IC12-FB)") (class "Default")
      (node (ref "IC12") (pin "14") (pinfunction "FB_14") (pintype "input"))
      (node (ref "R11") (pin "1") (pinfunction "1_1") (pintype "passive"))
      (node (ref "R5") (pin "2") (pinfunction "2_2") (pintype "passive"))
    )
    (net (code "84") (name "Net-(IC12-FSW)") (class "Default")
      (node (ref "IC12") (pin "8") (pinfunction "FSW_8") (pintype "input"))
      (node (ref "R59") (pin "1") (pinfunction "1_1") (pintype "passive"))
    )
    (net (code "85") (name "Net-(IC12-ILIM)") (class "Default")
      (node (ref "IC12") (pin "17") (pinfunction "ILIM_17") (pintype "output"))
      (node (ref "R60") (pin "1") (pinfunction "1_1") (pintype "passive"))
    )
    (net (code "86") (name "Net-(IC12-MODE)") (class "Default")
      (node (ref "IC12") (pin "15") (pinfunction "MODE_15") (pintype "input"))
      (node (ref "R58") (pin "1") (pinfunction "1_1") (pintype "passive"))
    )
    (net (code "87") (name "Net-(IC12-SW1)") (class "Default")
      (node (ref "C45") (pin "1") (pinfunction "1_1") (pintype "passive"))
      (node (ref "IC12") (pin "23") (pinfunction "SW1_23") (pintype "power_in"))
      (node (ref "L2") (pin "1") (pinfunction "1_1") (pintype "passive"))
      (node (ref "R231") (pin "1") (pinfunction "1_1") (pintype "passive"))
      (node (ref "T10") (pin "1") (pinfunction "S_1") (pintype "passive"))
      (node (ref "T10") (pin "2") (pinfunction "S_2") (pintype "passive"))
      (node (ref "T10") (pin "3") (pinfunction "S_3") (pintype "passive"))
      (node (ref "T9") (pin "5") (pinfunction "D_5") (pintype "passive"))
      (node (ref "T9") (pin "6") (pinfunction "D_6") (pintype "passive"))
      (node (ref "T9") (pin "7") (pinfunction "D_7") (pintype "passive"))
      (node (ref "T9") (pin "8") (pinfunction "D_8") (pintype "passive"))
      (node (ref "T9") (pin "9") (pinfunction "D_9") (pintype "passive"))
    )
    (net (code "88") (name "Net-(IC12-VCC)") (class "Default")
      (node (ref "C41") (pin "1") (pinfunction "1_1") (pintype "passive"))
      (node (ref "IC12") (pin "19") (pinfunction "VCC_19") (pintype "power_in"))
    )
    (net (code "89") (name "Net-(IC26C-ADC_AVDD)") (class "Default")
      (node (ref "C191") (pin "1") (pinfunction "1_1") (pintype "passive"))
      (node (ref "IC26") (pin "59") (pinfunction "ADC_AVDD_59") (pintype "power_in"))
      (node (ref "R28") (pin "1") (pinfunction "1_1") (pintype "passive"))
      (node (ref "R29") (pin "2") (pinfunction "2_2") (pintype "passive"))
    )
    (net (code "90") (name "Net-(IC26C-RUN)") (class "Default")
      (node (ref "IC26") (pin "35") (pinfunction "RUN_35") (pintype "input"))
      (node (ref "R24") (pin "2") (pinfunction "2_2") (pintype "passive"))
      (node (ref "SW1") (pin "2") (pinfunction "P$2_2") (pintype "bidirectional"))
    )
    (net (code "91") (name "Net-(IC26C-USB_DM)") (class "Default")
      (node (ref "IC26") (pin "66") (pinfunction "USB_DM_66") (pintype "bidirectional"))
      (node (ref "R25") (pin "2") (pinfunction "2_2") (pintype "passive"))
    )
    (net (code "92") (name "Net-(IC26C-USB_DP)") (class "Default")
      (node (ref "IC26") (pin "67") (pinfunction "USB_DP_67") (pintype "bidirectional"))
      (node (ref "R26") (pin "2") (pinfunction "2_2") (pintype "passive"))
    )
    (net (code "93") (name "Net-(IC26C-VREG_AVDD)") (class "Default")
      (node (ref "C21") (pin "1") (pinfunction "1_1") (pintype "passive"))
      (node (ref "IC26") (pin "61") (pinfunction "VREG_AVDD_61") (pintype "power_in"))
      (node (ref "R27") (pin "2") (pinfunction "2_2") (pintype "passive"))
    )
    (net (code "94") (name "Net-(IC26C-VREG_LX)") (class "Default")
      (node (ref "IC26") (pin "63") (pinfunction "VREG_LX_63") (pintype "power_in"))
      (node (ref "L1") (pin "1") (pinfunction "1_1") (pintype "passive"))
    )
    (net (code "95") (name "Net-(IC26C-XIN)") (class "Default")
      (node (ref "C177") (pin "1") (pinfunction "1_1") (pintype "passive"))
      (node (ref "IC26") (pin "30") (pinfunction "XIN_30") (pintype "input"))
      (node (ref "X1") (pin "1") (pinfunction "1_1") (pintype "passive"))
    )
    (net (code "96") (name "Net-(IC26C-XOUT)") (class "Default")
      (node (ref "IC26") (pin "31") (pinfunction "XOUT_31") (pintype "output"))
      (node (ref "R211") (pin "2") (pinfunction "2_2") (pintype "passive"))
    )
    (net (code "97") (name "Net-(IC28-+IN)") (class "Default")
      (node (ref "C179") (pin "1") (pinfunction "1_1") (pintype "passive"))
      (node (ref "C180") (pin "1") (pinfunction "1_1") (pintype "passive"))
      (node (ref "IC28") (pin "3") (pinfunction "+IN_3") (pintype "input"))
      (node (ref "R212") (pin "1") (pinfunction "1_1") (pintype "passive"))
      (node (ref "REF1") (pin "1") (pinfunction "C_1") (pintype "passive"))
      (node (ref "VREF") (pin "TP") (pinfunction "P$1_TP") (pintype "bidirectional"))
    )
    (net (code "98") (name "Net-(IC29-A0)") (class "Default")
      (node (ref "IC29") (pin "1") (pinfunction "A0_1") (pintype "bidirectional"))
      (node (ref "R213") (pin "1") (pinfunction "1_1") (pintype "passive"))
      (node (ref "R214") (pin "2") (pinfunction "2_2") (pintype "passive"))
    )
    (net (code "99") (name "Net-(IC31-1V2O)") (class "Default")
      (node (ref "C35") (pin "1") (pinfunction "1_1") (pintype "passive"))
      (node (ref "IC31") (pin "22") (pinfunction "1V2O_22") (pintype "output"))
    )
    (net (code "100") (name "Net-(IC31-EXRES1)") (class "Default")
      (node (ref "IC31") (pin "10") (pinfunction "EXRES1_10") (pintype "bidirectional"))
      (node (ref "R45") (pin "2") (pinfunction "2_2") (pintype "passive"))
    )
    (net (code "101") (name "Net-(IC31-TOCAP)") (class "Default")
      (node (ref "C36") (pin "1") (pinfunction "1_1") (pintype "passive"))
      (node (ref "IC31") (pin "20") (pinfunction "TOCAP_20") (pintype "output"))
    )
    (net (code "102") (name "Net-(IC31-XI)") (class "Default")
      (node (ref "C38") (pin "1") (pinfunction "1_1") (pintype "passive"))
      (node (ref "IC31") (pin "30") (pinfunction "XI_30") (pintype "input"))
      (node (ref "R205") (pin "1") (pinfunction "1_1") (pintype "passive"))
      (node (ref "X2") (pin "3") (pinfunction "2_3") (pintype "passive"))
    )
    (net (code "103") (name "Net-(IC31-XO)") (class "Default")
      (node (ref "C37") (pin "1") (pinfunction "1_1") (pintype "passive"))
      (node (ref "IC31") (pin "31") (pinfunction "XO_31") (pintype "output"))
      (node (ref "R205") (pin "2") (pinfunction "2_2") (pintype "passive"))
      (node (ref "X2") (pin "1") (pinfunction "1_1") (pintype "passive"))
    )
    (net (code "104") (name "Net-(IC40-AAM)") (class "Default")
      (node (ref "IC40") (pin "1") (pinfunction "AAM_1") (pintype "bidirectional"))
      (node (ref "R242") (pin "1") (pinfunction "1_1") (pintype "passive"))
      (node (ref "R244") (pin "2") (pinfunction "2_2") (pintype "passive"))
    )
    (net (code "105") (name "Net-(IC40-BST)") (class "Default")
      (node (ref "IC40") (pin "5") (pinfunction "BST_5") (pintype "bidirectional"))
      (node (ref "R243") (pin "2") (pinfunction "2_2") (pintype "passive"))
    )
    (net (code "106") (name "Net-(IC40-EN)") (class "Default")
      (node (ref "IC40") (pin "6") (pinfunction "EN_6") (pintype "bidirectional"))
      (node (ref "R241") (pin "2") (pinfunction "2_2") (pintype "passive"))
    )
    (net (code "107") (name "Net-(IC40-FB)") (class "Default")
      (node (ref "IC40") (pin "8") (pinfunction "FB_8") (pintype "bidirectional"))
      (node (ref "RT1") (pin "1") (pinfunction "1_1") (pintype "passive"))
    )
    (net (code "108") (name "Net-(IC40-SW)") (class "Default")
      (node (ref "C235") (pin "2") (pinfunction "2_2") (pintype "passive"))
      (node (ref "IC40") (pin "3") (pinfunction "SW_3") (pintype "bidirectional"))
      (node (ref "L11") (pin "1") (pinfunction "1_1") (pintype "passive"))
    )
    (net (code "109") (name "Net-(IC40-VCC)") (class "Default")
      (node (ref "C234") (pin "1") (pinfunction "1_1") (pintype "passive"))
      (node (ref "IC40") (pin "7") (pinfunction "VCC_7") (pintype "bidirectional"))
      (node (ref "R244") (pin "1") (pinfunction "1_1") (pintype "passive"))
    )
    (net (code "110") (name "Net-(R52-Pad1)") (class "Default")
      (node (ref "R52") (pin "1") (pinfunction "1_1") (pintype "passive"))
      (node (ref "T6") (pin "5") (pinfunction "D_5") (pintype "passive"))
      (node (ref "T6") (pin "6") (pinfunction "D_6") (pintype "passive"))
      (node (ref "T6") (pin "7") (pinfunction "D_7") (pintype "passive"))
      (node (ref "T6") (pin "8") (pinfunction "D_8") (pintype "passive"))
      (node (ref "T6") (pin "9") (pinfunction "D_9") (pintype "passive"))
    )
    (net (code "111") (name "Net-(R54-Pad1)") (class "Default")
      (node (ref "R54") (pin "1") (pinfunction "1_1") (pintype "passive"))
      (node (ref "T7") (pin "1") (pinfunction "S_1") (pintype "passive"))
      (node (ref "T7") (pin "2") (pinfunction "S_2") (pintype "passive"))
      (node (ref "T7") (pin "3") (pinfunction "S_3") (pintype "passive"))
      (node (ref "T8") (pin "1") (pinfunction "S_1") (pintype "passive"))
      (node (ref "T8") (pin "2") (pinfunction "S_2") (pintype "passive"))
      (node (ref "T8") (pin "3") (pinfunction "S_3") (pintype "passive"))
    )
    (net (code "112") (name "Net-(T7-G)") (class "Default")
      (node (ref "R54") (pin "2") (pinfunction "2_2") (pintype "passive"))
      (node (ref "R55") (pin "1") (pinfunction "1_1") (pintype "passive"))
      (node (ref "T7") (pin "4") (pinfunction "G_4") (pintype "passive"))
      (node (ref "T8") (pin "4") (pinfunction "G_4") (pintype "passive"))
    )
    (net (code "113") (name "Net-(T9-G)") (class "Default")
      (node (ref "R64") (pin "2") (pinfunction "2_2") (pintype "passive"))
      (node (ref "T9") (pin "4") (pinfunction "G_4") (pintype "passive"))
    )
    (net (code "114") (name "Net-(T10-G)") (class "Default")
      (node (ref "R65") (pin "2") (pinfunction "2_2") (pintype "passive"))
      (node (ref "T10") (pin "4") (pinfunction "G_4") (pintype "passive"))
    )
    (net (code "115") (name "Net-(USB9-CC1)") (class "Default")
      (node (ref "R251") (pin "1") (pinfunction "1_1") (pintype "passive"))
      (node (ref "USB9") (pin "A5") (pinfunction "CC1_A5") (pintype "bidirectional"))
    )
    (net (code "116") (name "Net-(USB9-CC2)") (class "Default")
      (node (ref "R250") (pin "1") (pinfunction "1_1") (pintype "passive"))
      (node (ref "USB9") (pin "B5") (pinfunction "CC2_B5") (pintype "bidirectional"))
    )
    (net (code "117") (name "Net-(X1-2)") (class "Default")
      (node (ref "C178") (pin "1") (pinfunction "1_1") (pintype "passive"))
      (node (ref "R211") (pin "1") (pinfunction "1_1") (pintype "passive"))
      (node (ref "X1") (pin "3") (pinfunction "2_3") (pintype "passive"))
    )
    (net (code "118") (name "OCP1") (class "Default")
      (node (ref "IC4") (pin "2") (pinfunction "IN_2") (pintype "bidirectional"))
      (node (ref "IC42") (pin "21") (pinfunction "IO1.4_21") (pintype "bidirectional"))
      (node (ref "IC8") (pin "4") (pinfunction "~{FAULT}_4") (pintype "bidirectional"))
      (node (ref "R13") (pin "1") (pinfunction "1_1") (pintype "passive"))
    )
    (net (code "119") (name "OCP2") (class "Default")
      (node (ref "IC1") (pin "4") (pinfunction "~{FAULT}_4") (pintype "bidirectional"))
      (node (ref "IC42") (pin "22") (pinfunction "IO1.5_22") (pintype "bidirectional"))
      (node (ref "IC5") (pin "2") (pinfunction "IN_2") (pintype "bidirectional"))
      (node (ref "R16") (pin "1") (pinfunction "1_1") (pintype "passive"))
    )
    (net (code "120") (name "OCP3") (class "Default")
      (node (ref "IC2") (pin "4") (pinfunction "~{FAULT}_4") (pintype "bidirectional"))
      (node (ref "IC42") (pin "23") (pinfunction "IO1.6_23") (pintype "bidirectional"))
      (node (ref "IC6") (pin "2") (pinfunction "IN_2") (pintype "bidirectional"))
      (node (ref "R19") (pin "1") (pinfunction "1_1") (pintype "passive"))
    )
    (net (code "121") (name "OCP4") (class "Default")
      (node (ref "IC3") (pin "4") (pinfunction "~{FAULT}_4") (pintype "bidirectional"))
      (node (ref "IC42") (pin "24") (pinfunction "IO1.7_24") (pintype "bidirectional"))
      (node (ref "IC7") (pin "2") (pinfunction "IN_2") (pintype "bidirectional"))
      (node (ref "R22") (pin "1") (pinfunction "1_1") (pintype "passive"))
    )
    (net (code "122") (name "P1_IS_N") (class "Default")
      (node (ref "C196") (pin "2") (pinfunction "2_2") (pintype "passive"))
      (node (ref "IC12") (pin "13") (pinfunction "ISN_13") (pintype "input"))
      (node (ref "R229") (pin "1") (pinfunction "1_1") (pintype "passive"))
    )
    (net (code "123") (name "P1_IS_P") (class "Default")
      (node (ref "C196") (pin "1") (pinfunction "1_1") (pintype "passive"))
      (node (ref "IC12") (pin "12") (pinfunction "ISP_12") (pintype "input"))
      (node (ref "R228") (pin "1") (pinfunction "1_1") (pintype "passive"))
    )
    (net (code "124") (name "QMI_CS1") (class "Default")
      (node (ref "IC26") (pin "6") (pinfunction "GPIO8_6") (pintype "bidirectional"))
    )
    (net (code "125") (name "QSPI_SCLK") (class "Default")
      (node (ref "IC26") (pin "71") (pinfunction "QSPI_SCLK_71") (pintype "output"))
      (node (ref "IC27") (pin "6") (pinfunction "CLK_6") (pintype "bidirectional"))
    )
    (net (code "126") (name "QSPI_SD0") (class "Default")
      (node (ref "IC26") (pin "72") (pinfunction "QSPI_SD0_72") (pintype "bidirectional"))
      (node (ref "IC27") (pin "5") (pinfunction "DI/IO0_5") (pintype "bidirectional"))
    )
    (net (code "127") (name "QSPI_SD1") (class "Default")
      (node (ref "IC26") (pin "74") (pinfunction "QSPI_SD1_74") (pintype "bidirectional"))
      (node (ref "IC27") (pin "2") (pinfunction "DO/IO1_2") (pintype "bidirectional"))
    )
    (net (code "128") (name "QSPI_SD2") (class "Default")
      (node (ref "IC26") (pin "73") (pinfunction "QSPI_SD2_73") (pintype "bidirectional"))
      (node (ref "IC27") (pin "3") (pinfunction "~{WP}/IO2_3") (pintype "bidirectional"))
    )
    (net (code "129") (name "QSPI_SD3") (class "Default")
      (node (ref "IC26") (pin "70") (pinfunction "QSPI_SD3_70") (pintype "bidirectional"))
      (node (ref "IC27") (pin "7") (pinfunction "~{HOLD}/IO3_7") (pintype "bidirectional"))
    )
    (net (code "130") (name "RCT") (class "Default")
      (node (ref "C32") (pin "1") (pinfunction "1_1") (pintype "passive"))
      (node (ref "ETH1") (pin "5") (pinfunction "P5/RCT_5") (pintype "passive"))
      (node (ref "R41") (pin "1") (pinfunction "1_1") (pintype "passive"))
      (node (ref "R42") (pin "1") (pinfunction "1_1") (pintype "passive"))
    )
    (net (code "131") (name "RDC_RD_N") (class "Default")
      (node (ref "C33") (pin "1") (pinfunction "1_1") (pintype "passive"))
      (node (ref "R40") (pin "2") (pinfunction "2_2") (pintype "passive"))
      (node (ref "R41") (pin "2") (pinfunction "2_2") (pintype "passive"))
    )
    (net (code "132") (name "RDC_RD_P") (class "Default")
      (node (ref "C34") (pin "1") (pinfunction "1_1") (pintype "passive"))
      (node (ref "R39") (pin "2") (pinfunction "2_2") (pintype "passive"))
      (node (ref "R42") (pin "2") (pinfunction "2_2") (pintype "passive"))
    )
    (net (code "133") (name "RD_N") (class "Default")
      (node (ref "C33") (pin "2") (pinfunction "2_2") (pintype "passive"))
      (node (ref "ETH1") (pin "6") (pinfunction "RD-_6") (pintype "passive"))
    )
    (net (code "134") (name "RD_P") (class "Default")
      (node (ref "C34") (pin "2") (pinfunction "2_2") (pintype "passive"))
      (node (ref "ETH1") (pin "4") (pinfunction "RD+_4") (pintype "passive"))
    )
    (net (code "135") (name "RX_RD_N") (class "Default")
      (node (ref "IC31") (pin "5") (pinfunction "RXN_5") (pintype "input"))
      (node (ref "R40") (pin "1") (pinfunction "1_1") (pintype "passive"))
    )
    (net (code "136") (name "RX_RD_P") (class "Default")
      (node (ref "IC31") (pin "6") (pinfunction "RXP_6") (pintype "input"))
      (node (ref "R39") (pin "1") (pinfunction "1_1") (pintype "passive"))
    )
    (net (code "137") (name "SPI1_CS") (class "Default")
      (node (ref "IC26") (pin "12") (pinfunction "GPIO13_12") (pintype "bidirectional"))
    )
    (net (code "138") (name "SPI1_MISO") (class "Default")
      (node (ref "IC26") (pin "11") (pinfunction "GPIO12_11") (pintype "bidirectional"))
    )
    (net (code "139") (name "SPI1_MOSI") (class "Default")
      (node (ref "IC26") (pin "14") (pinfunction "GPIO15_14") (pintype "bidirectional"))
    )
    (net (code "140") (name "SPI1_SCLK") (class "Default")
      (node (ref "IC26") (pin "13") (pinfunction "GPIO14_13") (pintype "bidirectional"))
    )
    (net (code "141") (name "SWCLK") (class "Default")
      (node (ref "IC26") (pin "33") (pinfunction "SWCLK_33") (pintype "output"))
    )
    (net (code "142") (name "SWDIO") (class "Default")
      (node (ref "IC26") (pin "34") (pinfunction "SWDIO_34") (pintype "bidirectional"))
    )
    (net (code "143") (name "TCA0_I2C_SCL") (class "Default")
      (node (ref "IC38") (pin "2") (pinfunction "SC0_2") (pintype "bidirectional"))
      (node (ref "IC9") (pin "4") (pinfunction "SCL_4") (pintype "input"))
      (node (ref "R215") (pin "C1") (pinfunction "3_C1") (pintype "passive"))
    )
    (net (code "144") (name "TCA0_I2C_SDA") (class "Default")
      (node (ref "IC38") (pin "1") (pinfunction "SD0_1") (pintype "bidirectional"))
      (node (ref "IC9") (pin "5") (pinfunction "SDA_5") (pintype "bidirectional"))
      (node (ref "R215") (pin "D1") (pinfunction "4_D1") (pintype "passive"))
    )
    (net (code "145") (name "TCA1_I2C_SCL") (class "Default")
      (node (ref "IC38") (pin "4") (pinfunction "SC1_4") (pintype "bidirectional"))
      (node (ref "R215") (pin "A1") (pinfunction "1_A1") (pintype "passive"))
    )
    (net (code "146") (name "TCA1_I2C_SDA") (class "Default")
      (node (ref "IC38") (pin "3") (pinfunction "SD1_3") (pintype "bidirectional"))
      (node (ref "R215") (pin "B1") (pinfunction "2_B1") (pintype "passive"))
    )
    (net (code "147") (name "TCA2_I2C_SCL") (class "Default")
      (node (ref "IC38") (pin "6") (pinfunction "SC2_6") (pintype "bidirectional"))
      (node (ref "R216") (pin "C1") (pinfunction "3_C1") (pintype "passive"))
    )
    (net (code "148") (name "TCA2_I2C_SDA") (class "Default")
      (node (ref "IC38") (pin "5") (pinfunction "SD2_5") (pintype "bidirectional"))
      (node (ref "R216") (pin "D1") (pinfunction "4_D1") (pintype "passive"))
    )
    (net (code "149") (name "TCA3_I2C_SCL") (class "Default")
      (node (ref "IC38") (pin "8") (pinfunction "SC3_8") (pintype "bidirectional"))
      (node (ref "R216") (pin "A1") (pinfunction "1_A1") (pintype "passive"))
    )
    (net (code "150") (name "TCA3_I2C_SDA") (class "Default")
      (node (ref "IC38") (pin "7") (pinfunction "SD3_7") (pintype "bidirectional"))
      (node (ref "R216") (pin "B1") (pinfunction "2_B1") (pintype "passive"))
    )
    (net (code "151") (name "TCA4_I2C_SCL") (class "Default")
      (node (ref "IC13") (pin "5") (pinfunction "SCL_5") (pintype "bidirectional"))
      (node (ref "IC38") (pin "11") (pinfunction "SC4_11") (pintype "bidirectional"))
      (node (ref "R217") (pin "C1") (pinfunction "3_C1") (pintype "passive"))
    )
    (net (code "152") (name "TCA4_I2C_SDA") (class "Default")
      (node (ref "IC13") (pin "6") (pinfunction "SDA_6") (pintype "bidirectional"))
      (node (ref "IC38") (pin "10") (pinfunction "SD4_10") (pintype "bidirectional"))
      (node (ref "R217") (pin "D1") (pinfunction "4_D1") (pintype "passive"))
    )
    (net (code "153") (name "TCA5_I2C_SCL") (class "Default")
      (node (ref "IC38") (pin "13") (pinfunction "SC5_13") (pintype "bidirectional"))
      (node (ref "R217") (pin "A1") (pinfunction "1_A1") (pintype "passive"))
    )
    (net (code "154") (name "TCA5_I2C_SDA") (class "Default")
      (node (ref "IC38") (pin "12") (pinfunction "SD5_12") (pintype "bidirectional"))
      (node (ref "R217") (pin "B1") (pinfunction "2_B1") (pintype "passive"))
    )
    (net (code "155") (name "TCA6_I2C_SCL") (class "Default")
      (node (ref "IC38") (pin "15") (pinfunction "SC6_15") (pintype "bidirectional"))
    )
    (net (code "156") (name "TCA6_I2C_SDA") (class "Default")
      (node (ref "IC38") (pin "14") (pinfunction "SD6_14") (pintype "bidirectional"))
    )
    (net (code "157") (name "TCA7_I2C_SCL") (class "Default")
      (node (ref "IC38") (pin "17") (pinfunction "SC7_17") (pintype "bidirectional"))
    )
    (net (code "158") (name "TCA7_I2C_SDA") (class "Default")
      (node (ref "IC38") (pin "16") (pinfunction "SD7_16") (pintype "bidirectional"))
    )
    (net (code "159") (name "TCT") (class "Default")
      (node (ref "C30") (pin "1") (pinfunction "1_1") (pintype "passive"))
      (node (ref "ETH1") (pin "2") (pinfunction "P4/TCT_2") (pintype "passive"))
      (node (ref "R35") (pin "1") (pinfunction "1_1") (pintype "passive"))
    )
    (net (code "160") (name "TD_N") (class "Default")
      (node (ref "ETH1") (pin "3") (pinfunction "TD-_3") (pintype "passive"))
      (node (ref "R38") (pin "2") (pinfunction "2_2") (pintype "passive"))
      (node (ref "R44") (pin "1") (pinfunction "1_1") (pintype "passive"))
    )
    (net (code "161") (name "TD_P") (class "Default")
      (node (ref "ETH1") (pin "1") (pinfunction "TD+_1") (pintype "passive"))
      (node (ref "R37") (pin "2") (pinfunction "2_2") (pintype "passive"))
      (node (ref "R43") (pin "1") (pinfunction "1_1") (pintype "passive"))
    )
    (net (code "162") (name "TX_TD_N") (class "Default")
      (node (ref "IC31") (pin "1") (pinfunction "TXN_1") (pintype "output"))
      (node (ref "R38") (pin "1") (pinfunction "1_1") (pintype "passive"))
    )
    (net (code "163") (name "TX_TD_P") (class "Default")
      (node (ref "IC31") (pin "2") (pinfunction "TXP_2") (pintype "output"))
      (node (ref "R37") (pin "1") (pinfunction "1_1") (pintype "passive"))
    )
    (net (code "164") (name "UART0_RX") (class "Default")
      (node (ref "IC26") (pin "78") (pinfunction "GPIO1_78") (pintype "bidirectional"))
    )
    (net (code "165") (name "UART0_TX") (class "Default")
      (node (ref "IC26") (pin "77") (pinfunction "GPIO0_77") (pintype "bidirectional"))
    )
    (net (code "166") (name "USBA1_EN") (class "Default")
      (node (ref "IC42") (pin "17") (pinfunction "IO1.0_17") (pintype "bidirectional"))
      (node (ref "IC8") (pin "3") (pinfunction "EN_3") (pintype "bidirectional"))
      (node (ref "R1") (pin "2") (pinfunction "2_2") (pintype "passive"))
    )
    (net (code "167") (name "USBA2_EN") (class "Default")
      (node (ref "IC1") (pin "3") (pinfunction "EN_3") (pintype "bidirectional"))
      (node (ref "IC42") (pin "18") (pinfunction "IO1.1_18") (pintype "bidirectional"))
      (node (ref "R4") (pin "2") (pinfunction "2_2") (pintype "passive"))
    )
    (net (code "168") (name "USBA3_EN") (class "Default")
      (node (ref "IC2") (pin "3") (pinfunction "EN_3") (pintype "bidirectional"))
      (node (ref "IC42") (pin "19") (pinfunction "IO1.2_19") (pintype "bidirectional"))
      (node (ref "R7") (pin "2") (pinfunction "2_2") (pintype "passive"))
    )
    (net (code "169") (name "USBA4_EN") (class "Default")
      (node (ref "IC3") (pin "3") (pinfunction "EN_3") (pintype "bidirectional"))
      (node (ref "IC42") (pin "20") (pinfunction "IO1.3_20") (pintype "bidirectional"))
      (node (ref "R10") (pin "2") (pinfunction "2_2") (pintype "passive"))
    )
    (net (code "170") (name "USB_BOOT") (class "Default")
      (node (ref "R210") (pin "1") (pinfunction "1_1") (pintype "passive"))
      (node (ref "SW2") (pin "1") (pinfunction "P$1_1") (pintype "bidirectional"))
    )
    (net (code "171") (name "USB_DP_N") (class "Default")
      (node (ref "ESD1") (pin "3") (pinfunction "C2_3") (pintype "bidirectional"))
      (node (ref "USB9") (pin "A7") (pinfunction "D-_A7") (pintype "bidirectional"))
      (node (ref "USB9") (pin "B7") (pinfunction "D-_B7") (pintype "bidirectional"))
    )
    (net (code "172") (name "USB_DP_P") (class "Default")
      (node (ref "ESD1") (pin "2") (pinfunction "C1_2") (pintype "bidirectional"))
      (node (ref "USB9") (pin "A6") (pinfunction "D+_A6") (pintype "bidirectional"))
      (node (ref "USB9") (pin "B6") (pinfunction "D+_B6") (pintype "bidirectional"))
    )
    (net (code "173") (name "USB_RP_DP_N") (class "Default")
      (node (ref "R25") (pin "1") (pinfunction "1_1") (pintype "passive"))
    )
    (net (code "174") (name "USB_RP_DP_P") (class "Default")
      (node (ref "R26") (pin "1") (pinfunction "1_1") (pintype "passive"))
    )
    (net (code "175") (name "VBUS") (class "Default")
      (node (ref "C247") (pin "1") (pinfunction "1_1") (pintype "passive"))
      (node (ref "C248") (pin "1") (pinfunction "1_1") (pintype "passive"))
      (node (ref "ESD1") (pin "4") (pinfunction "C3_4") (pintype "bidirectional"))
      (node (ref "R249") (pin "1") (pinfunction "1_1") (pintype "passive"))
      (node (ref "R30") (pin "1") (pinfunction "1_1") (pintype "passive"))
      (node (ref "R31") (pin "1") (pinfunction "1_1") (pintype "passive"))
      (node (ref "USB9") (pin "VBUS1") (pinfunction "VBUS_VBUS1") (pintype "power_in"))
      (node (ref "USB9") (pin "VBUS2") (pinfunction "VBUS_VBUS2") (pintype "power_in"))
    )
    (net (code "176") (name "VBUS_USBA1") (class "Default")
      (node (ref "C83") (pin "1") (pinfunction "1_1") (pintype "passive"))
      (node (ref "C84") (pin "1") (pinfunction "1_1") (pintype "passive"))
      (node (ref "C85") (pin "1") (pinfunction "+_1") (pintype "passive"))
      (node (ref "IC8") (pin "6") (pinfunction "OUT_6") (pintype "bidirectional"))
      (node (ref "USBA_1-2") (pin "1") (pinfunction "VBUS_1") (pintype "passive"))
      (node (ref "VUSBA1") (pin "TP") (pinfunction "TP_TP") (pintype "input"))
    )
    (net (code "177") (name "VBUS_USBA2") (class "Default")
      (node (ref "C3") (pin "1") (pinfunction "1_1") (pintype "passive"))
      (node (ref "C4") (pin "1") (pinfunction "1_1") (pintype "passive"))
      (node (ref "C5") (pin "1") (pinfunction "+_1") (pintype "passive"))
      (node (ref "IC1") (pin "6") (pinfunction "OUT_6") (pintype "bidirectional"))
      (node (ref "USBA_1-2") (pin "5") (pinfunction "VBUS_5") (pintype "passive"))
      (node (ref "VUSBA2") (pin "TP") (pinfunction "TP_TP") (pintype "input"))
    )
    (net (code "178") (name "VBUS_USBA3") (class "Default")
      (node (ref "C10") (pin "1") (pinfunction "+_1") (pintype "passive"))
      (node (ref "C8") (pin "1") (pinfunction "1_1") (pintype "passive"))
      (node (ref "C9") (pin "1") (pinfunction "1_1") (pintype "passive"))
      (node (ref "IC2") (pin "6") (pinfunction "OUT_6") (pintype "bidirectional"))
      (node (ref "USBA_3-4") (pin "1") (pinfunction "VBUS_1") (pintype "passive"))
      (node (ref "VUSBA3") (pin "TP") (pinfunction "TP_TP") (pintype "input"))
    )
    (net (code "179") (name "VBUS_USBA4") (class "Default")
      (node (ref "C13") (pin "1") (pinfunction "1_1") (pintype "passive"))
      (node (ref "C14") (pin "1") (pinfunction "1_1") (pintype "passive"))
      (node (ref "C15") (pin "1") (pinfunction "+_1") (pintype "passive"))
      (node (ref "IC3") (pin "6") (pinfunction "OUT_6") (pintype "bidirectional"))
      (node (ref "USBA_3-4") (pin "5") (pinfunction "VBUS_5") (pintype "passive"))
      (node (ref "VUSBA4") (pin "TP") (pinfunction "TP_TP") (pintype "input"))
    )
    (net (code "180") (name "VOUT_PORT1") (class "Default")
      (node (ref "C217") (pin "1") (pinfunction "1_1") (pintype "passive"))
      (node (ref "C218") (pin "1") (pinfunction "+_1") (pintype "passive"))
      (node (ref "C51") (pin "1") (pinfunction "1_1") (pintype "passive"))
      (node (ref "C52") (pin "1") (pinfunction "1_1") (pintype "passive"))
      (node (ref "C53") (pin "1") (pinfunction "1_1") (pintype "passive"))
      (node (ref "C54") (pin "1") (pinfunction "1_1") (pintype "passive"))
      (node (ref "IC12") (pin "11") (pinfunction "VOUT_11") (pintype "power_in"))
      (node (ref "IC12") (pin "26") (pinfunction "VOUT_26") (pintype "power_in"))
      (node (ref "R228") (pin "2") (pinfunction "2_2") (pintype "passive"))
      (node (ref "R63") (pin "1") (pinfunction "1_1") (pintype "passive"))
    )
    (net (code "181") (name "VSRC1") (class "Default")
      (node (ref "C39") (pin "1") (pinfunction "1_1") (pintype "passive"))
      (node (ref "IC9") (pin "1") (pinfunction "VDD_1") (pintype "power_in"))
      (node (ref "R229") (pin "2") (pinfunction "2_2") (pintype "passive"))
      (node (ref "R5") (pin "1") (pinfunction "1_1") (pintype "passive"))
      (node (ref "R53") (pin "1") (pinfunction "1_1") (pintype "passive"))
      (node (ref "R63") (pin "2") (pinfunction "2_2") (pintype "passive"))
      (node (ref "T6") (pin "1") (pinfunction "S_1") (pintype "passive"))
      (node (ref "T6") (pin "2") (pinfunction "S_2") (pintype "passive"))
      (node (ref "T6") (pin "3") (pinfunction "S_3") (pintype "passive"))
      (node (ref "T7") (pin "5") (pinfunction "D_5") (pintype "passive"))
      (node (ref "T7") (pin "6") (pinfunction "D_6") (pintype "passive"))
      (node (ref "T7") (pin "7") (pinfunction "D_7") (pintype "passive"))
      (node (ref "T7") (pin "8") (pinfunction "D_8") (pintype "passive"))
      (node (ref "T7") (pin "9") (pinfunction "D_9") (pintype "passive"))
    )
    (net (code "182") (name "VUSB") (class "Default")
      (node (ref "R30") (pin "2") (pinfunction "2_2") (pintype "passive"))
    )
    (net (code "183") (name "W5500_MISO") (class "Default")
      (node (ref "IC26") (pin "16") (pinfunction "GPIO16_16") (pintype "bidirectional"))
      (node (ref "IC31") (pin "34") (pinfunction "MISO_34") (pintype "output"))
    )
    (net (code "184") (name "W5500_MOSI") (class "Default")
      (node (ref "IC26") (pin "19") (pinfunction "GPIO19_19") (pintype "bidirectional"))
      (node (ref "IC31") (pin "35") (pinfunction "MOSI_35") (pintype "input"))
    )
    (net (code "185") (name "W5500_SCK") (class "Default")
      (node (ref "IC26") (pin "18") (pinfunction "GPIO18_18") (pintype "bidirectional"))
      (node (ref "IC31") (pin "33") (pinfunction "SCLK_33") (pintype "input"))
    )
    (net (code "186") (name "unconnected-(DISP-Pad15)") (class "Default")
      (node (ref "DISP") (pin "15") (pinfunction "15_15") (pintype "bidirectional"))
    )
    (net (code "187") (name "unconnected-(DISP-Pad16)") (class "Default")
      (node (ref "DISP") (pin "16") (pinfunction "16_16") (pintype "bidirectional"))
    )
    (net (code "188") (name "unconnected-(DISP-Pad17)") (class "Default")
      (node (ref "DISP") (pin "17") (pinfunction "17_17") (pintype "bidirectional"))
    )
    (net (code "189") (name "unconnected-(DISP-Pad18)") (class "Default")
      (node (ref "DISP") (pin "18") (pinfunction "18_18") (pintype "bidirectional"))
    )
    (net (code "190") (name "unconnected-(DISP-Pad19)") (class "Default")
      (node (ref "DISP") (pin "19") (pinfunction "19_19") (pintype "bidirectional"))
    )
    (net (code "191") (name "unconnected-(IC12-CC_N-Pad6)") (class "Default")
      (node (ref "IC12") (pin "6") (pinfunction "CC_N_6") (pintype "output"))
    )
    (net (code "192") (name "unconnected-(IC12-PG-Pad5)") (class "Default")
      (node (ref "IC12") (pin "5") (pinfunction "PG_5") (pintype "output"))
    )
    (net (code "193") (name "unconnected-(IC26A-GPIO2-Pad79)") (class "Default")
      (node (ref "IC26") (pin "79") (pinfunction "GPIO2_79") (pintype "bidirectional"))
    )
    (net (code "194") (name "unconnected-(IC26A-GPIO3-Pad80)") (class "Default")
      (node (ref "IC26") (pin "80") (pinfunction "GPIO3_80") (pintype "bidirectional"))
    )
    (net (code "195") (name "unconnected-(IC26A-GPIO9-Pad7)") (class "Default")
      (node (ref "IC26") (pin "7") (pinfunction "GPIO9_7") (pintype "bidirectional"))
    )
    (net (code "196") (name "unconnected-(IC26A-GPIO10-Pad8)") (class "Default")
      (node (ref "IC26") (pin "8") (pinfunction "GPIO10_8") (pintype "bidirectional"))
    )
    (net (code "197") (name "unconnected-(IC26A-GPIO11-Pad9)") (class "Default")
      (node (ref "IC26") (pin "9") (pinfunction "GPIO11_9") (pintype "bidirectional"))
    )
    (net (code "198") (name "unconnected-(IC26A-GPIO22-Pad22)") (class "Default")
      (node (ref "IC26") (pin "22") (pinfunction "GPIO22_22") (pintype "bidirectional"))
    )
    (net (code "199") (name "unconnected-(IC26A-GPIO23-Pad23)") (class "Default")
      (node (ref "IC26") (pin "23") (pinfunction "GPIO23_23") (pintype "bidirectional"))
    )
    (net (code "200") (name "unconnected-(IC26A-GPIO28-Pad36)") (class "Default")
      (node (ref "IC26") (pin "36") (pinfunction "GPIO28_36") (pintype "bidirectional"))
    )
    (net (code "201") (name "unconnected-(IC26A-GPIO29-Pad37)") (class "Default")
      (node (ref "IC26") (pin "37") (pinfunction "GPIO29_37") (pintype "bidirectional"))
    )
    (net (code "202") (name "unconnected-(IC26B-GPIO30-Pad38)") (class "Default")
      (node (ref "IC26") (pin "38") (pinfunction "GPIO30_38") (pintype "bidirectional"))
    )
    (net (code "203") (name "unconnected-(IC26B-GPIO31-Pad39)") (class "Default")
      (node (ref "IC26") (pin "39") (pinfunction "GPIO31_39") (pintype "bidirectional"))
    )
    (net (code "204") (name "unconnected-(IC26B-GPIO32-Pad40)") (class "Default")
      (node (ref "IC26") (pin "40") (pinfunction "GPIO32_40") (pintype "bidirectional"))
    )
    (net (code "205") (name "unconnected-(IC26B-GPIO33-Pad42)") (class "Default")
      (node (ref "IC26") (pin "42") (pinfunction "GPIO33_42") (pintype "bidirectional"))
    )
    (net (code "206") (name "unconnected-(IC26B-GPIO34-Pad43)") (class "Default")
      (node (ref "IC26") (pin "43") (pinfunction "GPIO34_43") (pintype "bidirectional"))
    )
    (net (code "207") (name "unconnected-(IC26B-GPIO35-Pad44)") (class "Default")
      (node (ref "IC26") (pin "44") (pinfunction "GPIO35_44") (pintype "bidirectional"))
    )
    (net (code "208") (name "unconnected-(IC26B-GPIO36-Pad45)") (class "Default")
      (node (ref "IC26") (pin "45") (pinfunction "GPIO36_45") (pintype "bidirectional"))
    )
    (net (code "209") (name "unconnected-(IC26B-GPIO37-Pad46)") (class "Default")
      (node (ref "IC26") (pin "46") (pinfunction "GPIO37_46") (pintype "bidirectional"))
    )
    (net (code "210") (name "unconnected-(IC26B-GPIO38-Pad47)") (class "Default")
      (node (ref "IC26") (pin "47") (pinfunction "GPIO38_47") (pintype "bidirectional"))
    )
    (net (code "211") (name "unconnected-(IC26B-GPIO39-Pad48)") (class "Default")
      (node (ref "IC26") (pin "48") (pinfunction "GPIO39_48") (pintype "bidirectional"))
    )
    (net (code "212") (name "unconnected-(IC26B-GPIO40_ADC0-Pad49)") (class "Default")
      (node (ref "IC26") (pin "49") (pinfunction "GPIO40_ADC0_49") (pintype "bidirectional"))
    )
    (net (code "213") (name "unconnected-(IC26B-GPIO41_ADC1-Pad52)") (class "Default")
      (node (ref "IC26") (pin "52") (pinfunction "GPIO41_ADC1_52") (pintype "bidirectional"))
    )
    (net (code "214") (name "unconnected-(IC26B-GPIO42_ADC2-Pad53)") (class "Default")
      (node (ref "IC26") (pin "53") (pinfunction "GPIO42_ADC2_53") (pintype "bidirectional"))
    )
    (net (code "215") (name "unconnected-(IC26B-GPIO43_ADC3-Pad54)") (class "Default")
      (node (ref "IC26") (pin "54") (pinfunction "GPIO43_ADC3_54") (pintype "bidirectional"))
    )
    (net (code "216") (name "unconnected-(IC26B-GPIO44_ADC4-Pad55)") (class "Default")
      (node (ref "IC26") (pin "55") (pinfunction "GPIO44_ADC4_55") (pintype "bidirectional"))
    )
    (net (code "217") (name "unconnected-(IC26B-GPIO45_ADC5-Pad56)") (class "Default")
      (node (ref "IC26") (pin "56") (pinfunction "GPIO45_ADC5_56") (pintype "bidirectional"))
    )
    (net (code "218") (name "unconnected-(IC26B-GPIO46_ADC6-Pad57)") (class "Default")
      (node (ref "IC26") (pin "57") (pinfunction "GPIO46_ADC6_57") (pintype "bidirectional"))
    )
    (net (code "219") (name "unconnected-(IC26B-GPIO47_ADC7-Pad58)") (class "Default")
      (node (ref "IC26") (pin "58") (pinfunction "GPIO47_ADC7_58") (pintype "bidirectional"))
    )
    (net (code "220") (name "unconnected-(IC31-DNC-Pad7)") (class "Default")
      (node (ref "IC31") (pin "7") (pinfunction "DNC_7") (pintype "bidirectional"))
    )
    (net (code "221") (name "unconnected-(IC31-RSVD1-Pad23)") (class "Default")
      (node (ref "IC31") (pin "23") (pinfunction "RSVD1_23") (pintype "input"))
    )
    (net (code "222") (name "unconnected-(IC31-RSVD2-Pad38)") (class "Default")
      (node (ref "IC31") (pin "38") (pinfunction "RSVD2_38") (pintype "input"))
    )
    (net (code "223") (name "unconnected-(IC31-RSVD3-Pad39)") (class "Default")
      (node (ref "IC31") (pin "39") (pinfunction "RSVD3_39") (pintype "input"))
    )
    (net (code "224") (name "unconnected-(IC31-RSVD4-Pad40)") (class "Default")
      (node (ref "IC31") (pin "40") (pinfunction "RSVD4_40") (pintype "input"))
    )
    (net (code "225") (name "unconnected-(IC31-RSVD5-Pad41)") (class "Default")
      (node (ref "IC31") (pin "41") (pinfunction "RSVD5_41") (pintype "input"))
    )
    (net (code "226") (name "unconnected-(IC31-RSVD6-Pad42)") (class "Default")
      (node (ref "IC31") (pin "42") (pinfunction "RSVD6_42") (pintype "input"))
    )
    (net (code "227") (name "unconnected-(IC31-VBG-Pad18)") (class "Default")
      (node (ref "IC31") (pin "18") (pinfunction "VBG_18") (pintype "output"))
    )
    (net (code "228") (name "unconnected-(IC42-INTA-Pad16)") (class "Default")
      (node (ref "IC42") (pin "16") (pinfunction "INTA_16") (pintype "bidirectional"))
    )
    (net (code "229") (name "unconnected-(IC42-INTB-Pad15)") (class "Default")
      (node (ref "IC42") (pin "15") (pinfunction "INTB_15") (pintype "bidirectional"))
    )
    (net (code "230") (name "unconnected-(USB9-SBU1-PadA8)") (class "Default")
      (node (ref "USB9") (pin "A8") (pinfunction "SBU1_A8") (pintype "bidirectional"))
    )
    (net (code "231") (name "unconnected-(USB9-SBU2-PadB8)") (class "Default")
      (node (ref "USB9") (pin "B8") (pinfunction "SBU2_B8") (pintype "bidirectional"))
    )
    (net (code "232") (name "unconnected-(USBA_1-2A-D+-Pad3)") (class "Default")
      (node (ref "USBA_1-2") (pin "3") (pinfunction "D+_3") (pintype "passive"))
    )
    (net (code "233") (name "unconnected-(USBA_1-2A-D--Pad2)") (class "Default")
      (node (ref "USBA_1-2") (pin "2") (pinfunction "D-_2") (pintype "passive"))
    )
    (net (code "234") (name "unconnected-(USBA_1-2B-D+-Pad7)") (class "Default")
      (node (ref "USBA_1-2") (pin "7") (pinfunction "D+_7") (pintype "passive"))
    )
    (net (code "235") (name "unconnected-(USBA_1-2B-D--Pad6)") (class "Default")
      (node (ref "USBA_1-2") (pin "6") (pinfunction "D-_6") (pintype "passive"))
    )
    (net (code "236") (name "unconnected-(USBA_3-4A-D+-Pad3)") (class "Default")
      (node (ref "USBA_3-4") (pin "3") (pinfunction "D+_3") (pintype "passive"))
    )
    (net (code "237") (name "unconnected-(USBA_3-4A-D--Pad2)") (class "Default")
      (node (ref "USBA_3-4") (pin "2") (pinfunction "D-_2") (pintype "passive"))
    )
    (net (code "238") (name "unconnected-(USBA_3-4B-D+-Pad7)") (class "Default")
      (node (ref "USBA_3-4") (pin "7") (pinfunction "D+_7") (pintype "passive"))
    )
    (net (code "239") (name "unconnected-(USBA_3-4B-D--Pad6)") (class "Default")
      (node (ref "USBA_3-4") (pin "6") (pinfunction "D-_6") (pintype "passive"))
    )
    (net (code "240") (name "~{ACT}") (class "Default")
      (node (ref "IC31") (pin "27") (pinfunction "ACTLED_27") (pintype "output"))
      (node (ref "R34") (pin "1") (pinfunction "1_1") (pintype "passive"))
    )
    (net (code "241") (name "~{DUP}") (class "Default")
      (node (ref "IC31") (pin "26") (pinfunction "DUPLED_26") (pintype "output"))
      (node (ref "R227") (pin "1") (pinfunction "1_1") (pintype "passive"))
    )
    (net (code "242") (name "~{LINK}") (class "Default")
      (node (ref "IC31") (pin "25") (pinfunction "LINKLED_25") (pintype "output"))
      (node (ref "R33") (pin "1") (pinfunction "1_1") (pintype "passive"))
    )
    (net (code "243") (name "~{QSPI_SS}") (class "Default")
      (node (ref "IC26") (pin "75") (pinfunction "QSPI_SS_75") (pintype "output"))
      (node (ref "IC27") (pin "1") (pinfunction "~{CS}_1") (pintype "bidirectional"))
      (node (ref "R209") (pin "1") (pinfunction "1_1") (pintype "passive"))
      (node (ref "R210") (pin "2") (pinfunction "2_2") (pintype "passive"))
    )
    (net (code "244") (name "~{SPD}") (class "Default")
      (node (ref "IC31") (pin "24") (pinfunction "SPDLED_24") (pintype "output"))
      (node (ref "R226") (pin "1") (pinfunction "1_1") (pintype "passive"))
    )
    (net (code "245") (name "~{TCA_RST}") (class "Default")
      (node (ref "IC38") (pin "24") (pinfunction "RESET_24") (pintype "input"))
    )
    (net (code "246") (name "~{W5500_CS}") (class "Default")
      (node (ref "IC26") (pin "17") (pinfunction "GPIO17_17") (pintype "bidirectional"))
      (node (ref "IC31") (pin "32") (pinfunction "~{SCSN}_32") (pintype "input"))
    )
    (net (code "247") (name "~{W5500_INT}") (class "Default")
      (node (ref "IC26") (pin "21") (pinfunction "GPIO21_21") (pintype "bidirectional"))
      (node (ref "IC31") (pin "36") (pinfunction "~{INTN}_36") (pintype "input"))
    )
    (net (code "248") (name "~{W5500_RST}") (class "Default")
      (node (ref "IC26") (pin "20") (pinfunction "GPIO20_20") (pintype "bidirectional"))
      (node (ref "IC31") (pin "37") (pinfunction "~{RSTN}_37") (pintype "input"))
      (node (ref "R206") (pin "1") (pinfunction "1_1") (pintype "passive"))
    )
  )
)
